# Maker_Display4.net
KiCad netlist of a schematic drawn in EAGLE
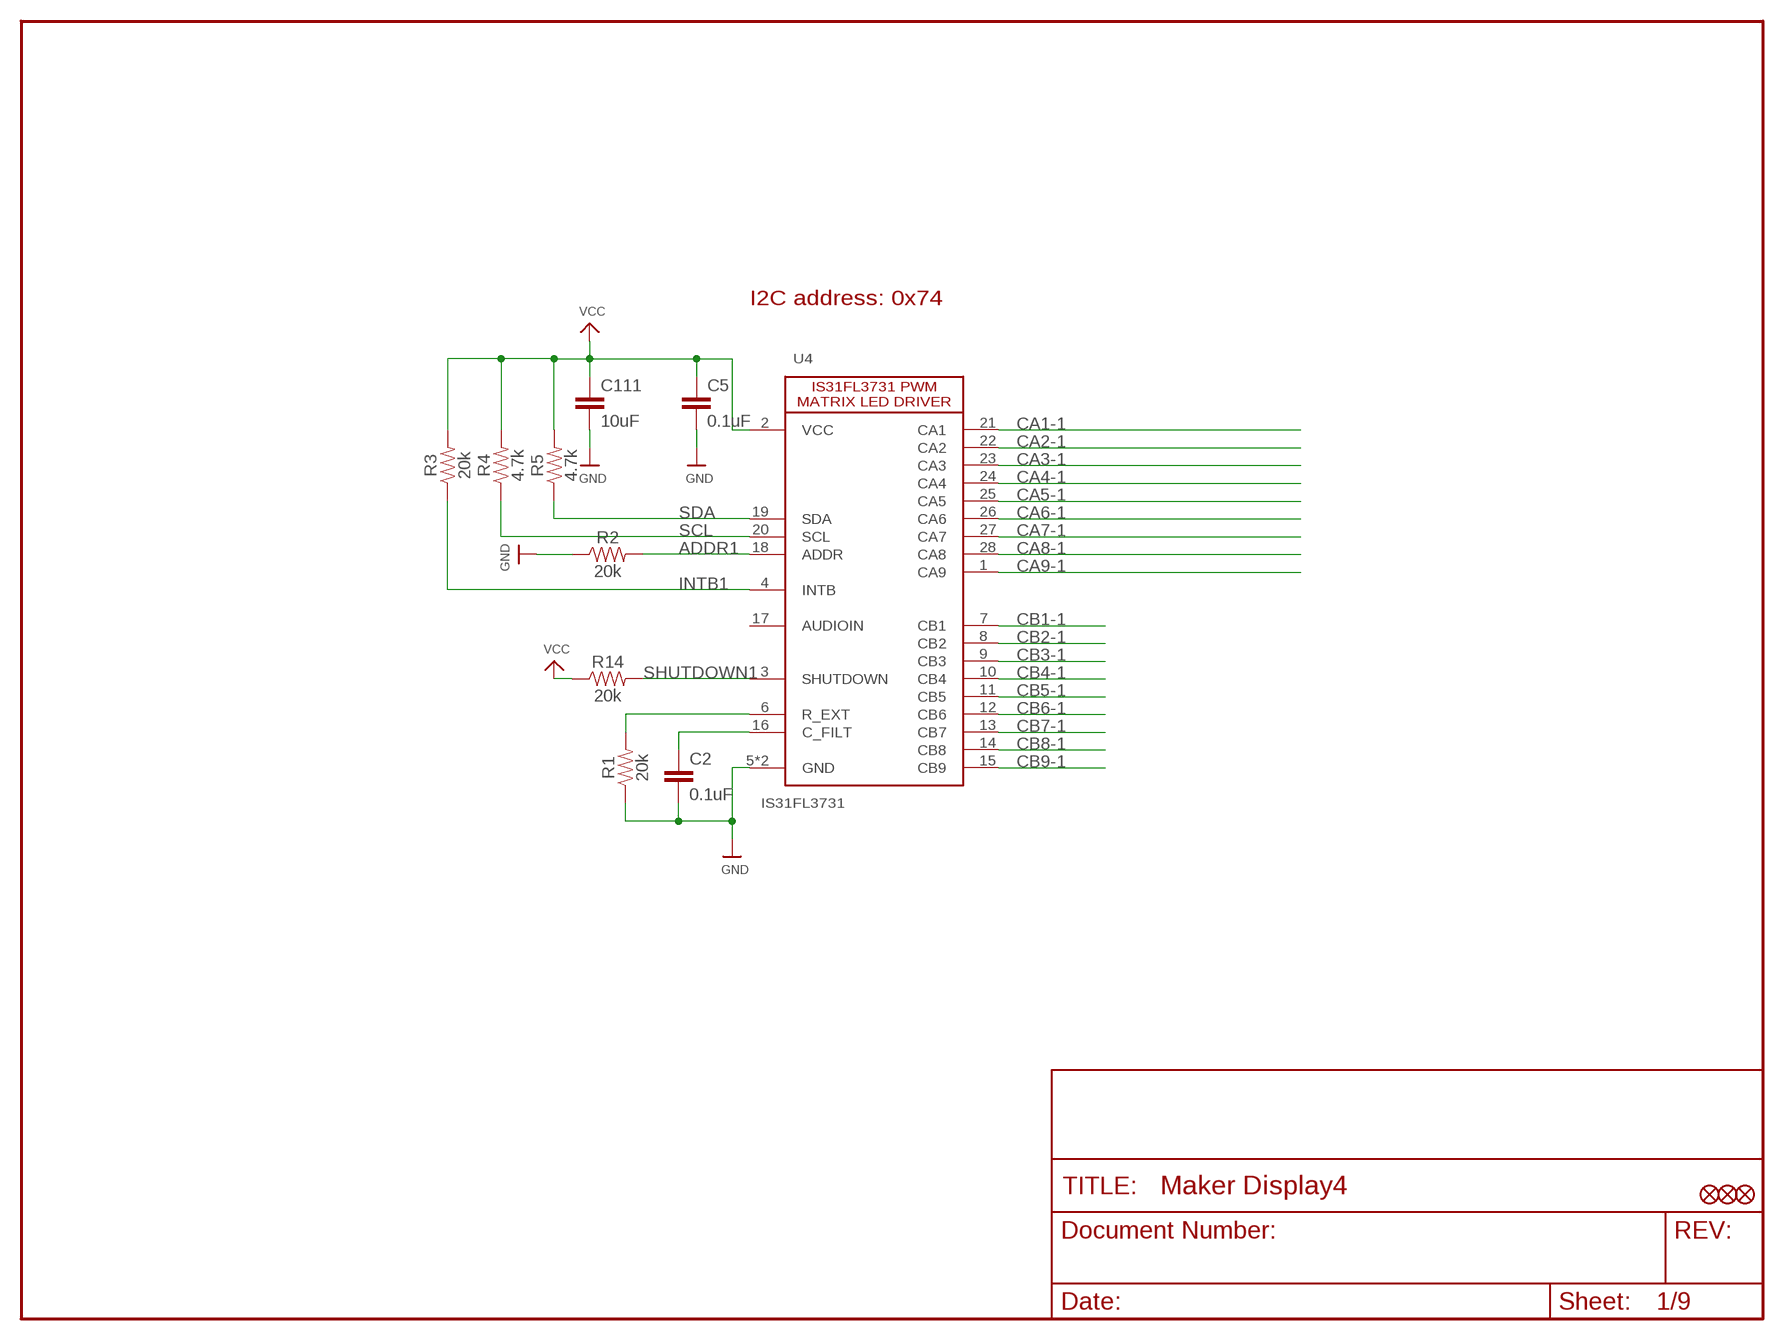
[diagram p0: schematic, sheet 1]
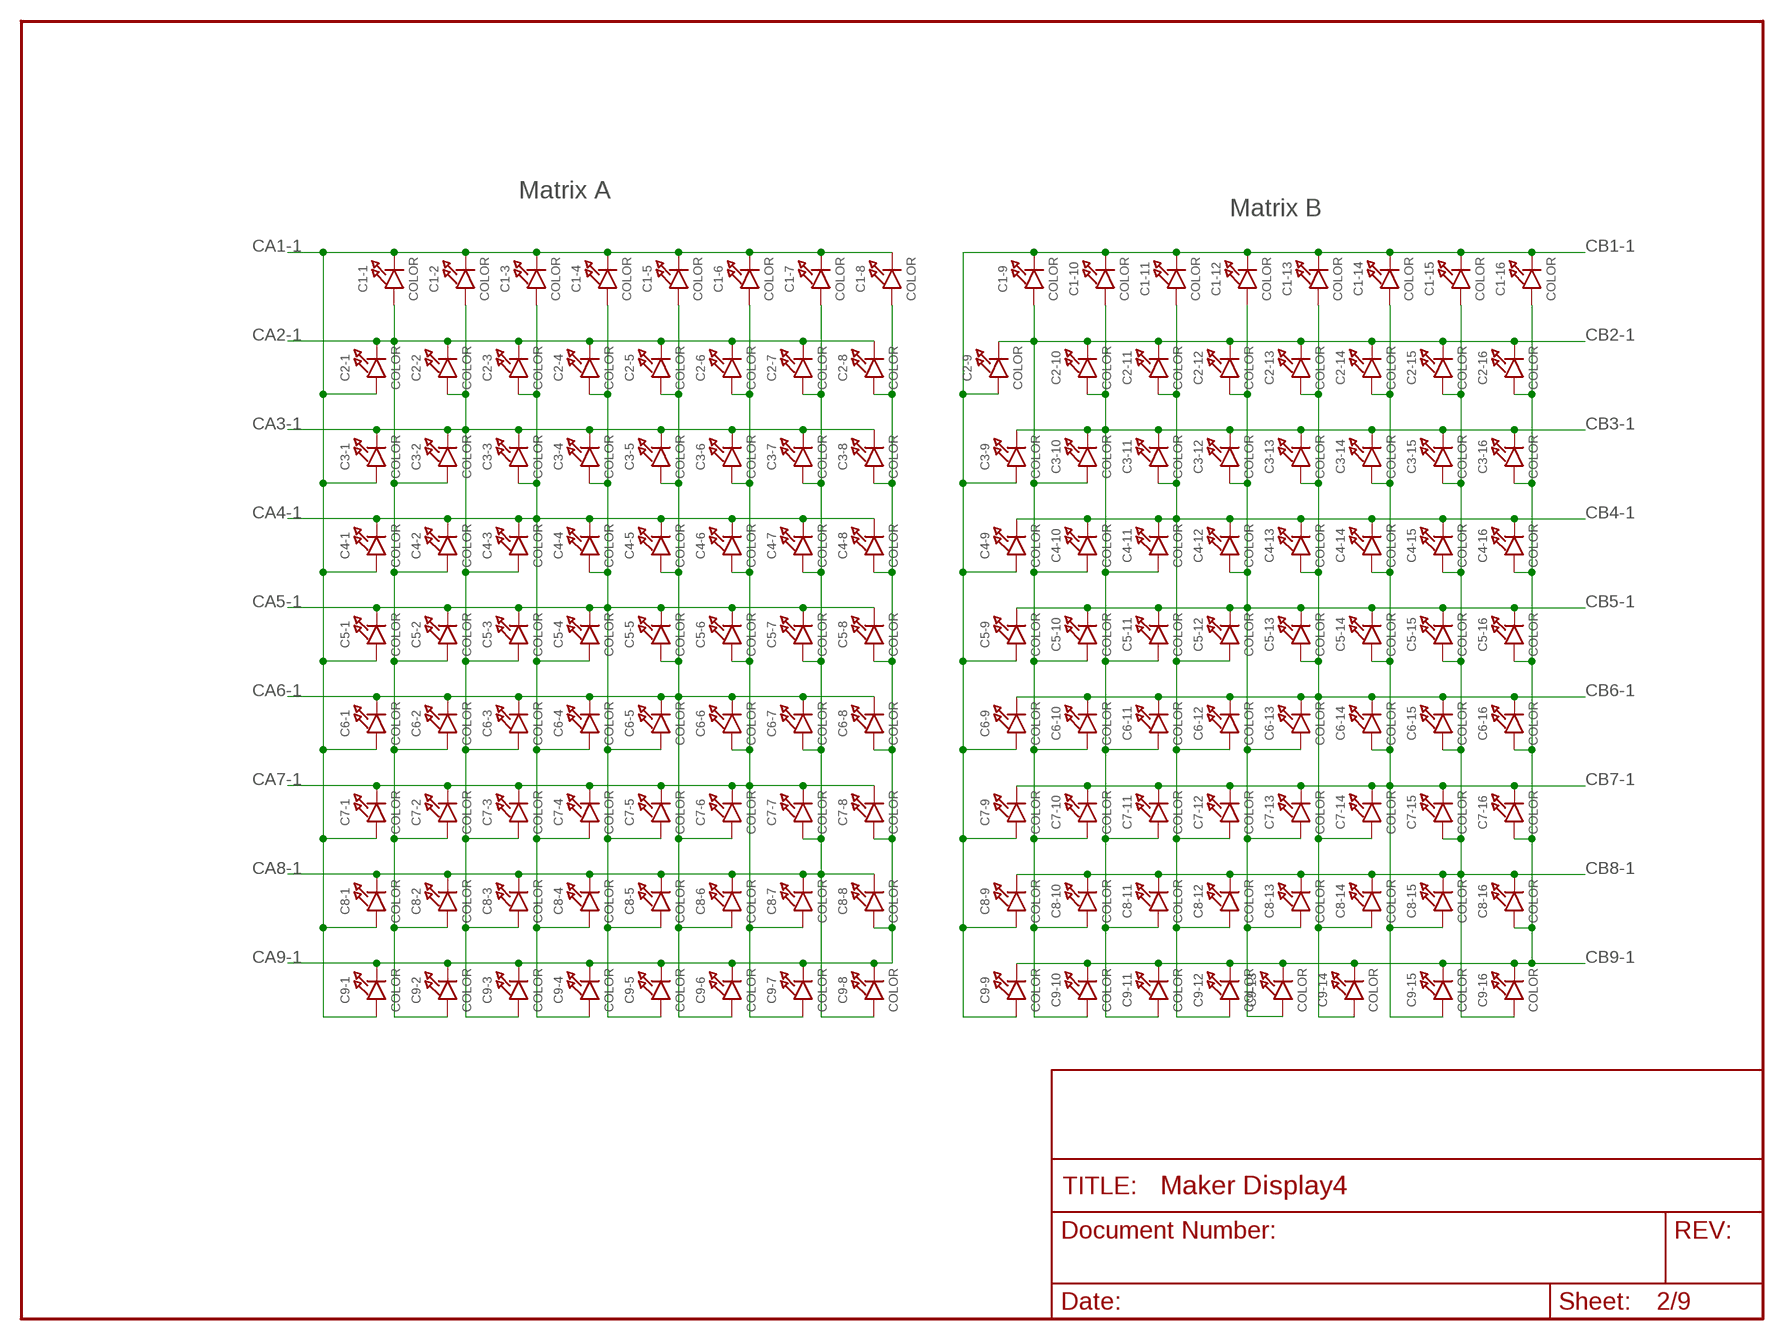
[diagram p1: schematic, sheet 2]
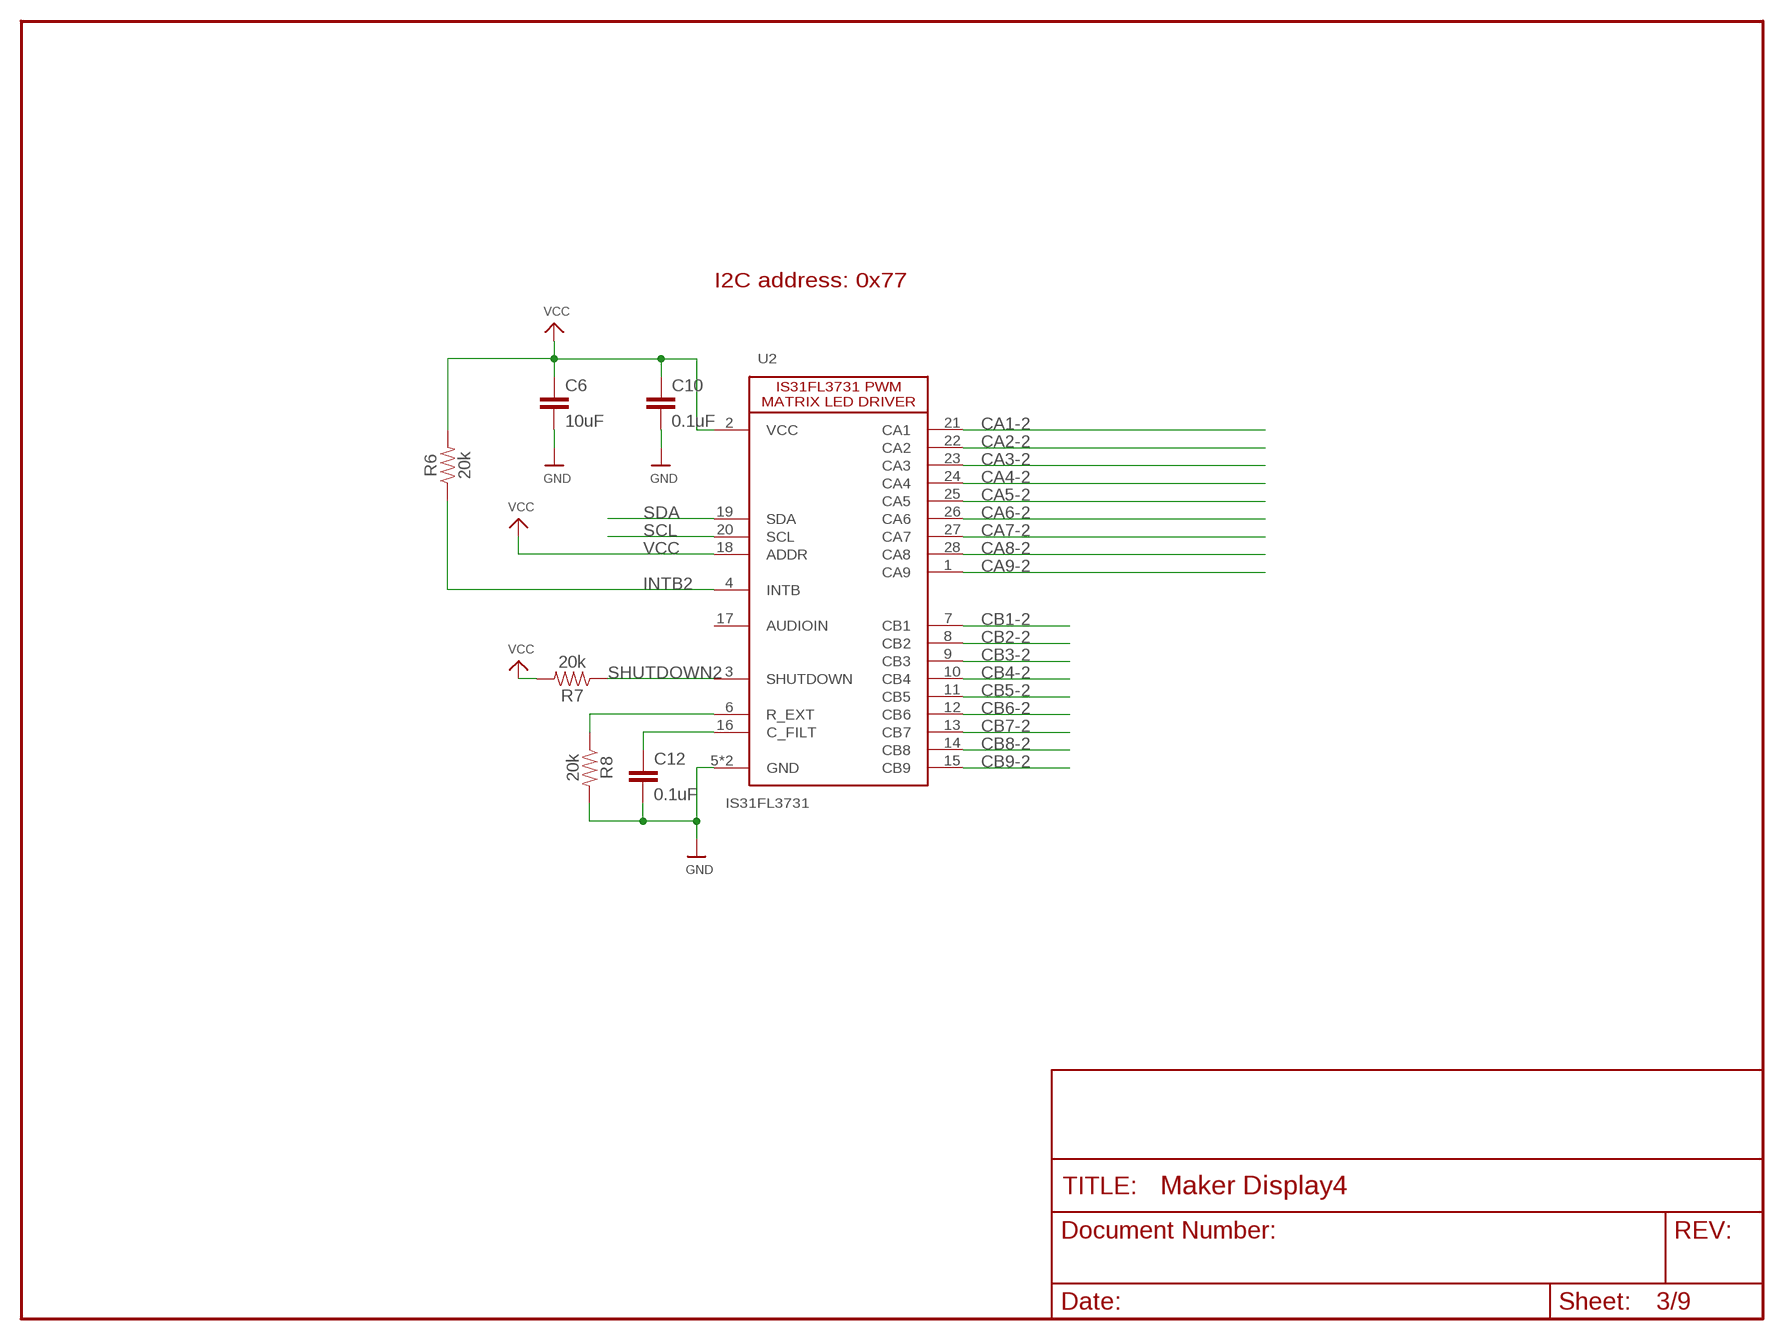
[diagram p2: schematic, sheet 3]
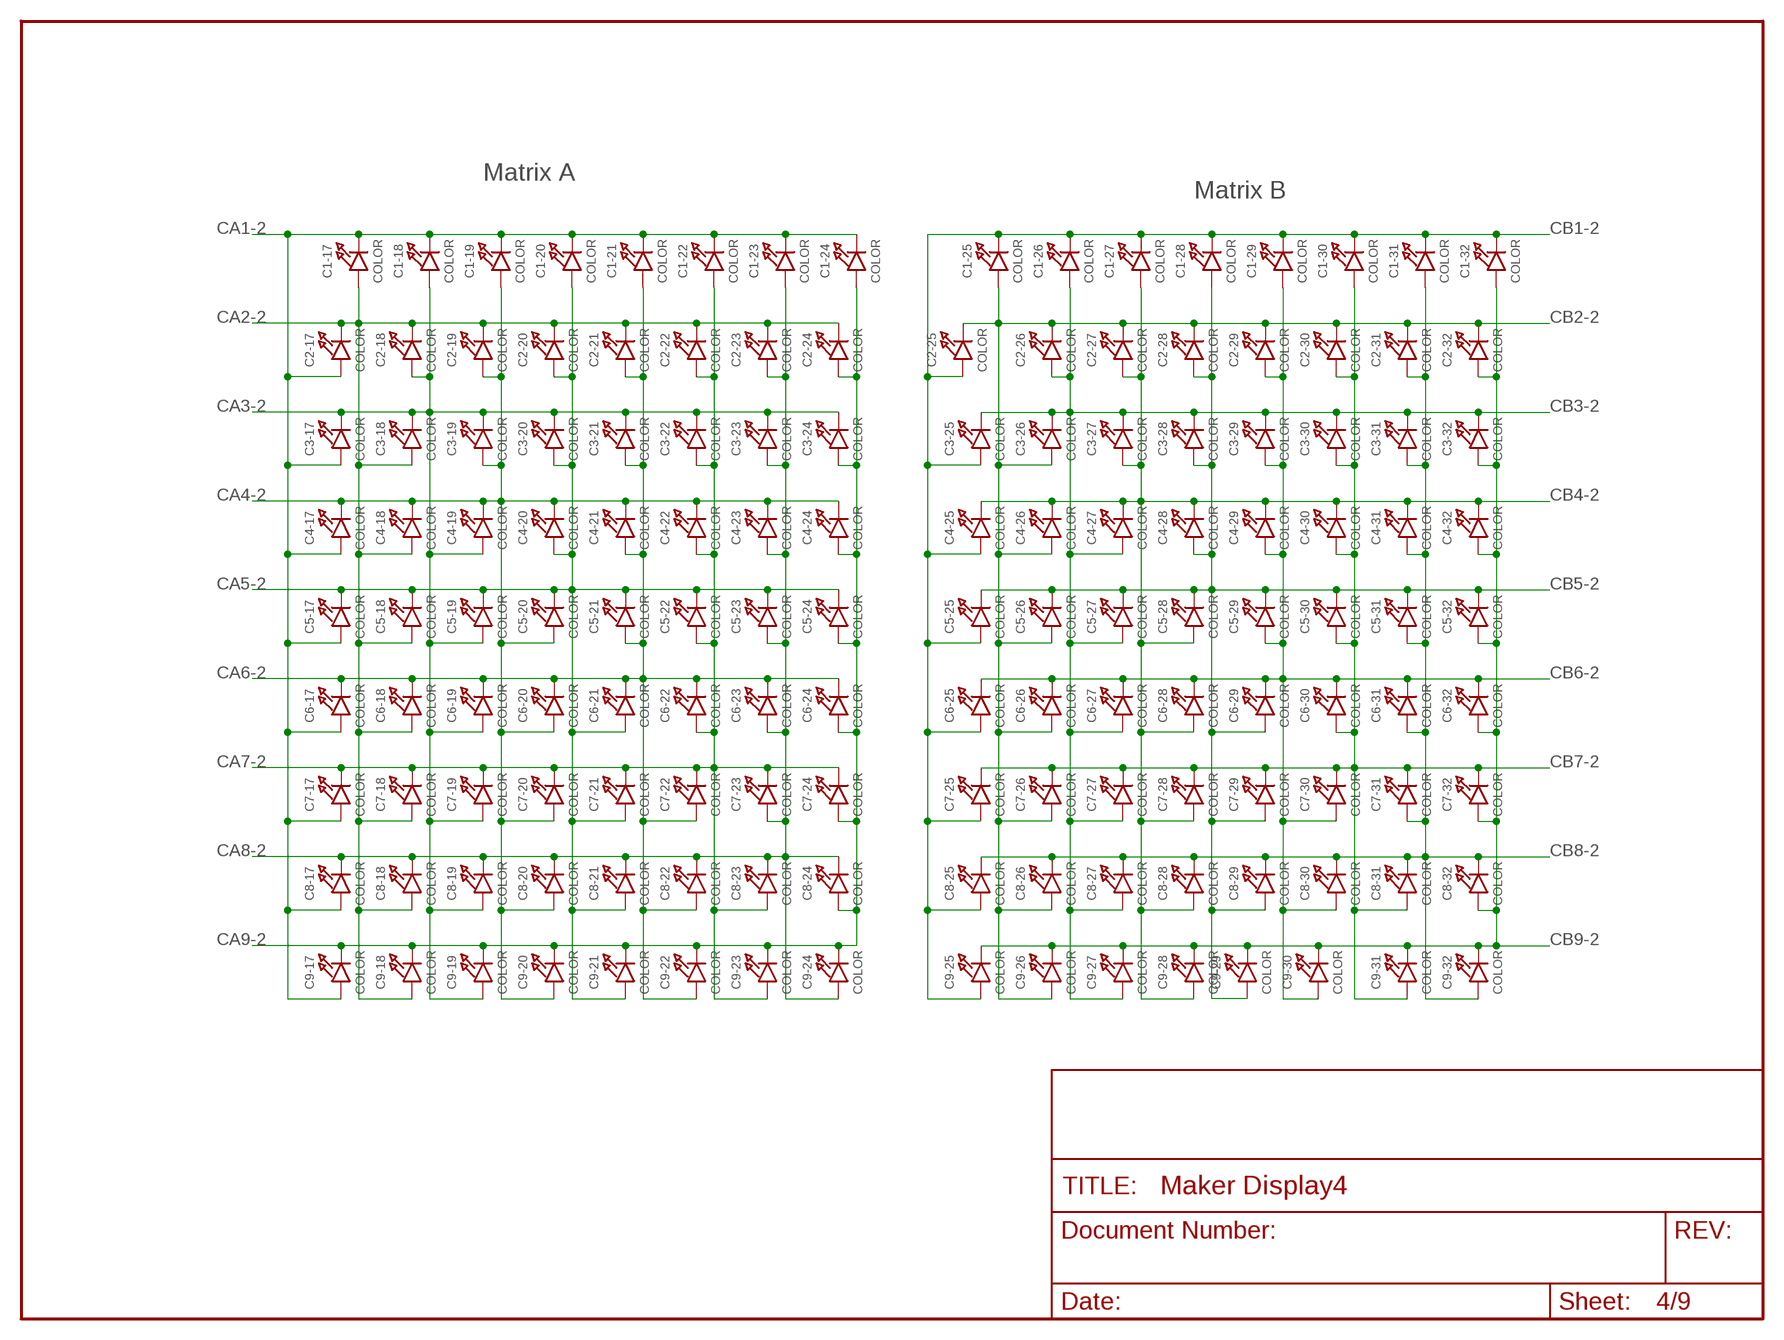
[diagram p3: schematic, sheet 4]
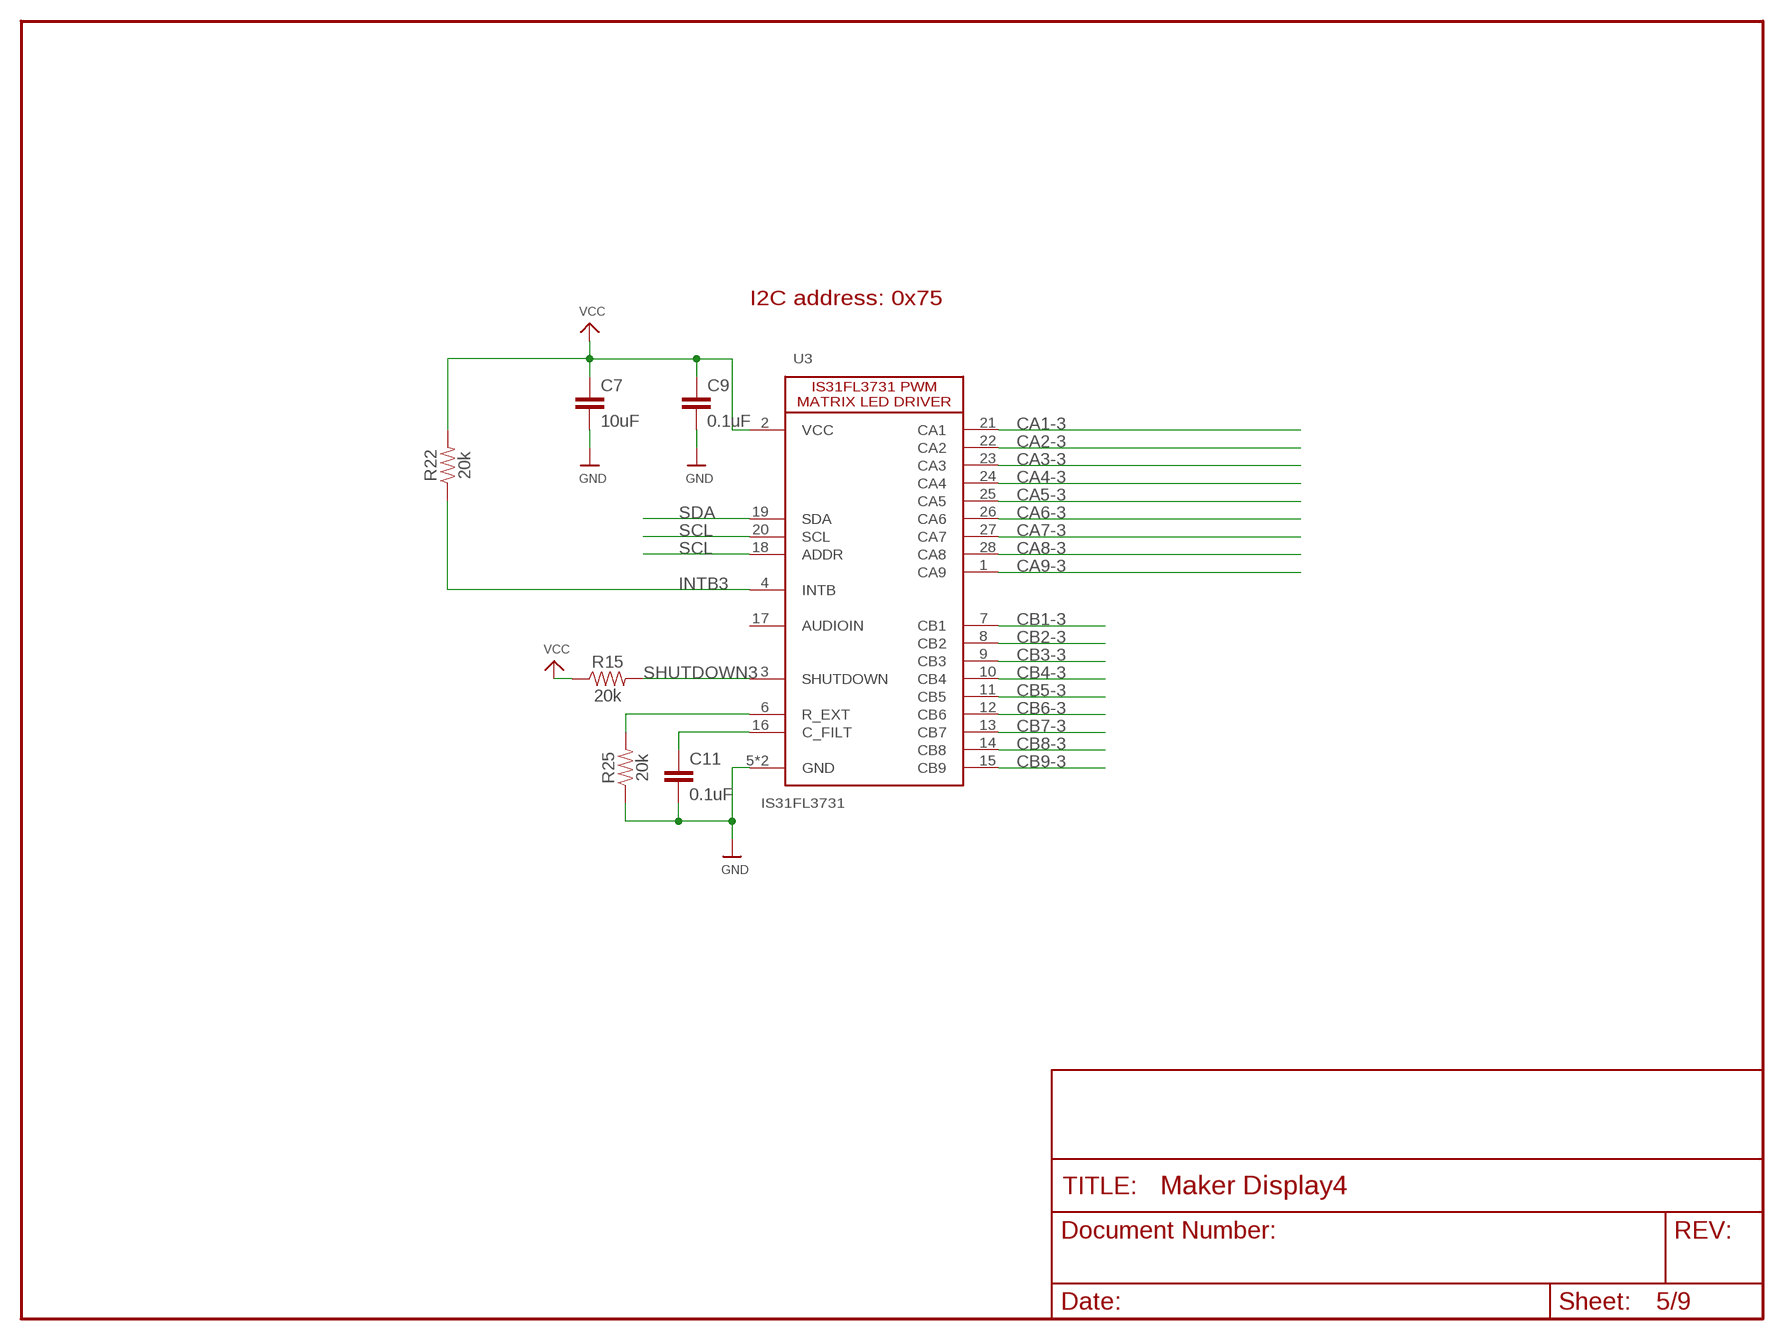
[diagram p4: schematic, sheet 5]
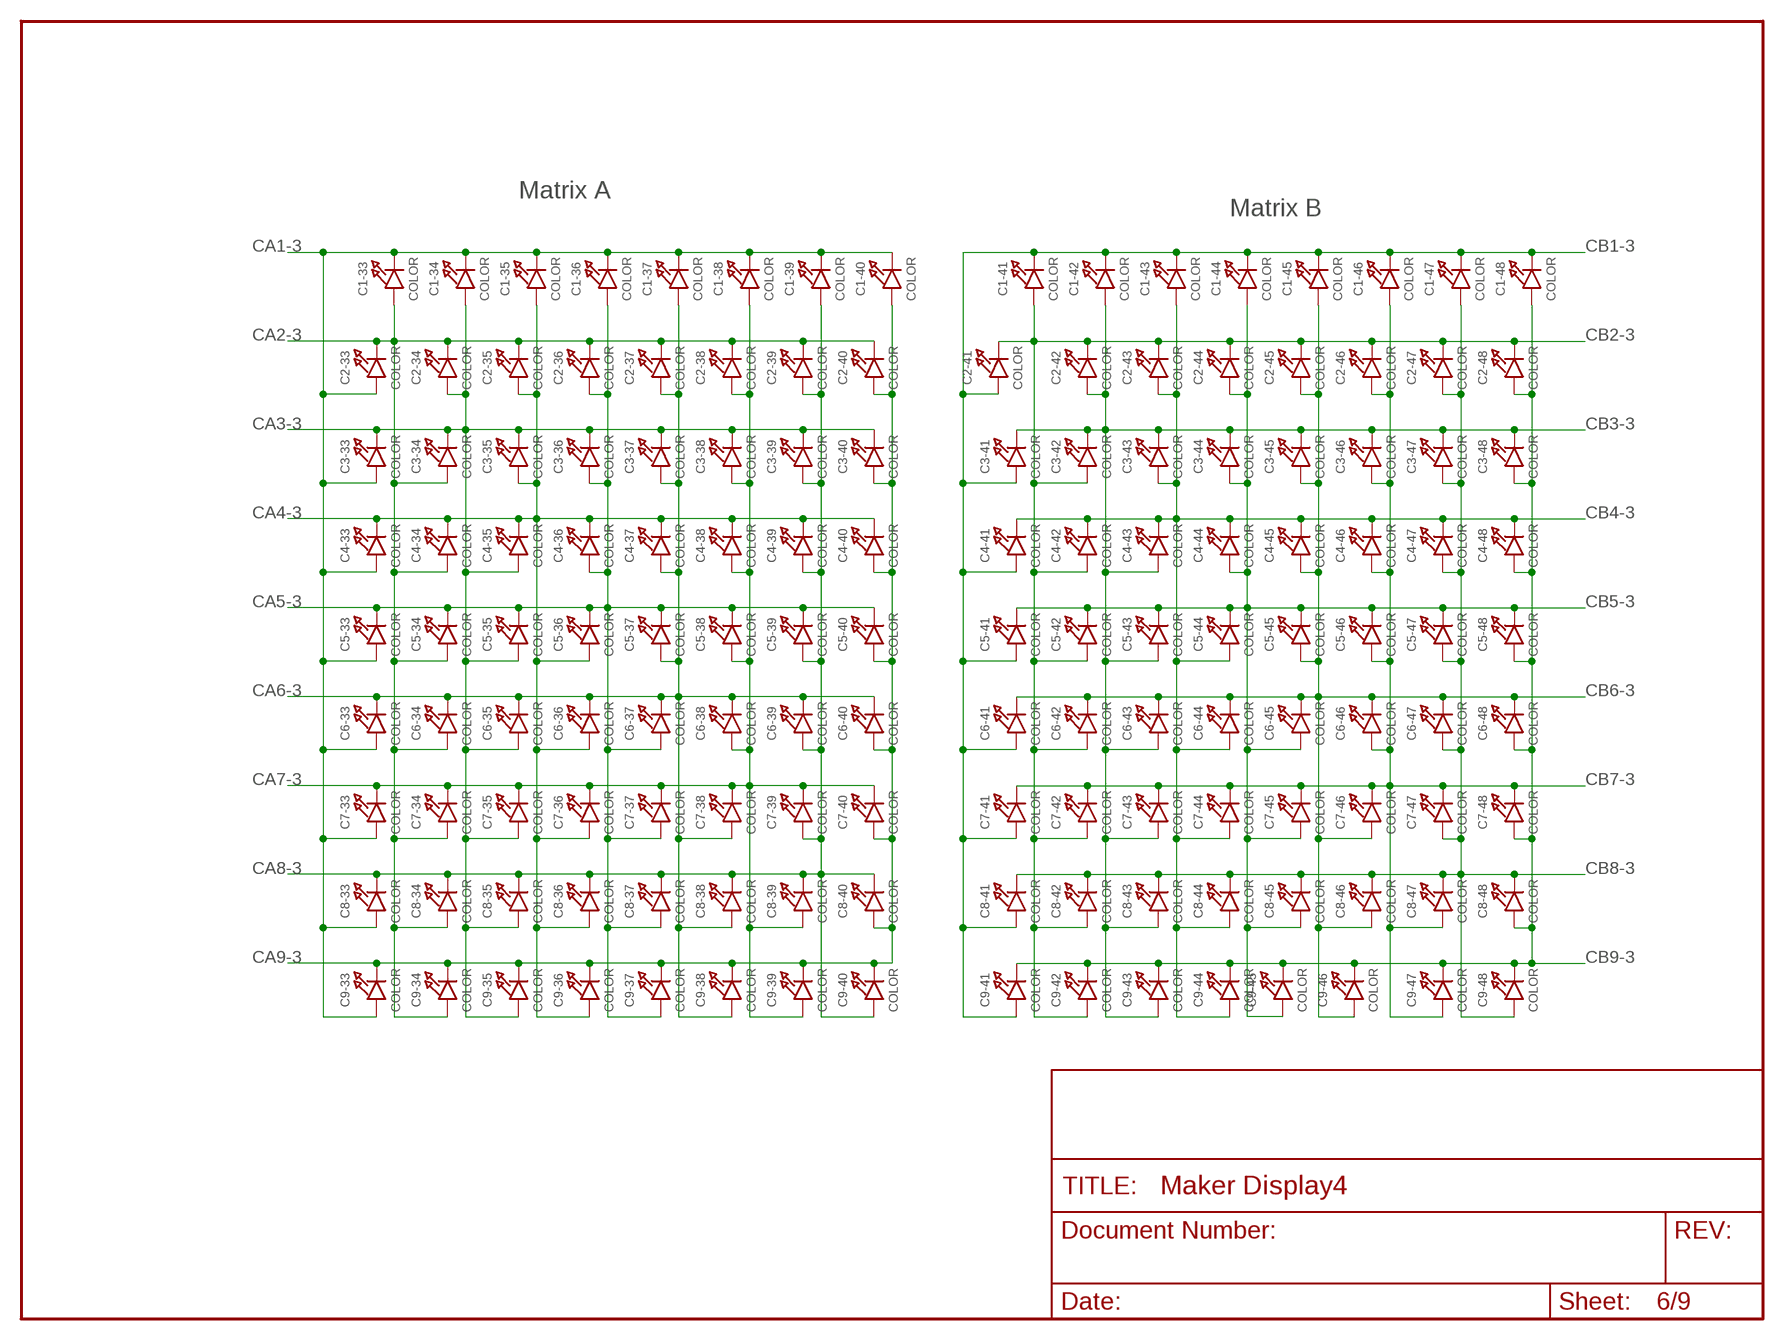
[diagram p5: schematic, sheet 6]
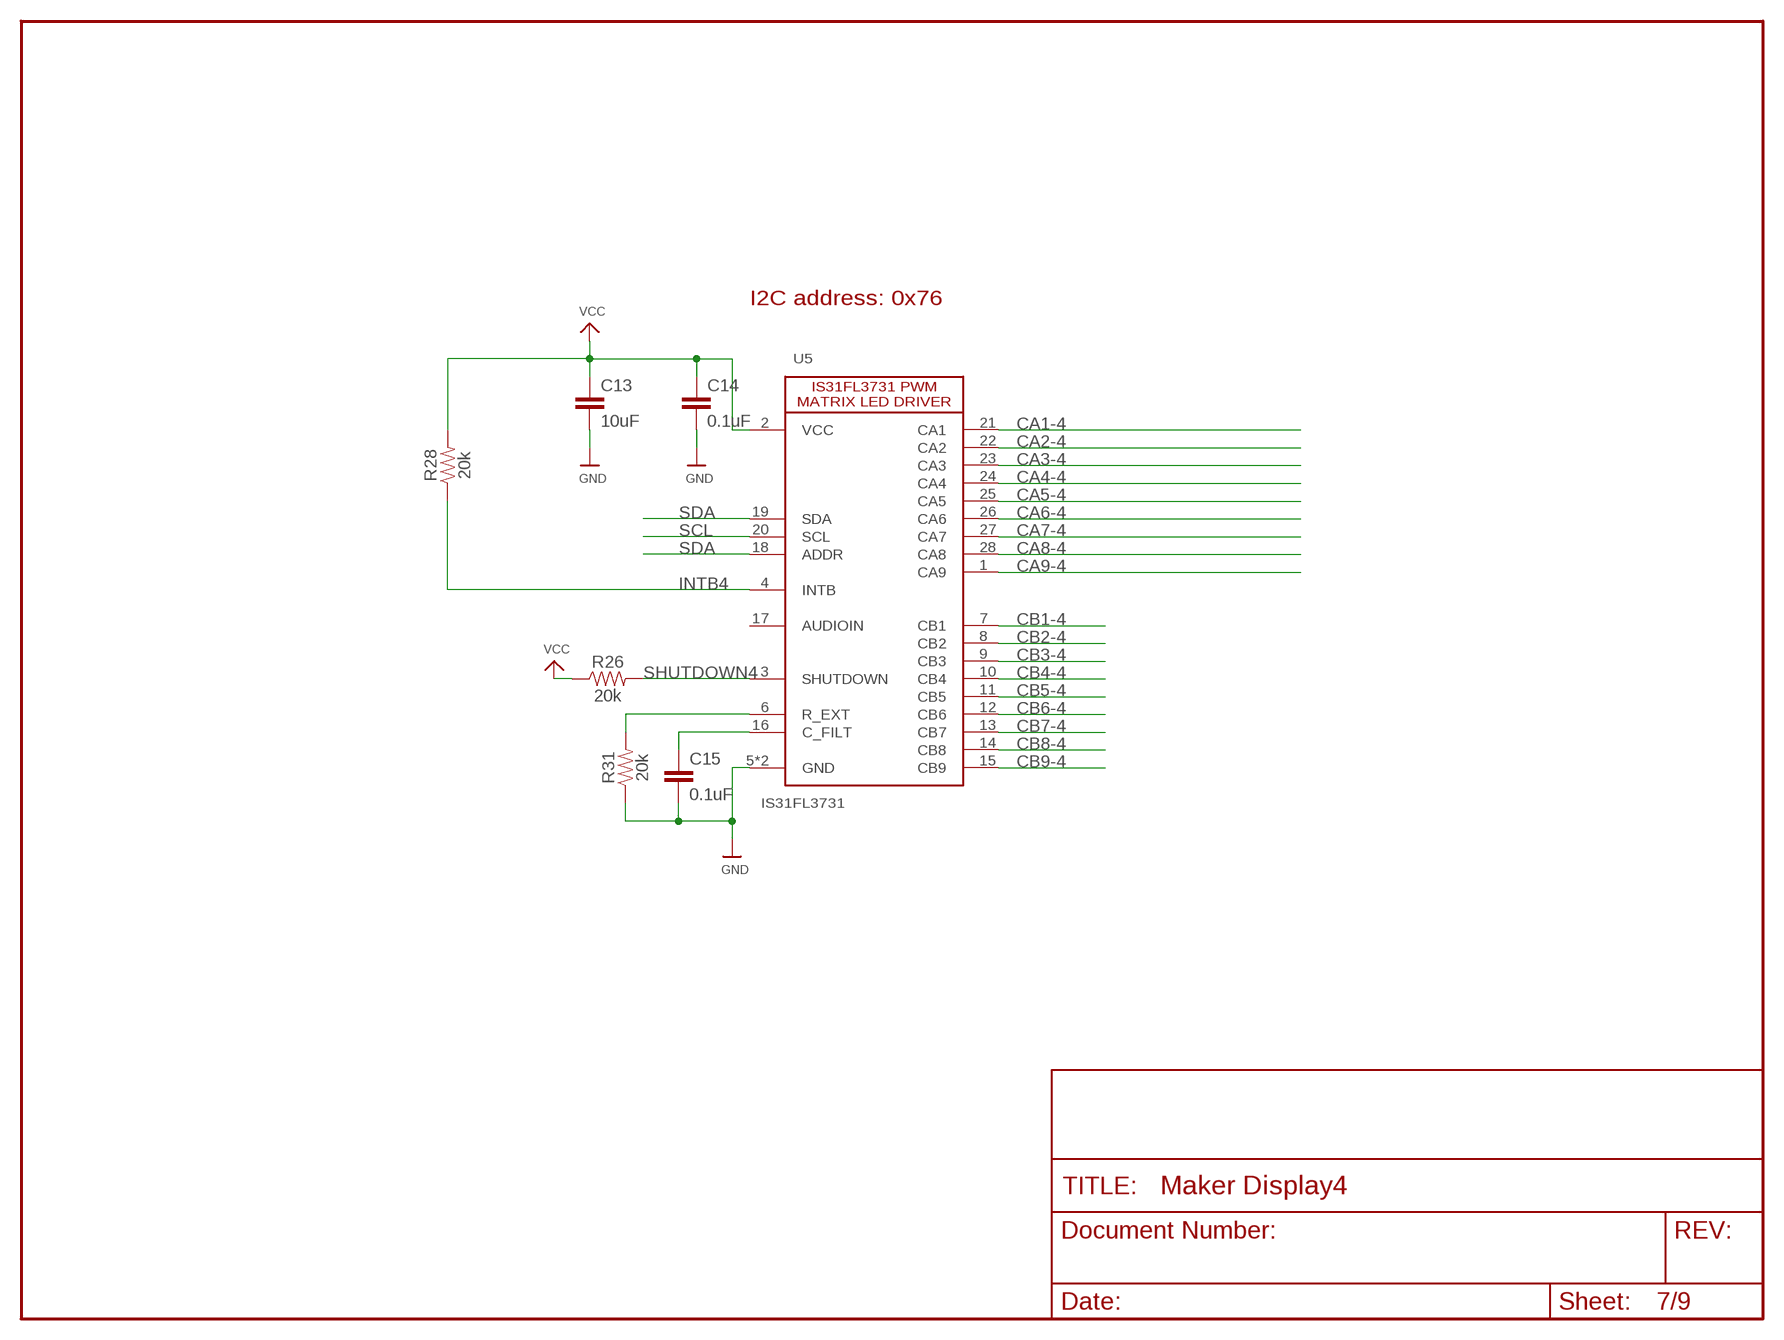
[diagram p6: schematic, sheet 7]
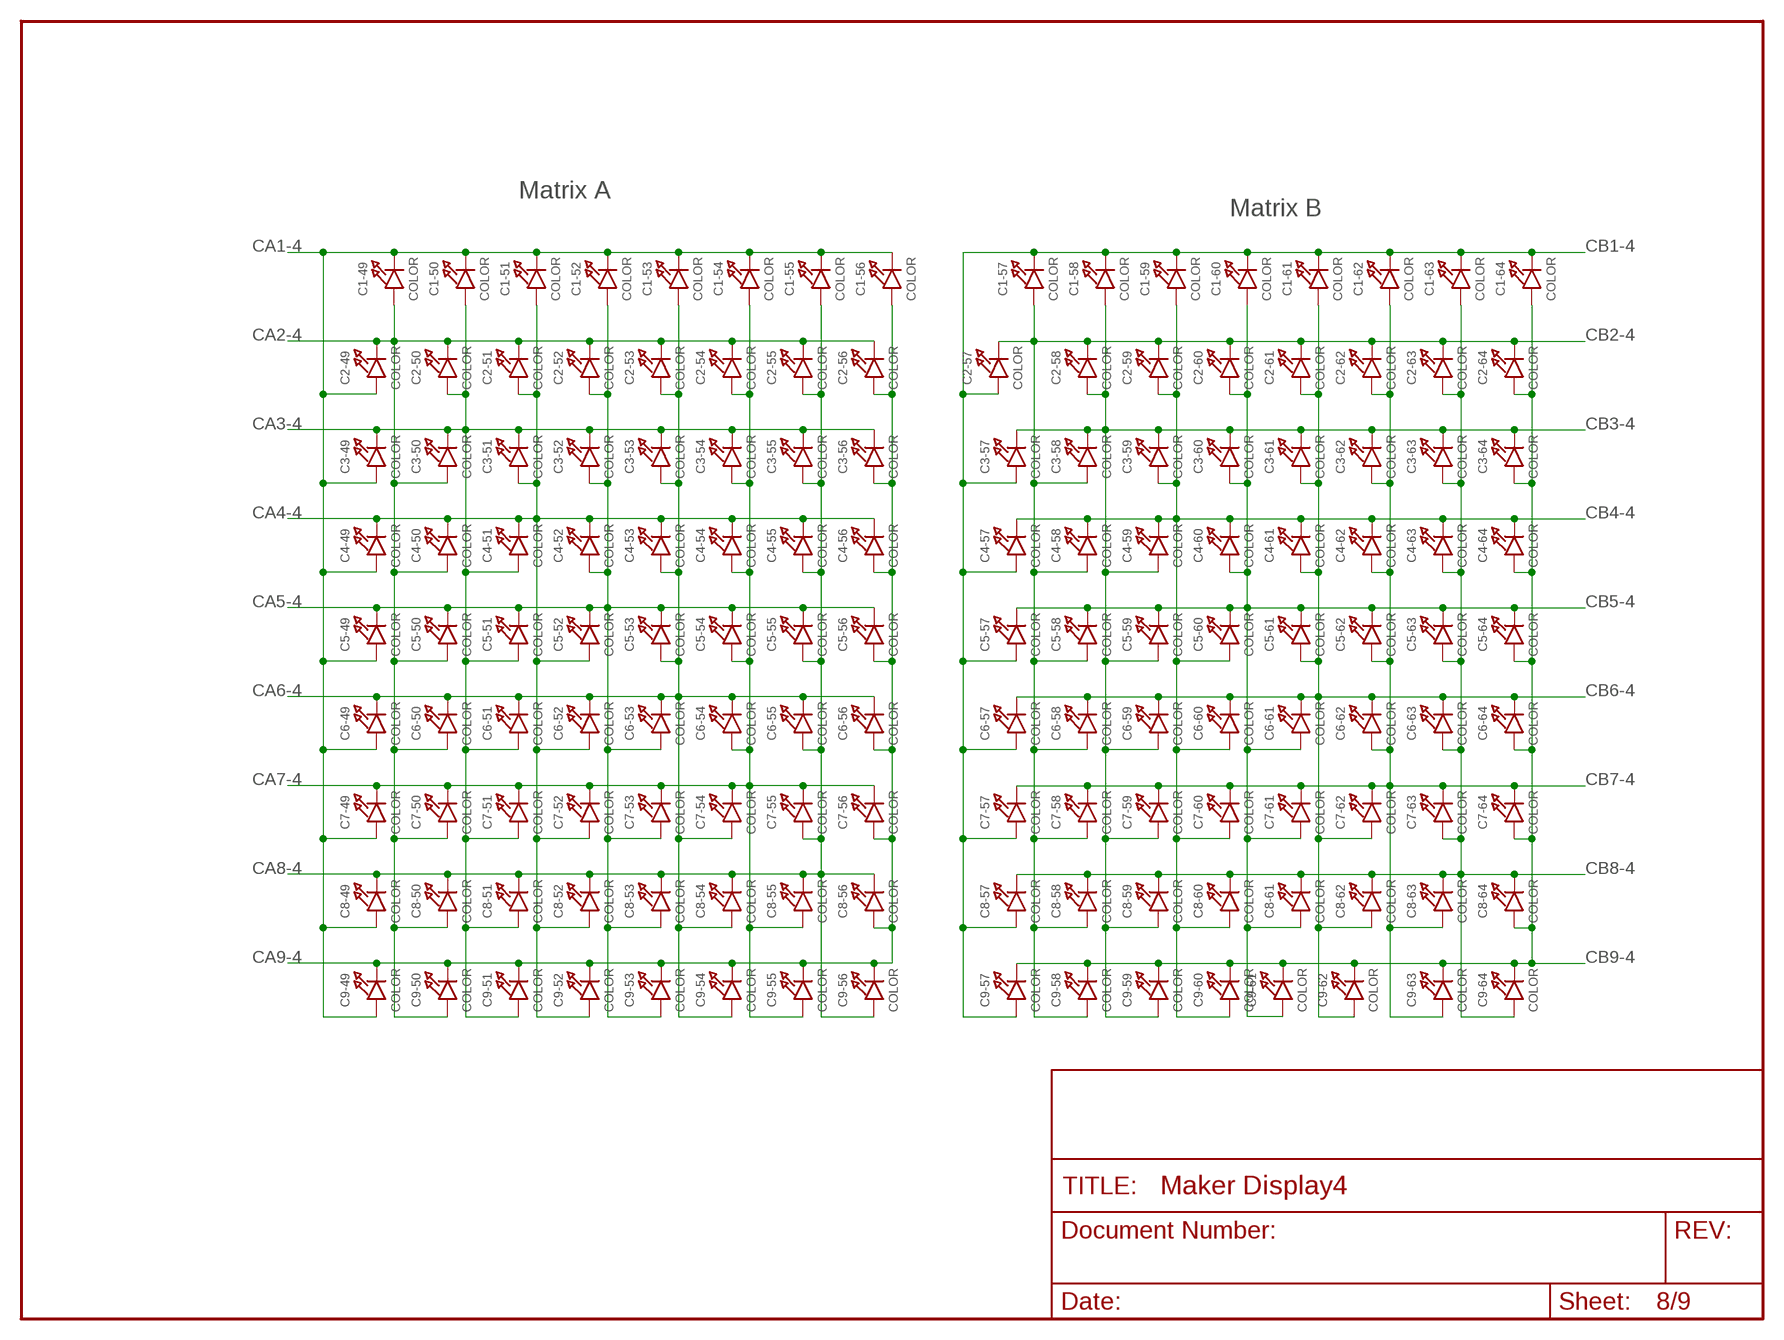
[diagram p7: schematic, sheet 8]
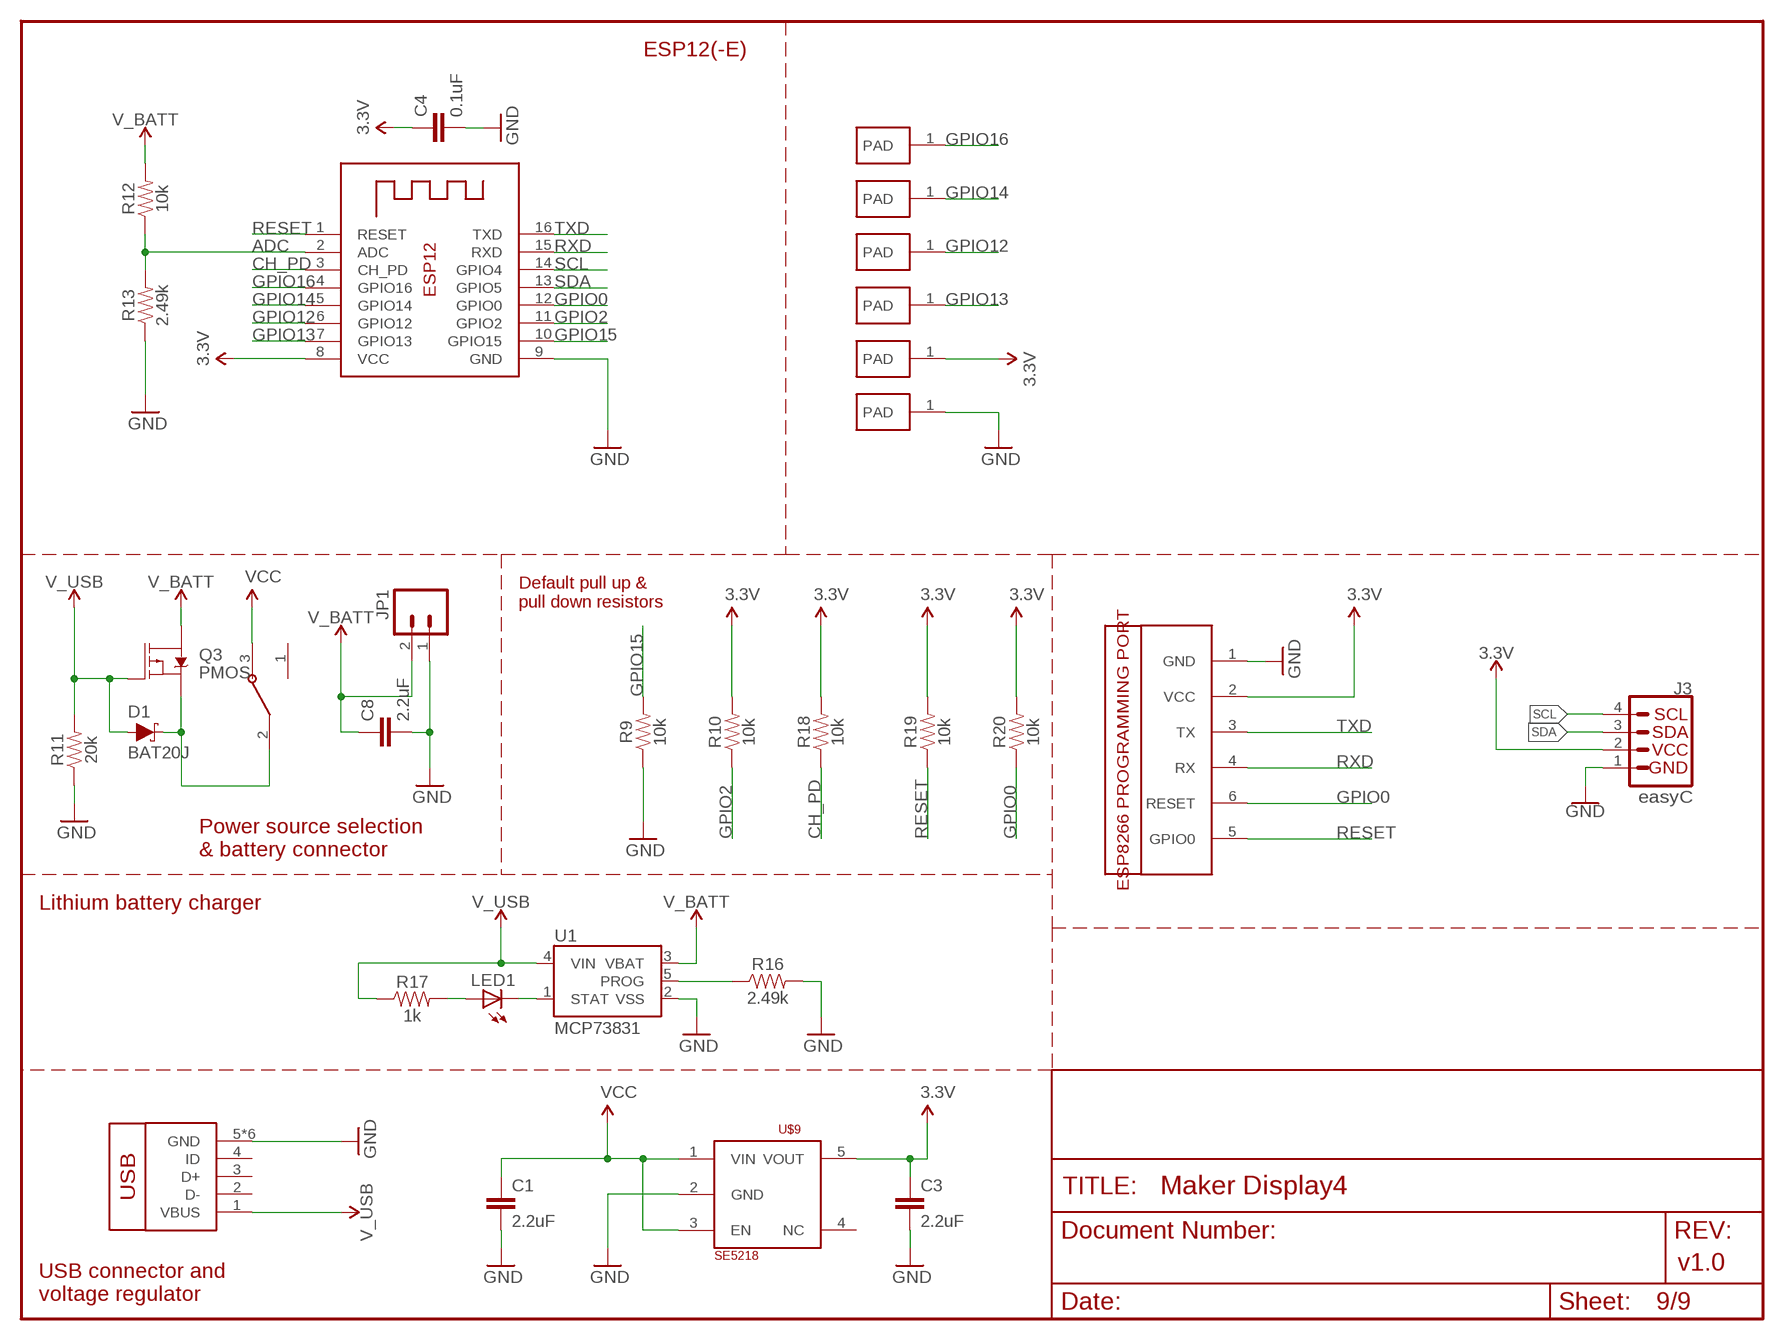
[diagram p8: schematic, sheet 9]

(export (version "E")
  (design (tool "Eeschema 10.0.6"))
  (components
    (comp (ref "C7")
      (value "10uF")
      (footprint "eagle-import:1206")
      (libsource (lib "eagle-import") (part "10UF-1206-6.3V-20%"))
    )
    (comp (ref "C9")
      (value "0.1uF")
      (footprint "eagle-import:0603")
      (libsource (lib "eagle-import") (part "0.1UF-0603-25V-(+80/-20%)"))
    )
    (comp (ref "C11")
      (value "0.1uF")
      (footprint "eagle-import:0603")
      (libsource (lib "eagle-import") (part "0.1UF-0603-25V-(+80/-20%)"))
    )
    (comp (ref "R15")
      (value "20k")
      (footprint "eagle-import:0603")
      (libsource (lib "eagle-import") (part "20KOHM-0603-1/10W-1%"))
    )
    (comp (ref "R22")
      (value "20k")
      (footprint "eagle-import:0603")
      (libsource (lib "eagle-import") (part "20KOHM-0603-1/10W-1%"))
    )
    (comp (ref "R25")
      (value "20k")
      (footprint "eagle-import:0603")
      (libsource (lib "eagle-import") (part "20KOHM-0603-1/10W-1%"))
    )
    (comp (ref "U3")
      (value "IS31FL3731")
      (footprint "eagle-import:QFN28")
      (libsource (lib "eagle-import") (part "IS31FL3731"))
    )
    (comp (ref "C6")
      (value "10uF")
      (footprint "eagle-import:1206")
      (libsource (lib "eagle-import") (part "10UF-1206-6.3V-20%"))
    )
    (comp (ref "C10")
      (value "0.1uF")
      (footprint "eagle-import:0603")
      (libsource (lib "eagle-import") (part "0.1UF-0603-25V-(+80/-20%)"))
    )
    (comp (ref "C12")
      (value "0.1uF")
      (footprint "eagle-import:0603")
      (libsource (lib "eagle-import") (part "0.1UF-0603-25V-(+80/-20%)"))
    )
    (comp (ref "R6")
      (value "20k")
      (footprint "eagle-import:0603")
      (libsource (lib "eagle-import") (part "20KOHM-0603-1/10W-1%"))
    )
    (comp (ref "R7")
      (value "20k")
      (footprint "eagle-import:0603")
      (libsource (lib "eagle-import") (part "20KOHM-0603-1/10W-1%"))
    )
    (comp (ref "R8")
      (value "20k")
      (footprint "eagle-import:0603")
      (libsource (lib "eagle-import") (part "20KOHM-0603-1/10W-1%"))
    )
    (comp (ref "U2")
      (value "IS31FL3731")
      (footprint "eagle-import:QFN28")
      (libsource (lib "eagle-import") (part "IS31FL3731"))
    )
    (comp (ref "C1-33")
      (value "COLOR")
      (footprint "eagle-import:CHIPLED_0603_NOOUTLINE")
      (libsource (lib "eagle-import") (part "LED0603_NOOUTLINE"))
    )
    (comp (ref "C1-34")
      (value "COLOR")
      (footprint "eagle-import:CHIPLED_0603_NOOUTLINE")
      (libsource (lib "eagle-import") (part "LED0603_NOOUTLINE"))
    )
    (comp (ref "C1-35")
      (value "COLOR")
      (footprint "eagle-import:CHIPLED_0603_NOOUTLINE")
      (libsource (lib "eagle-import") (part "LED0603_NOOUTLINE"))
    )
    (comp (ref "C1-36")
      (value "COLOR")
      (footprint "eagle-import:CHIPLED_0603_NOOUTLINE")
      (libsource (lib "eagle-import") (part "LED0603_NOOUTLINE"))
    )
    (comp (ref "C1-37")
      (value "COLOR")
      (footprint "eagle-import:CHIPLED_0603_NOOUTLINE")
      (libsource (lib "eagle-import") (part "LED0603_NOOUTLINE"))
    )
    (comp (ref "C1-38")
      (value "COLOR")
      (footprint "eagle-import:CHIPLED_0603_NOOUTLINE")
      (libsource (lib "eagle-import") (part "LED0603_NOOUTLINE"))
    )
    (comp (ref "C1-39")
      (value "COLOR")
      (footprint "eagle-import:CHIPLED_0603_NOOUTLINE")
      (libsource (lib "eagle-import") (part "LED0603_NOOUTLINE"))
    )
    (comp (ref "C1-40")
      (value "COLOR")
      (footprint "eagle-import:CHIPLED_0603_NOOUTLINE")
      (libsource (lib "eagle-import") (part "LED0603_NOOUTLINE"))
    )
    (comp (ref "C1-41")
      (value "COLOR")
      (footprint "eagle-import:CHIPLED_0603_NOOUTLINE")
      (libsource (lib "eagle-import") (part "LED0603_NOOUTLINE"))
    )
    (comp (ref "C1-42")
      (value "COLOR")
      (footprint "eagle-import:CHIPLED_0603_NOOUTLINE")
      (libsource (lib "eagle-import") (part "LED0603_NOOUTLINE"))
    )
    (comp (ref "C1-43")
      (value "COLOR")
      (footprint "eagle-import:CHIPLED_0603_NOOUTLINE")
      (libsource (lib "eagle-import") (part "LED0603_NOOUTLINE"))
    )
    (comp (ref "C1-44")
      (value "COLOR")
      (footprint "eagle-import:CHIPLED_0603_NOOUTLINE")
      (libsource (lib "eagle-import") (part "LED0603_NOOUTLINE"))
    )
    (comp (ref "C1-45")
      (value "COLOR")
      (footprint "eagle-import:CHIPLED_0603_NOOUTLINE")
      (libsource (lib "eagle-import") (part "LED0603_NOOUTLINE"))
    )
    (comp (ref "C1-46")
      (value "COLOR")
      (footprint "eagle-import:CHIPLED_0603_NOOUTLINE")
      (libsource (lib "eagle-import") (part "LED0603_NOOUTLINE"))
    )
    (comp (ref "C1-47")
      (value "COLOR")
      (footprint "eagle-import:CHIPLED_0603_NOOUTLINE")
      (libsource (lib "eagle-import") (part "LED0603_NOOUTLINE"))
    )
    (comp (ref "C1-48")
      (value "COLOR")
      (footprint "eagle-import:CHIPLED_0603_NOOUTLINE")
      (libsource (lib "eagle-import") (part "LED0603_NOOUTLINE"))
    )
    (comp (ref "C2-33")
      (value "COLOR")
      (footprint "eagle-import:CHIPLED_0603_NOOUTLINE")
      (libsource (lib "eagle-import") (part "LED0603_NOOUTLINE"))
    )
    (comp (ref "C2-34")
      (value "COLOR")
      (footprint "eagle-import:CHIPLED_0603_NOOUTLINE")
      (libsource (lib "eagle-import") (part "LED0603_NOOUTLINE"))
    )
    (comp (ref "C2-35")
      (value "COLOR")
      (footprint "eagle-import:CHIPLED_0603_NOOUTLINE")
      (libsource (lib "eagle-import") (part "LED0603_NOOUTLINE"))
    )
    (comp (ref "C2-36")
      (value "COLOR")
      (footprint "eagle-import:CHIPLED_0603_NOOUTLINE")
      (libsource (lib "eagle-import") (part "LED0603_NOOUTLINE"))
    )
    (comp (ref "C2-37")
      (value "COLOR")
      (footprint "eagle-import:CHIPLED_0603_NOOUTLINE")
      (libsource (lib "eagle-import") (part "LED0603_NOOUTLINE"))
    )
    (comp (ref "C2-38")
      (value "COLOR")
      (footprint "eagle-import:CHIPLED_0603_NOOUTLINE")
      (libsource (lib "eagle-import") (part "LED0603_NOOUTLINE"))
    )
    (comp (ref "C2-39")
      (value "COLOR")
      (footprint "eagle-import:CHIPLED_0603_NOOUTLINE")
      (libsource (lib "eagle-import") (part "LED0603_NOOUTLINE"))
    )
    (comp (ref "C2-40")
      (value "COLOR")
      (footprint "eagle-import:CHIPLED_0603_NOOUTLINE")
      (libsource (lib "eagle-import") (part "LED0603_NOOUTLINE"))
    )
    (comp (ref "C2-41")
      (value "COLOR")
      (footprint "eagle-import:CHIPLED_0603_NOOUTLINE")
      (libsource (lib "eagle-import") (part "LED0603_NOOUTLINE"))
    )
    (comp (ref "C2-42")
      (value "COLOR")
      (footprint "eagle-import:CHIPLED_0603_NOOUTLINE")
      (libsource (lib "eagle-import") (part "LED0603_NOOUTLINE"))
    )
    (comp (ref "C2-43")
      (value "COLOR")
      (footprint "eagle-import:CHIPLED_0603_NOOUTLINE")
      (libsource (lib "eagle-import") (part "LED0603_NOOUTLINE"))
    )
    (comp (ref "C2-44")
      (value "COLOR")
      (footprint "eagle-import:CHIPLED_0603_NOOUTLINE")
      (libsource (lib "eagle-import") (part "LED0603_NOOUTLINE"))
    )
    (comp (ref "C2-45")
      (value "COLOR")
      (footprint "eagle-import:CHIPLED_0603_NOOUTLINE")
      (libsource (lib "eagle-import") (part "LED0603_NOOUTLINE"))
    )
    (comp (ref "C2-46")
      (value "COLOR")
      (footprint "eagle-import:CHIPLED_0603_NOOUTLINE")
      (libsource (lib "eagle-import") (part "LED0603_NOOUTLINE"))
    )
    (comp (ref "C2-47")
      (value "COLOR")
      (footprint "eagle-import:CHIPLED_0603_NOOUTLINE")
      (libsource (lib "eagle-import") (part "LED0603_NOOUTLINE"))
    )
    (comp (ref "C2-48")
      (value "COLOR")
      (footprint "eagle-import:CHIPLED_0603_NOOUTLINE")
      (libsource (lib "eagle-import") (part "LED0603_NOOUTLINE"))
    )
    (comp (ref "C3-33")
      (value "COLOR")
      (footprint "eagle-import:CHIPLED_0603_NOOUTLINE")
      (libsource (lib "eagle-import") (part "LED0603_NOOUTLINE"))
    )
    (comp (ref "C3-34")
      (value "COLOR")
      (footprint "eagle-import:CHIPLED_0603_NOOUTLINE")
      (libsource (lib "eagle-import") (part "LED0603_NOOUTLINE"))
    )
    (comp (ref "C3-35")
      (value "COLOR")
      (footprint "eagle-import:CHIPLED_0603_NOOUTLINE")
      (libsource (lib "eagle-import") (part "LED0603_NOOUTLINE"))
    )
    (comp (ref "C3-36")
      (value "COLOR")
      (footprint "eagle-import:CHIPLED_0603_NOOUTLINE")
      (libsource (lib "eagle-import") (part "LED0603_NOOUTLINE"))
    )
    (comp (ref "C3-37")
      (value "COLOR")
      (footprint "eagle-import:CHIPLED_0603_NOOUTLINE")
      (libsource (lib "eagle-import") (part "LED0603_NOOUTLINE"))
    )
    (comp (ref "C3-38")
      (value "COLOR")
      (footprint "eagle-import:CHIPLED_0603_NOOUTLINE")
      (libsource (lib "eagle-import") (part "LED0603_NOOUTLINE"))
    )
    (comp (ref "C3-39")
      (value "COLOR")
      (footprint "eagle-import:CHIPLED_0603_NOOUTLINE")
      (libsource (lib "eagle-import") (part "LED0603_NOOUTLINE"))
    )
    (comp (ref "C3-40")
      (value "COLOR")
      (footprint "eagle-import:CHIPLED_0603_NOOUTLINE")
      (libsource (lib "eagle-import") (part "LED0603_NOOUTLINE"))
    )
    (comp (ref "C3-41")
      (value "COLOR")
      (footprint "eagle-import:CHIPLED_0603_NOOUTLINE")
      (libsource (lib "eagle-import") (part "LED0603_NOOUTLINE"))
    )
    (comp (ref "C3-42")
      (value "COLOR")
      (footprint "eagle-import:CHIPLED_0603_NOOUTLINE")
      (libsource (lib "eagle-import") (part "LED0603_NOOUTLINE"))
    )
    (comp (ref "C3-43")
      (value "COLOR")
      (footprint "eagle-import:CHIPLED_0603_NOOUTLINE")
      (libsource (lib "eagle-import") (part "LED0603_NOOUTLINE"))
    )
    (comp (ref "C3-44")
      (value "COLOR")
      (footprint "eagle-import:CHIPLED_0603_NOOUTLINE")
      (libsource (lib "eagle-import") (part "LED0603_NOOUTLINE"))
    )
    (comp (ref "C3-45")
      (value "COLOR")
      (footprint "eagle-import:CHIPLED_0603_NOOUTLINE")
      (libsource (lib "eagle-import") (part "LED0603_NOOUTLINE"))
    )
    (comp (ref "C3-46")
      (value "COLOR")
      (footprint "eagle-import:CHIPLED_0603_NOOUTLINE")
      (libsource (lib "eagle-import") (part "LED0603_NOOUTLINE"))
    )
    (comp (ref "C3-47")
      (value "COLOR")
      (footprint "eagle-import:CHIPLED_0603_NOOUTLINE")
      (libsource (lib "eagle-import") (part "LED0603_NOOUTLINE"))
    )
    (comp (ref "C3-48")
      (value "COLOR")
      (footprint "eagle-import:CHIPLED_0603_NOOUTLINE")
      (libsource (lib "eagle-import") (part "LED0603_NOOUTLINE"))
    )
    (comp (ref "C4-33")
      (value "COLOR")
      (footprint "eagle-import:CHIPLED_0603_NOOUTLINE")
      (libsource (lib "eagle-import") (part "LED0603_NOOUTLINE"))
    )
    (comp (ref "C4-34")
      (value "COLOR")
      (footprint "eagle-import:CHIPLED_0603_NOOUTLINE")
      (libsource (lib "eagle-import") (part "LED0603_NOOUTLINE"))
    )
    (comp (ref "C4-35")
      (value "COLOR")
      (footprint "eagle-import:CHIPLED_0603_NOOUTLINE")
      (libsource (lib "eagle-import") (part "LED0603_NOOUTLINE"))
    )
    (comp (ref "C4-36")
      (value "COLOR")
      (footprint "eagle-import:CHIPLED_0603_NOOUTLINE")
      (libsource (lib "eagle-import") (part "LED0603_NOOUTLINE"))
    )
    (comp (ref "C4-37")
      (value "COLOR")
      (footprint "eagle-import:CHIPLED_0603_NOOUTLINE")
      (libsource (lib "eagle-import") (part "LED0603_NOOUTLINE"))
    )
    (comp (ref "C4-38")
      (value "COLOR")
      (footprint "eagle-import:CHIPLED_0603_NOOUTLINE")
      (libsource (lib "eagle-import") (part "LED0603_NOOUTLINE"))
    )
    (comp (ref "C4-39")
      (value "COLOR")
      (footprint "eagle-import:CHIPLED_0603_NOOUTLINE")
      (libsource (lib "eagle-import") (part "LED0603_NOOUTLINE"))
    )
    (comp (ref "C4-40")
      (value "COLOR")
      (footprint "eagle-import:CHIPLED_0603_NOOUTLINE")
      (libsource (lib "eagle-import") (part "LED0603_NOOUTLINE"))
    )
    (comp (ref "C4-41")
      (value "COLOR")
      (footprint "eagle-import:CHIPLED_0603_NOOUTLINE")
      (libsource (lib "eagle-import") (part "LED0603_NOOUTLINE"))
    )
    (comp (ref "C4-42")
      (value "COLOR")
      (footprint "eagle-import:CHIPLED_0603_NOOUTLINE")
      (libsource (lib "eagle-import") (part "LED0603_NOOUTLINE"))
    )
    (comp (ref "C4-43")
      (value "COLOR")
      (footprint "eagle-import:CHIPLED_0603_NOOUTLINE")
      (libsource (lib "eagle-import") (part "LED0603_NOOUTLINE"))
    )
    (comp (ref "C4-44")
      (value "COLOR")
      (footprint "eagle-import:CHIPLED_0603_NOOUTLINE")
      (libsource (lib "eagle-import") (part "LED0603_NOOUTLINE"))
    )
    (comp (ref "C4-45")
      (value "COLOR")
      (footprint "eagle-import:CHIPLED_0603_NOOUTLINE")
      (libsource (lib "eagle-import") (part "LED0603_NOOUTLINE"))
    )
    (comp (ref "C4-46")
      (value "COLOR")
      (footprint "eagle-import:CHIPLED_0603_NOOUTLINE")
      (libsource (lib "eagle-import") (part "LED0603_NOOUTLINE"))
    )
    (comp (ref "C4-47")
      (value "COLOR")
      (footprint "eagle-import:CHIPLED_0603_NOOUTLINE")
      (libsource (lib "eagle-import") (part "LED0603_NOOUTLINE"))
    )
    (comp (ref "C4-48")
      (value "COLOR")
      (footprint "eagle-import:CHIPLED_0603_NOOUTLINE")
      (libsource (lib "eagle-import") (part "LED0603_NOOUTLINE"))
    )
    (comp (ref "C5-33")
      (value "COLOR")
      (footprint "eagle-import:CHIPLED_0603_NOOUTLINE")
      (libsource (lib "eagle-import") (part "LED0603_NOOUTLINE"))
    )
    (comp (ref "C5-34")
      (value "COLOR")
      (footprint "eagle-import:CHIPLED_0603_NOOUTLINE")
      (libsource (lib "eagle-import") (part "LED0603_NOOUTLINE"))
    )
    (comp (ref "C5-35")
      (value "COLOR")
      (footprint "eagle-import:CHIPLED_0603_NOOUTLINE")
      (libsource (lib "eagle-import") (part "LED0603_NOOUTLINE"))
    )
    (comp (ref "C5-36")
      (value "COLOR")
      (footprint "eagle-import:CHIPLED_0603_NOOUTLINE")
      (libsource (lib "eagle-import") (part "LED0603_NOOUTLINE"))
    )
    (comp (ref "C5-37")
      (value "COLOR")
      (footprint "eagle-import:CHIPLED_0603_NOOUTLINE")
      (libsource (lib "eagle-import") (part "LED0603_NOOUTLINE"))
    )
    (comp (ref "C5-38")
      (value "COLOR")
      (footprint "eagle-import:CHIPLED_0603_NOOUTLINE")
      (libsource (lib "eagle-import") (part "LED0603_NOOUTLINE"))
    )
    (comp (ref "C5-39")
      (value "COLOR")
      (footprint "eagle-import:CHIPLED_0603_NOOUTLINE")
      (libsource (lib "eagle-import") (part "LED0603_NOOUTLINE"))
    )
    (comp (ref "C5-40")
      (value "COLOR")
      (footprint "eagle-import:CHIPLED_0603_NOOUTLINE")
      (libsource (lib "eagle-import") (part "LED0603_NOOUTLINE"))
    )
    (comp (ref "C5-41")
      (value "COLOR")
      (footprint "eagle-import:CHIPLED_0603_NOOUTLINE")
      (libsource (lib "eagle-import") (part "LED0603_NOOUTLINE"))
    )
    (comp (ref "C5-42")
      (value "COLOR")
      (footprint "eagle-import:CHIPLED_0603_NOOUTLINE")
      (libsource (lib "eagle-import") (part "LED0603_NOOUTLINE"))
    )
    (comp (ref "C5-43")
      (value "COLOR")
      (footprint "eagle-import:CHIPLED_0603_NOOUTLINE")
      (libsource (lib "eagle-import") (part "LED0603_NOOUTLINE"))
    )
    (comp (ref "C5-44")
      (value "COLOR")
      (footprint "eagle-import:CHIPLED_0603_NOOUTLINE")
      (libsource (lib "eagle-import") (part "LED0603_NOOUTLINE"))
    )
    (comp (ref "C5-45")
      (value "COLOR")
      (footprint "eagle-import:CHIPLED_0603_NOOUTLINE")
      (libsource (lib "eagle-import") (part "LED0603_NOOUTLINE"))
    )
    (comp (ref "C5-46")
      (value "COLOR")
      (footprint "eagle-import:CHIPLED_0603_NOOUTLINE")
      (libsource (lib "eagle-import") (part "LED0603_NOOUTLINE"))
    )
    (comp (ref "C5-47")
      (value "COLOR")
      (footprint "eagle-import:CHIPLED_0603_NOOUTLINE")
      (libsource (lib "eagle-import") (part "LED0603_NOOUTLINE"))
    )
    (comp (ref "C5-48")
      (value "COLOR")
      (footprint "eagle-import:CHIPLED_0603_NOOUTLINE")
      (libsource (lib "eagle-import") (part "LED0603_NOOUTLINE"))
    )
    (comp (ref "C6-33")
      (value "COLOR")
      (footprint "eagle-import:CHIPLED_0603_NOOUTLINE")
      (libsource (lib "eagle-import") (part "LED0603_NOOUTLINE"))
    )
    (comp (ref "C6-34")
      (value "COLOR")
      (footprint "eagle-import:CHIPLED_0603_NOOUTLINE")
      (libsource (lib "eagle-import") (part "LED0603_NOOUTLINE"))
    )
    (comp (ref "C6-35")
      (value "COLOR")
      (footprint "eagle-import:CHIPLED_0603_NOOUTLINE")
      (libsource (lib "eagle-import") (part "LED0603_NOOUTLINE"))
    )
    (comp (ref "C6-36")
      (value "COLOR")
      (footprint "eagle-import:CHIPLED_0603_NOOUTLINE")
      (libsource (lib "eagle-import") (part "LED0603_NOOUTLINE"))
    )
    (comp (ref "C6-37")
      (value "COLOR")
      (footprint "eagle-import:CHIPLED_0603_NOOUTLINE")
      (libsource (lib "eagle-import") (part "LED0603_NOOUTLINE"))
    )
    (comp (ref "C6-38")
      (value "COLOR")
      (footprint "eagle-import:CHIPLED_0603_NOOUTLINE")
      (libsource (lib "eagle-import") (part "LED0603_NOOUTLINE"))
    )
    (comp (ref "C6-39")
      (value "COLOR")
      (footprint "eagle-import:CHIPLED_0603_NOOUTLINE")
      (libsource (lib "eagle-import") (part "LED0603_NOOUTLINE"))
    )
    (comp (ref "C6-40")
      (value "COLOR")
      (footprint "eagle-import:CHIPLED_0603_NOOUTLINE")
      (libsource (lib "eagle-import") (part "LED0603_NOOUTLINE"))
    )
    (comp (ref "C6-41")
      (value "COLOR")
      (footprint "eagle-import:CHIPLED_0603_NOOUTLINE")
      (libsource (lib "eagle-import") (part "LED0603_NOOUTLINE"))
    )
    (comp (ref "C6-42")
      (value "COLOR")
      (footprint "eagle-import:CHIPLED_0603_NOOUTLINE")
      (libsource (lib "eagle-import") (part "LED0603_NOOUTLINE"))
    )
    (comp (ref "C6-43")
      (value "COLOR")
      (footprint "eagle-import:CHIPLED_0603_NOOUTLINE")
      (libsource (lib "eagle-import") (part "LED0603_NOOUTLINE"))
    )
    (comp (ref "C6-44")
      (value "COLOR")
      (footprint "eagle-import:CHIPLED_0603_NOOUTLINE")
      (libsource (lib "eagle-import") (part "LED0603_NOOUTLINE"))
    )
    (comp (ref "C6-45")
      (value "COLOR")
      (footprint "eagle-import:CHIPLED_0603_NOOUTLINE")
      (libsource (lib "eagle-import") (part "LED0603_NOOUTLINE"))
    )
    (comp (ref "C6-46")
      (value "COLOR")
      (footprint "eagle-import:CHIPLED_0603_NOOUTLINE")
      (libsource (lib "eagle-import") (part "LED0603_NOOUTLINE"))
    )
    (comp (ref "C6-47")
      (value "COLOR")
      (footprint "eagle-import:CHIPLED_0603_NOOUTLINE")
      (libsource (lib "eagle-import") (part "LED0603_NOOUTLINE"))
    )
    (comp (ref "C6-48")
      (value "COLOR")
      (footprint "eagle-import:CHIPLED_0603_NOOUTLINE")
      (libsource (lib "eagle-import") (part "LED0603_NOOUTLINE"))
    )
    (comp (ref "C7-33")
      (value "COLOR")
      (footprint "eagle-import:CHIPLED_0603_NOOUTLINE")
      (libsource (lib "eagle-import") (part "LED0603_NOOUTLINE"))
    )
    (comp (ref "C7-34")
      (value "COLOR")
      (footprint "eagle-import:CHIPLED_0603_NOOUTLINE")
      (libsource (lib "eagle-import") (part "LED0603_NOOUTLINE"))
    )
    (comp (ref "C7-35")
      (value "COLOR")
      (footprint "eagle-import:CHIPLED_0603_NOOUTLINE")
      (libsource (lib "eagle-import") (part "LED0603_NOOUTLINE"))
    )
    (comp (ref "C7-36")
      (value "COLOR")
      (footprint "eagle-import:CHIPLED_0603_NOOUTLINE")
      (libsource (lib "eagle-import") (part "LED0603_NOOUTLINE"))
    )
    (comp (ref "C7-37")
      (value "COLOR")
      (footprint "eagle-import:CHIPLED_0603_NOOUTLINE")
      (libsource (lib "eagle-import") (part "LED0603_NOOUTLINE"))
    )
    (comp (ref "C7-38")
      (value "COLOR")
      (footprint "eagle-import:CHIPLED_0603_NOOUTLINE")
      (libsource (lib "eagle-import") (part "LED0603_NOOUTLINE"))
    )
    (comp (ref "C7-39")
      (value "COLOR")
      (footprint "eagle-import:CHIPLED_0603_NOOUTLINE")
      (libsource (lib "eagle-import") (part "LED0603_NOOUTLINE"))
    )
    (comp (ref "C7-40")
      (value "COLOR")
      (footprint "eagle-import:CHIPLED_0603_NOOUTLINE")
      (libsource (lib "eagle-import") (part "LED0603_NOOUTLINE"))
    )
    (comp (ref "C7-41")
      (value "COLOR")
      (footprint "eagle-import:CHIPLED_0603_NOOUTLINE")
      (libsource (lib "eagle-import") (part "LED0603_NOOUTLINE"))
    )
    (comp (ref "C7-42")
      (value "COLOR")
      (footprint "eagle-import:CHIPLED_0603_NOOUTLINE")
      (libsource (lib "eagle-import") (part "LED0603_NOOUTLINE"))
    )
    (comp (ref "C7-43")
      (value "COLOR")
      (footprint "eagle-import:CHIPLED_0603_NOOUTLINE")
      (libsource (lib "eagle-import") (part "LED0603_NOOUTLINE"))
    )
    (comp (ref "C7-44")
      (value "COLOR")
      (footprint "eagle-import:CHIPLED_0603_NOOUTLINE")
      (libsource (lib "eagle-import") (part "LED0603_NOOUTLINE"))
    )
    (comp (ref "C7-45")
      (value "COLOR")
      (footprint "eagle-import:CHIPLED_0603_NOOUTLINE")
      (libsource (lib "eagle-import") (part "LED0603_NOOUTLINE"))
    )
    (comp (ref "C7-46")
      (value "COLOR")
      (footprint "eagle-import:CHIPLED_0603_NOOUTLINE")
      (libsource (lib "eagle-import") (part "LED0603_NOOUTLINE"))
    )
    (comp (ref "C7-47")
      (value "COLOR")
      (footprint "eagle-import:CHIPLED_0603_NOOUTLINE")
      (libsource (lib "eagle-import") (part "LED0603_NOOUTLINE"))
    )
    (comp (ref "C7-48")
      (value "COLOR")
      (footprint "eagle-import:CHIPLED_0603_NOOUTLINE")
      (libsource (lib "eagle-import") (part "LED0603_NOOUTLINE"))
    )
    (comp (ref "C8-33")
      (value "COLOR")
      (footprint "eagle-import:CHIPLED_0603_NOOUTLINE")
      (libsource (lib "eagle-import") (part "LED0603_NOOUTLINE"))
    )
    (comp (ref "C8-34")
      (value "COLOR")
      (footprint "eagle-import:CHIPLED_0603_NOOUTLINE")
      (libsource (lib "eagle-import") (part "LED0603_NOOUTLINE"))
    )
    (comp (ref "C8-35")
      (value "COLOR")
      (footprint "eagle-import:CHIPLED_0603_NOOUTLINE")
      (libsource (lib "eagle-import") (part "LED0603_NOOUTLINE"))
    )
    (comp (ref "C8-36")
      (value "COLOR")
      (footprint "eagle-import:CHIPLED_0603_NOOUTLINE")
      (libsource (lib "eagle-import") (part "LED0603_NOOUTLINE"))
    )
    (comp (ref "C8-37")
      (value "COLOR")
      (footprint "eagle-import:CHIPLED_0603_NOOUTLINE")
      (libsource (lib "eagle-import") (part "LED0603_NOOUTLINE"))
    )
    (comp (ref "C8-38")
      (value "COLOR")
      (footprint "eagle-import:CHIPLED_0603_NOOUTLINE")
      (libsource (lib "eagle-import") (part "LED0603_NOOUTLINE"))
    )
    (comp (ref "C8-39")
      (value "COLOR")
      (footprint "eagle-import:CHIPLED_0603_NOOUTLINE")
      (libsource (lib "eagle-import") (part "LED0603_NOOUTLINE"))
    )
    (comp (ref "C8-40")
      (value "COLOR")
      (footprint "eagle-import:CHIPLED_0603_NOOUTLINE")
      (libsource (lib "eagle-import") (part "LED0603_NOOUTLINE"))
    )
    (comp (ref "C8-41")
      (value "COLOR")
      (footprint "eagle-import:CHIPLED_0603_NOOUTLINE")
      (libsource (lib "eagle-import") (part "LED0603_NOOUTLINE"))
    )
    (comp (ref "C8-42")
      (value "COLOR")
      (footprint "eagle-import:CHIPLED_0603_NOOUTLINE")
      (libsource (lib "eagle-import") (part "LED0603_NOOUTLINE"))
    )
    (comp (ref "C8-43")
      (value "COLOR")
      (footprint "eagle-import:CHIPLED_0603_NOOUTLINE")
      (libsource (lib "eagle-import") (part "LED0603_NOOUTLINE"))
    )
    (comp (ref "C8-44")
      (value "COLOR")
      (footprint "eagle-import:CHIPLED_0603_NOOUTLINE")
      (libsource (lib "eagle-import") (part "LED0603_NOOUTLINE"))
    )
    (comp (ref "C8-45")
      (value "COLOR")
      (footprint "eagle-import:CHIPLED_0603_NOOUTLINE")
      (libsource (lib "eagle-import") (part "LED0603_NOOUTLINE"))
    )
    (comp (ref "C8-46")
      (value "COLOR")
      (footprint "eagle-import:CHIPLED_0603_NOOUTLINE")
      (libsource (lib "eagle-import") (part "LED0603_NOOUTLINE"))
    )
    (comp (ref "C8-47")
      (value "COLOR")
      (footprint "eagle-import:CHIPLED_0603_NOOUTLINE")
      (libsource (lib "eagle-import") (part "LED0603_NOOUTLINE"))
    )
    (comp (ref "C8-48")
      (value "COLOR")
      (footprint "eagle-import:CHIPLED_0603_NOOUTLINE")
      (libsource (lib "eagle-import") (part "LED0603_NOOUTLINE"))
    )
    (comp (ref "C9-33")
      (value "COLOR")
      (footprint "eagle-import:CHIPLED_0603_NOOUTLINE")
      (libsource (lib "eagle-import") (part "LED0603_NOOUTLINE"))
    )
    (comp (ref "C9-34")
      (value "COLOR")
      (footprint "eagle-import:CHIPLED_0603_NOOUTLINE")
      (libsource (lib "eagle-import") (part "LED0603_NOOUTLINE"))
    )
    (comp (ref "C9-35")
      (value "COLOR")
      (footprint "eagle-import:CHIPLED_0603_NOOUTLINE")
      (libsource (lib "eagle-import") (part "LED0603_NOOUTLINE"))
    )
    (comp (ref "C9-36")
      (value "COLOR")
      (footprint "eagle-import:CHIPLED_0603_NOOUTLINE")
      (libsource (lib "eagle-import") (part "LED0603_NOOUTLINE"))
    )
    (comp (ref "C9-37")
      (value "COLOR")
      (footprint "eagle-import:CHIPLED_0603_NOOUTLINE")
      (libsource (lib "eagle-import") (part "LED0603_NOOUTLINE"))
    )
    (comp (ref "C9-38")
      (value "COLOR")
      (footprint "eagle-import:CHIPLED_0603_NOOUTLINE")
      (libsource (lib "eagle-import") (part "LED0603_NOOUTLINE"))
    )
    (comp (ref "C9-39")
      (value "COLOR")
      (footprint "eagle-import:CHIPLED_0603_NOOUTLINE")
      (libsource (lib "eagle-import") (part "LED0603_NOOUTLINE"))
    )
    (comp (ref "C9-40")
      (value "COLOR")
      (footprint "eagle-import:CHIPLED_0603_NOOUTLINE")
      (libsource (lib "eagle-import") (part "LED0603_NOOUTLINE"))
    )
    (comp (ref "C9-41")
      (value "COLOR")
      (footprint "eagle-import:CHIPLED_0603_NOOUTLINE")
      (libsource (lib "eagle-import") (part "LED0603_NOOUTLINE"))
    )
    (comp (ref "C9-42")
      (value "COLOR")
      (footprint "eagle-import:CHIPLED_0603_NOOUTLINE")
      (libsource (lib "eagle-import") (part "LED0603_NOOUTLINE"))
    )
    (comp (ref "C9-43")
      (value "COLOR")
      (footprint "eagle-import:CHIPLED_0603_NOOUTLINE")
      (libsource (lib "eagle-import") (part "LED0603_NOOUTLINE"))
    )
    (comp (ref "C9-44")
      (value "COLOR")
      (footprint "eagle-import:CHIPLED_0603_NOOUTLINE")
      (libsource (lib "eagle-import") (part "LED0603_NOOUTLINE"))
    )
    (comp (ref "C9-45")
      (value "COLOR")
      (footprint "eagle-import:CHIPLED_0603_NOOUTLINE")
      (libsource (lib "eagle-import") (part "LED0603_NOOUTLINE"))
    )
    (comp (ref "C9-46")
      (value "COLOR")
      (footprint "eagle-import:CHIPLED_0603_NOOUTLINE")
      (libsource (lib "eagle-import") (part "LED0603_NOOUTLINE"))
    )
    (comp (ref "C9-47")
      (value "COLOR")
      (footprint "eagle-import:CHIPLED_0603_NOOUTLINE")
      (libsource (lib "eagle-import") (part "LED0603_NOOUTLINE"))
    )
    (comp (ref "C9-48")
      (value "COLOR")
      (footprint "eagle-import:CHIPLED_0603_NOOUTLINE")
      (libsource (lib "eagle-import") (part "LED0603_NOOUTLINE"))
    )
    (comp (ref "C2")
      (value "0.1uF")
      (footprint "eagle-import:0603")
      (libsource (lib "eagle-import") (part "0.1UF-0603-25V-(+80/-20%)"))
    )
    (comp (ref "C5")
      (value "0.1uF")
      (footprint "eagle-import:0603")
      (libsource (lib "eagle-import") (part "0.1UF-0603-25V-(+80/-20%)"))
    )
    (comp (ref "C111")
      (value "10uF")
      (footprint "eagle-import:1206")
      (libsource (lib "eagle-import") (part "10UF-1206-6.3V-20%"))
    )
    (comp (ref "JP2")
      (value "FIDUCIAL1X2")
      (footprint "eagle-import:FIDUCIAL-1X2")
      (libsource (lib "eagle-import") (part "FIDUCIAL1X2"))
    )
    (comp (ref "JP3")
      (value "FIDUCIAL1X2")
      (footprint "eagle-import:FIDUCIAL-1X2")
      (libsource (lib "eagle-import") (part "FIDUCIAL1X2"))
    )
    (comp (ref "JP4")
      (value "FIDUCIAL1X2")
      (footprint "eagle-import:FIDUCIAL-1X2")
      (libsource (lib "eagle-import") (part "FIDUCIAL1X2"))
    )
    (comp (ref "R1")
      (value "20k")
      (footprint "eagle-import:0603")
      (libsource (lib "eagle-import") (part "20KOHM-0603-1/10W-1%"))
    )
    (comp (ref "R2")
      (value "20k")
      (footprint "eagle-import:0603")
      (libsource (lib "eagle-import") (part "20KOHM-0603-1/10W-1%"))
    )
    (comp (ref "R3")
      (value "20k")
      (footprint "eagle-import:0603")
      (libsource (lib "eagle-import") (part "20KOHM-0603-1/10W-1%"))
    )
    (comp (ref "R4")
      (value "4.7k")
      (footprint "eagle-import:0603")
      (libsource (lib "eagle-import") (part "4.7KOHM-0603-1/10W-1%"))
    )
    (comp (ref "R5")
      (value "4.7k")
      (footprint "eagle-import:0603")
      (libsource (lib "eagle-import") (part "4.7KOHM-0603-1/10W-1%"))
    )
    (comp (ref "R14")
      (value "20k")
      (footprint "eagle-import:0603")
      (libsource (lib "eagle-import") (part "20KOHM-0603-1/10W-1%"))
    )
    (comp (ref "U4")
      (value "IS31FL3731")
      (footprint "eagle-import:QFN28")
      (libsource (lib "eagle-import") (part "IS31FL3731"))
    )
    (comp (ref "C13")
      (value "10uF")
      (footprint "eagle-import:1206")
      (libsource (lib "eagle-import") (part "10UF-1206-6.3V-20%"))
    )
    (comp (ref "C14")
      (value "0.1uF")
      (footprint "eagle-import:0603")
      (libsource (lib "eagle-import") (part "0.1UF-0603-25V-(+80/-20%)"))
    )
    (comp (ref "C15")
      (value "0.1uF")
      (footprint "eagle-import:0603")
      (libsource (lib "eagle-import") (part "0.1UF-0603-25V-(+80/-20%)"))
    )
    (comp (ref "R26")
      (value "20k")
      (footprint "eagle-import:0603")
      (libsource (lib "eagle-import") (part "20KOHM-0603-1/10W-1%"))
    )
    (comp (ref "R28")
      (value "20k")
      (footprint "eagle-import:0603")
      (libsource (lib "eagle-import") (part "20KOHM-0603-1/10W-1%"))
    )
    (comp (ref "R31")
      (value "20k")
      (footprint "eagle-import:0603")
      (libsource (lib "eagle-import") (part "20KOHM-0603-1/10W-1%"))
    )
    (comp (ref "U5")
      (value "IS31FL3731")
      (footprint "eagle-import:QFN28")
      (libsource (lib "eagle-import") (part "IS31FL3731"))
    )
    (comp (ref "C1-49")
      (value "COLOR")
      (footprint "eagle-import:CHIPLED_0603_NOOUTLINE")
      (libsource (lib "eagle-import") (part "LED0603_NOOUTLINE"))
    )
    (comp (ref "C1-50")
      (value "COLOR")
      (footprint "eagle-import:CHIPLED_0603_NOOUTLINE")
      (libsource (lib "eagle-import") (part "LED0603_NOOUTLINE"))
    )
    (comp (ref "C1-51")
      (value "COLOR")
      (footprint "eagle-import:CHIPLED_0603_NOOUTLINE")
      (libsource (lib "eagle-import") (part "LED0603_NOOUTLINE"))
    )
    (comp (ref "C1-52")
      (value "COLOR")
      (footprint "eagle-import:CHIPLED_0603_NOOUTLINE")
      (libsource (lib "eagle-import") (part "LED0603_NOOUTLINE"))
    )
    (comp (ref "C1-53")
      (value "COLOR")
      (footprint "eagle-import:CHIPLED_0603_NOOUTLINE")
      (libsource (lib "eagle-import") (part "LED0603_NOOUTLINE"))
    )
    (comp (ref "C1-54")
      (value "COLOR")
      (footprint "eagle-import:CHIPLED_0603_NOOUTLINE")
      (libsource (lib "eagle-import") (part "LED0603_NOOUTLINE"))
    )
    (comp (ref "C1-55")
      (value "COLOR")
      (footprint "eagle-import:CHIPLED_0603_NOOUTLINE")
      (libsource (lib "eagle-import") (part "LED0603_NOOUTLINE"))
    )
    (comp (ref "C1-56")
      (value "COLOR")
      (footprint "eagle-import:CHIPLED_0603_NOOUTLINE")
      (libsource (lib "eagle-import") (part "LED0603_NOOUTLINE"))
    )
    (comp (ref "C1-57")
      (value "COLOR")
      (footprint "eagle-import:CHIPLED_0603_NOOUTLINE")
      (libsource (lib "eagle-import") (part "LED0603_NOOUTLINE"))
    )
    (comp (ref "C1-58")
      (value "COLOR")
      (footprint "eagle-import:CHIPLED_0603_NOOUTLINE")
      (libsource (lib "eagle-import") (part "LED0603_NOOUTLINE"))
    )
    (comp (ref "C1-59")
      (value "COLOR")
      (footprint "eagle-import:CHIPLED_0603_NOOUTLINE")
      (libsource (lib "eagle-import") (part "LED0603_NOOUTLINE"))
    )
    (comp (ref "C1-60")
      (value "COLOR")
      (footprint "eagle-import:CHIPLED_0603_NOOUTLINE")
      (libsource (lib "eagle-import") (part "LED0603_NOOUTLINE"))
    )
    (comp (ref "C1-61")
      (value "COLOR")
      (footprint "eagle-import:CHIPLED_0603_NOOUTLINE")
      (libsource (lib "eagle-import") (part "LED0603_NOOUTLINE"))
    )
    (comp (ref "C1-62")
      (value "COLOR")
      (footprint "eagle-import:CHIPLED_0603_NOOUTLINE")
      (libsource (lib "eagle-import") (part "LED0603_NOOUTLINE"))
    )
    (comp (ref "C1-63")
      (value "COLOR")
      (footprint "eagle-import:CHIPLED_0603_NOOUTLINE")
      (libsource (lib "eagle-import") (part "LED0603_NOOUTLINE"))
    )
    (comp (ref "C1-64")
      (value "COLOR")
      (footprint "eagle-import:CHIPLED_0603_NOOUTLINE")
      (libsource (lib "eagle-import") (part "LED0603_NOOUTLINE"))
    )
    (comp (ref "C2-49")
      (value "COLOR")
      (footprint "eagle-import:CHIPLED_0603_NOOUTLINE")
      (libsource (lib "eagle-import") (part "LED0603_NOOUTLINE"))
    )
    (comp (ref "C2-50")
      (value "COLOR")
      (footprint "eagle-import:CHIPLED_0603_NOOUTLINE")
      (libsource (lib "eagle-import") (part "LED0603_NOOUTLINE"))
    )
    (comp (ref "C2-51")
      (value "COLOR")
      (footprint "eagle-import:CHIPLED_0603_NOOUTLINE")
      (libsource (lib "eagle-import") (part "LED0603_NOOUTLINE"))
    )
    (comp (ref "C2-52")
      (value "COLOR")
      (footprint "eagle-import:CHIPLED_0603_NOOUTLINE")
      (libsource (lib "eagle-import") (part "LED0603_NOOUTLINE"))
    )
    (comp (ref "C2-53")
      (value "COLOR")
      (footprint "eagle-import:CHIPLED_0603_NOOUTLINE")
      (libsource (lib "eagle-import") (part "LED0603_NOOUTLINE"))
    )
    (comp (ref "C2-54")
      (value "COLOR")
      (footprint "eagle-import:CHIPLED_0603_NOOUTLINE")
      (libsource (lib "eagle-import") (part "LED0603_NOOUTLINE"))
    )
    (comp (ref "C2-55")
      (value "COLOR")
      (footprint "eagle-import:CHIPLED_0603_NOOUTLINE")
      (libsource (lib "eagle-import") (part "LED0603_NOOUTLINE"))
    )
    (comp (ref "C2-56")
      (value "COLOR")
      (footprint "eagle-import:CHIPLED_0603_NOOUTLINE")
      (libsource (lib "eagle-import") (part "LED0603_NOOUTLINE"))
    )
    (comp (ref "C2-57")
      (value "COLOR")
      (footprint "eagle-import:CHIPLED_0603_NOOUTLINE")
      (libsource (lib "eagle-import") (part "LED0603_NOOUTLINE"))
    )
    (comp (ref "C2-58")
      (value "COLOR")
      (footprint "eagle-import:CHIPLED_0603_NOOUTLINE")
      (libsource (lib "eagle-import") (part "LED0603_NOOUTLINE"))
    )
    (comp (ref "C2-59")
      (value "COLOR")
      (footprint "eagle-import:CHIPLED_0603_NOOUTLINE")
      (libsource (lib "eagle-import") (part "LED0603_NOOUTLINE"))
    )
    (comp (ref "C2-60")
      (value "COLOR")
      (footprint "eagle-import:CHIPLED_0603_NOOUTLINE")
      (libsource (lib "eagle-import") (part "LED0603_NOOUTLINE"))
    )
    (comp (ref "C2-61")
      (value "COLOR")
      (footprint "eagle-import:CHIPLED_0603_NOOUTLINE")
      (libsource (lib "eagle-import") (part "LED0603_NOOUTLINE"))
    )
    (comp (ref "C2-62")
      (value "COLOR")
      (footprint "eagle-import:CHIPLED_0603_NOOUTLINE")
      (libsource (lib "eagle-import") (part "LED0603_NOOUTLINE"))
    )
    (comp (ref "C2-63")
      (value "COLOR")
      (footprint "eagle-import:CHIPLED_0603_NOOUTLINE")
      (libsource (lib "eagle-import") (part "LED0603_NOOUTLINE"))
    )
    (comp (ref "C2-64")
      (value "COLOR")
      (footprint "eagle-import:CHIPLED_0603_NOOUTLINE")
      (libsource (lib "eagle-import") (part "LED0603_NOOUTLINE"))
    )
    (comp (ref "C3-49")
      (value "COLOR")
      (footprint "eagle-import:CHIPLED_0603_NOOUTLINE")
      (libsource (lib "eagle-import") (part "LED0603_NOOUTLINE"))
    )
    (comp (ref "C3-50")
      (value "COLOR")
      (footprint "eagle-import:CHIPLED_0603_NOOUTLINE")
      (libsource (lib "eagle-import") (part "LED0603_NOOUTLINE"))
    )
    (comp (ref "C3-51")
      (value "COLOR")
      (footprint "eagle-import:CHIPLED_0603_NOOUTLINE")
      (libsource (lib "eagle-import") (part "LED0603_NOOUTLINE"))
    )
    (comp (ref "C3-52")
      (value "COLOR")
      (footprint "eagle-import:CHIPLED_0603_NOOUTLINE")
      (libsource (lib "eagle-import") (part "LED0603_NOOUTLINE"))
    )
    (comp (ref "C3-53")
      (value "COLOR")
      (footprint "eagle-import:CHIPLED_0603_NOOUTLINE")
      (libsource (lib "eagle-import") (part "LED0603_NOOUTLINE"))
    )
    (comp (ref "C3-54")
      (value "COLOR")
      (footprint "eagle-import:CHIPLED_0603_NOOUTLINE")
      (libsource (lib "eagle-import") (part "LED0603_NOOUTLINE"))
    )
    (comp (ref "C3-55")
      (value "COLOR")
      (footprint "eagle-import:CHIPLED_0603_NOOUTLINE")
      (libsource (lib "eagle-import") (part "LED0603_NOOUTLINE"))
    )
    (comp (ref "C3-56")
      (value "COLOR")
      (footprint "eagle-import:CHIPLED_0603_NOOUTLINE")
      (libsource (lib "eagle-import") (part "LED0603_NOOUTLINE"))
    )
    (comp (ref "C3-57")
      (value "COLOR")
      (footprint "eagle-import:CHIPLED_0603_NOOUTLINE")
      (libsource (lib "eagle-import") (part "LED0603_NOOUTLINE"))
    )
    (comp (ref "C3-58")
      (value "COLOR")
      (footprint "eagle-import:CHIPLED_0603_NOOUTLINE")
      (libsource (lib "eagle-import") (part "LED0603_NOOUTLINE"))
    )
    (comp (ref "C3-59")
      (value "COLOR")
      (footprint "eagle-import:CHIPLED_0603_NOOUTLINE")
      (libsource (lib "eagle-import") (part "LED0603_NOOUTLINE"))
    )
    (comp (ref "C3-60")
      (value "COLOR")
      (footprint "eagle-import:CHIPLED_0603_NOOUTLINE")
      (libsource (lib "eagle-import") (part "LED0603_NOOUTLINE"))
    )
    (comp (ref "C3-61")
      (value "COLOR")
      (footprint "eagle-import:CHIPLED_0603_NOOUTLINE")
      (libsource (lib "eagle-import") (part "LED0603_NOOUTLINE"))
    )
    (comp (ref "C3-62")
      (value "COLOR")
      (footprint "eagle-import:CHIPLED_0603_NOOUTLINE")
      (libsource (lib "eagle-import") (part "LED0603_NOOUTLINE"))
    )
    (comp (ref "C3-63")
      (value "COLOR")
      (footprint "eagle-import:CHIPLED_0603_NOOUTLINE")
      (libsource (lib "eagle-import") (part "LED0603_NOOUTLINE"))
    )
    (comp (ref "C3-64")
      (value "COLOR")
      (footprint "eagle-import:CHIPLED_0603_NOOUTLINE")
      (libsource (lib "eagle-import") (part "LED0603_NOOUTLINE"))
    )
    (comp (ref "C4-49")
      (value "COLOR")
      (footprint "eagle-import:CHIPLED_0603_NOOUTLINE")
      (libsource (lib "eagle-import") (part "LED0603_NOOUTLINE"))
    )
    (comp (ref "C4-50")
      (value "COLOR")
      (footprint "eagle-import:CHIPLED_0603_NOOUTLINE")
      (libsource (lib "eagle-import") (part "LED0603_NOOUTLINE"))
    )
    (comp (ref "C4-51")
      (value "COLOR")
      (footprint "eagle-import:CHIPLED_0603_NOOUTLINE")
      (libsource (lib "eagle-import") (part "LED0603_NOOUTLINE"))
    )
    (comp (ref "C4-52")
      (value "COLOR")
      (footprint "eagle-import:CHIPLED_0603_NOOUTLINE")
      (libsource (lib "eagle-import") (part "LED0603_NOOUTLINE"))
    )
    (comp (ref "C4-53")
      (value "COLOR")
      (footprint "eagle-import:CHIPLED_0603_NOOUTLINE")
      (libsource (lib "eagle-import") (part "LED0603_NOOUTLINE"))
    )
    (comp (ref "C4-54")
      (value "COLOR")
      (footprint "eagle-import:CHIPLED_0603_NOOUTLINE")
      (libsource (lib "eagle-import") (part "LED0603_NOOUTLINE"))
    )
    (comp (ref "C4-55")
      (value "COLOR")
      (footprint "eagle-import:CHIPLED_0603_NOOUTLINE")
      (libsource (lib "eagle-import") (part "LED0603_NOOUTLINE"))
    )
    (comp (ref "C4-56")
      (value "COLOR")
      (footprint "eagle-import:CHIPLED_0603_NOOUTLINE")
      (libsource (lib "eagle-import") (part "LED0603_NOOUTLINE"))
    )
    (comp (ref "C4-57")
      (value "COLOR")
      (footprint "eagle-import:CHIPLED_0603_NOOUTLINE")
      (libsource (lib "eagle-import") (part "LED0603_NOOUTLINE"))
    )
    (comp (ref "C4-58")
      (value "COLOR")
      (footprint "eagle-import:CHIPLED_0603_NOOUTLINE")
      (libsource (lib "eagle-import") (part "LED0603_NOOUTLINE"))
    )
    (comp (ref "C4-59")
      (value "COLOR")
      (footprint "eagle-import:CHIPLED_0603_NOOUTLINE")
      (libsource (lib "eagle-import") (part "LED0603_NOOUTLINE"))
    )
    (comp (ref "C4-60")
      (value "COLOR")
      (footprint "eagle-import:CHIPLED_0603_NOOUTLINE")
      (libsource (lib "eagle-import") (part "LED0603_NOOUTLINE"))
    )
    (comp (ref "C4-61")
      (value "COLOR")
      (footprint "eagle-import:CHIPLED_0603_NOOUTLINE")
      (libsource (lib "eagle-import") (part "LED0603_NOOUTLINE"))
    )
    (comp (ref "C4-62")
      (value "COLOR")
      (footprint "eagle-import:CHIPLED_0603_NOOUTLINE")
      (libsource (lib "eagle-import") (part "LED0603_NOOUTLINE"))
    )
    (comp (ref "C4-63")
      (value "COLOR")
      (footprint "eagle-import:CHIPLED_0603_NOOUTLINE")
      (libsource (lib "eagle-import") (part "LED0603_NOOUTLINE"))
    )
    (comp (ref "C4-64")
      (value "COLOR")
      (footprint "eagle-import:CHIPLED_0603_NOOUTLINE")
      (libsource (lib "eagle-import") (part "LED0603_NOOUTLINE"))
    )
    (comp (ref "C5-49")
      (value "COLOR")
      (footprint "eagle-import:CHIPLED_0603_NOOUTLINE")
      (libsource (lib "eagle-import") (part "LED0603_NOOUTLINE"))
    )
    (comp (ref "C5-50")
      (value "COLOR")
      (footprint "eagle-import:CHIPLED_0603_NOOUTLINE")
      (libsource (lib "eagle-import") (part "LED0603_NOOUTLINE"))
    )
    (comp (ref "C5-51")
      (value "COLOR")
      (footprint "eagle-import:CHIPLED_0603_NOOUTLINE")
      (libsource (lib "eagle-import") (part "LED0603_NOOUTLINE"))
    )
    (comp (ref "C5-52")
      (value "COLOR")
      (footprint "eagle-import:CHIPLED_0603_NOOUTLINE")
      (libsource (lib "eagle-import") (part "LED0603_NOOUTLINE"))
    )
    (comp (ref "C5-53")
      (value "COLOR")
      (footprint "eagle-import:CHIPLED_0603_NOOUTLINE")
      (libsource (lib "eagle-import") (part "LED0603_NOOUTLINE"))
    )
    (comp (ref "C5-54")
      (value "COLOR")
      (footprint "eagle-import:CHIPLED_0603_NOOUTLINE")
      (libsource (lib "eagle-import") (part "LED0603_NOOUTLINE"))
    )
    (comp (ref "C5-55")
      (value "COLOR")
      (footprint "eagle-import:CHIPLED_0603_NOOUTLINE")
      (libsource (lib "eagle-import") (part "LED0603_NOOUTLINE"))
    )
    (comp (ref "C5-56")
      (value "COLOR")
      (footprint "eagle-import:CHIPLED_0603_NOOUTLINE")
      (libsource (lib "eagle-import") (part "LED0603_NOOUTLINE"))
    )
    (comp (ref "C5-57")
      (value "COLOR")
      (footprint "eagle-import:CHIPLED_0603_NOOUTLINE")
      (libsource (lib "eagle-import") (part "LED0603_NOOUTLINE"))
    )
    (comp (ref "C5-58")
      (value "COLOR")
      (footprint "eagle-import:CHIPLED_0603_NOOUTLINE")
      (libsource (lib "eagle-import") (part "LED0603_NOOUTLINE"))
    )
    (comp (ref "C5-59")
      (value "COLOR")
      (footprint "eagle-import:CHIPLED_0603_NOOUTLINE")
      (libsource (lib "eagle-import") (part "LED0603_NOOUTLINE"))
    )
    (comp (ref "C5-60")
      (value "COLOR")
      (footprint "eagle-import:CHIPLED_0603_NOOUTLINE")
      (libsource (lib "eagle-import") (part "LED0603_NOOUTLINE"))
    )
    (comp (ref "C5-61")
      (value "COLOR")
      (footprint "eagle-import:CHIPLED_0603_NOOUTLINE")
      (libsource (lib "eagle-import") (part "LED0603_NOOUTLINE"))
    )
    (comp (ref "C5-62")
      (value "COLOR")
      (footprint "eagle-import:CHIPLED_0603_NOOUTLINE")
      (libsource (lib "eagle-import") (part "LED0603_NOOUTLINE"))
    )
    (comp (ref "C5-63")
      (value "COLOR")
      (footprint "eagle-import:CHIPLED_0603_NOOUTLINE")
      (libsource (lib "eagle-import") (part "LED0603_NOOUTLINE"))
    )
    (comp (ref "C5-64")
      (value "COLOR")
      (footprint "eagle-import:CHIPLED_0603_NOOUTLINE")
      (libsource (lib "eagle-import") (part "LED0603_NOOUTLINE"))
    )
    (comp (ref "C6-49")
      (value "COLOR")
      (footprint "eagle-import:CHIPLED_0603_NOOUTLINE")
      (libsource (lib "eagle-import") (part "LED0603_NOOUTLINE"))
    )
    (comp (ref "C6-50")
      (value "COLOR")
      (footprint "eagle-import:CHIPLED_0603_NOOUTLINE")
      (libsource (lib "eagle-import") (part "LED0603_NOOUTLINE"))
    )
    (comp (ref "C6-51")
      (value "COLOR")
      (footprint "eagle-import:CHIPLED_0603_NOOUTLINE")
      (libsource (lib "eagle-import") (part "LED0603_NOOUTLINE"))
    )
    (comp (ref "C6-52")
      (value "COLOR")
      (footprint "eagle-import:CHIPLED_0603_NOOUTLINE")
      (libsource (lib "eagle-import") (part "LED0603_NOOUTLINE"))
    )
    (comp (ref "C6-53")
      (value "COLOR")
      (footprint "eagle-import:CHIPLED_0603_NOOUTLINE")
      (libsource (lib "eagle-import") (part "LED0603_NOOUTLINE"))
    )
    (comp (ref "C6-54")
      (value "COLOR")
      (footprint "eagle-import:CHIPLED_0603_NOOUTLINE")
      (libsource (lib "eagle-import") (part "LED0603_NOOUTLINE"))
    )
    (comp (ref "C6-55")
      (value "COLOR")
      (footprint "eagle-import:CHIPLED_0603_NOOUTLINE")
      (libsource (lib "eagle-import") (part "LED0603_NOOUTLINE"))
    )
    (comp (ref "C6-56")
      (value "COLOR")
      (footprint "eagle-import:CHIPLED_0603_NOOUTLINE")
      (libsource (lib "eagle-import") (part "LED0603_NOOUTLINE"))
    )
    (comp (ref "C6-57")
      (value "COLOR")
      (footprint "eagle-import:CHIPLED_0603_NOOUTLINE")
      (libsource (lib "eagle-import") (part "LED0603_NOOUTLINE"))
    )
    (comp (ref "C6-58")
      (value "COLOR")
      (footprint "eagle-import:CHIPLED_0603_NOOUTLINE")
      (libsource (lib "eagle-import") (part "LED0603_NOOUTLINE"))
    )
    (comp (ref "C6-59")
      (value "COLOR")
      (footprint "eagle-import:CHIPLED_0603_NOOUTLINE")
      (libsource (lib "eagle-import") (part "LED0603_NOOUTLINE"))
    )
    (comp (ref "C6-60")
      (value "COLOR")
      (footprint "eagle-import:CHIPLED_0603_NOOUTLINE")
      (libsource (lib "eagle-import") (part "LED0603_NOOUTLINE"))
    )
    (comp (ref "C6-61")
      (value "COLOR")
      (footprint "eagle-import:CHIPLED_0603_NOOUTLINE")
      (libsource (lib "eagle-import") (part "LED0603_NOOUTLINE"))
    )
    (comp (ref "C6-62")
      (value "COLOR")
      (footprint "eagle-import:CHIPLED_0603_NOOUTLINE")
      (libsource (lib "eagle-import") (part "LED0603_NOOUTLINE"))
    )
    (comp (ref "C6-63")
      (value "COLOR")
      (footprint "eagle-import:CHIPLED_0603_NOOUTLINE")
      (libsource (lib "eagle-import") (part "LED0603_NOOUTLINE"))
    )
    (comp (ref "C6-64")
      (value "COLOR")
      (footprint "eagle-import:CHIPLED_0603_NOOUTLINE")
      (libsource (lib "eagle-import") (part "LED0603_NOOUTLINE"))
    )
    (comp (ref "C7-49")
      (value "COLOR")
      (footprint "eagle-import:CHIPLED_0603_NOOUTLINE")
      (libsource (lib "eagle-import") (part "LED0603_NOOUTLINE"))
    )
    (comp (ref "C7-50")
      (value "COLOR")
      (footprint "eagle-import:CHIPLED_0603_NOOUTLINE")
      (libsource (lib "eagle-import") (part "LED0603_NOOUTLINE"))
    )
    (comp (ref "C7-51")
      (value "COLOR")
      (footprint "eagle-import:CHIPLED_0603_NOOUTLINE")
      (libsource (lib "eagle-import") (part "LED0603_NOOUTLINE"))
    )
    (comp (ref "C7-52")
      (value "COLOR")
      (footprint "eagle-import:CHIPLED_0603_NOOUTLINE")
      (libsource (lib "eagle-import") (part "LED0603_NOOUTLINE"))
    )
    (comp (ref "C7-53")
      (value "COLOR")
      (footprint "eagle-import:CHIPLED_0603_NOOUTLINE")
      (libsource (lib "eagle-import") (part "LED0603_NOOUTLINE"))
    )
    (comp (ref "C7-54")
      (value "COLOR")
      (footprint "eagle-import:CHIPLED_0603_NOOUTLINE")
      (libsource (lib "eagle-import") (part "LED0603_NOOUTLINE"))
    )
    (comp (ref "C7-55")
      (value "COLOR")
      (footprint "eagle-import:CHIPLED_0603_NOOUTLINE")
      (libsource (lib "eagle-import") (part "LED0603_NOOUTLINE"))
    )
    (comp (ref "C7-56")
      (value "COLOR")
      (footprint "eagle-import:CHIPLED_0603_NOOUTLINE")
      (libsource (lib "eagle-import") (part "LED0603_NOOUTLINE"))
    )
    (comp (ref "C7-57")
      (value "COLOR")
      (footprint "eagle-import:CHIPLED_0603_NOOUTLINE")
      (libsource (lib "eagle-import") (part "LED0603_NOOUTLINE"))
    )
    (comp (ref "C7-58")
      (value "COLOR")
      (footprint "eagle-import:CHIPLED_0603_NOOUTLINE")
      (libsource (lib "eagle-import") (part "LED0603_NOOUTLINE"))
    )
    (comp (ref "C7-59")
      (value "COLOR")
      (footprint "eagle-import:CHIPLED_0603_NOOUTLINE")
      (libsource (lib "eagle-import") (part "LED0603_NOOUTLINE"))
    )
    (comp (ref "C7-60")
      (value "COLOR")
      (footprint "eagle-import:CHIPLED_0603_NOOUTLINE")
      (libsource (lib "eagle-import") (part "LED0603_NOOUTLINE"))
    )
    (comp (ref "C7-61")
      (value "COLOR")
      (footprint "eagle-import:CHIPLED_0603_NOOUTLINE")
      (libsource (lib "eagle-import") (part "LED0603_NOOUTLINE"))
    )
    (comp (ref "C7-62")
      (value "COLOR")
      (footprint "eagle-import:CHIPLED_0603_NOOUTLINE")
      (libsource (lib "eagle-import") (part "LED0603_NOOUTLINE"))
    )
    (comp (ref "C7-63")
      (value "COLOR")
      (footprint "eagle-import:CHIPLED_0603_NOOUTLINE")
      (libsource (lib "eagle-import") (part "LED0603_NOOUTLINE"))
    )
    (comp (ref "C7-64")
      (value "COLOR")
      (footprint "eagle-import:CHIPLED_0603_NOOUTLINE")
      (libsource (lib "eagle-import") (part "LED0603_NOOUTLINE"))
    )
    (comp (ref "C8-49")
      (value "COLOR")
      (footprint "eagle-import:CHIPLED_0603_NOOUTLINE")
      (libsource (lib "eagle-import") (part "LED0603_NOOUTLINE"))
    )
    (comp (ref "C8-50")
      (value "COLOR")
      (footprint "eagle-import:CHIPLED_0603_NOOUTLINE")
      (libsource (lib "eagle-import") (part "LED0603_NOOUTLINE"))
    )
    (comp (ref "C8-51")
      (value "COLOR")
      (footprint "eagle-import:CHIPLED_0603_NOOUTLINE")
      (libsource (lib "eagle-import") (part "LED0603_NOOUTLINE"))
    )
    (comp (ref "C8-52")
      (value "COLOR")
      (footprint "eagle-import:CHIPLED_0603_NOOUTLINE")
      (libsource (lib "eagle-import") (part "LED0603_NOOUTLINE"))
    )
    (comp (ref "C8-53")
      (value "COLOR")
      (footprint "eagle-import:CHIPLED_0603_NOOUTLINE")
      (libsource (lib "eagle-import") (part "LED0603_NOOUTLINE"))
    )
    (comp (ref "C8-54")
      (value "COLOR")
      (footprint "eagle-import:CHIPLED_0603_NOOUTLINE")
      (libsource (lib "eagle-import") (part "LED0603_NOOUTLINE"))
    )
    (comp (ref "C8-55")
      (value "COLOR")
      (footprint "eagle-import:CHIPLED_0603_NOOUTLINE")
      (libsource (lib "eagle-import") (part "LED0603_NOOUTLINE"))
    )
    (comp (ref "C8-56")
      (value "COLOR")
      (footprint "eagle-import:CHIPLED_0603_NOOUTLINE")
      (libsource (lib "eagle-import") (part "LED0603_NOOUTLINE"))
    )
    (comp (ref "C8-57")
      (value "COLOR")
      (footprint "eagle-import:CHIPLED_0603_NOOUTLINE")
      (libsource (lib "eagle-import") (part "LED0603_NOOUTLINE"))
    )
    (comp (ref "C8-58")
      (value "COLOR")
      (footprint "eagle-import:CHIPLED_0603_NOOUTLINE")
      (libsource (lib "eagle-import") (part "LED0603_NOOUTLINE"))
    )
    (comp (ref "C8-59")
      (value "COLOR")
      (footprint "eagle-import:CHIPLED_0603_NOOUTLINE")
      (libsource (lib "eagle-import") (part "LED0603_NOOUTLINE"))
    )
    (comp (ref "C8-60")
      (value "COLOR")
      (footprint "eagle-import:CHIPLED_0603_NOOUTLINE")
      (libsource (lib "eagle-import") (part "LED0603_NOOUTLINE"))
    )
    (comp (ref "C8-61")
      (value "COLOR")
      (footprint "eagle-import:CHIPLED_0603_NOOUTLINE")
      (libsource (lib "eagle-import") (part "LED0603_NOOUTLINE"))
    )
    (comp (ref "C8-62")
      (value "COLOR")
      (footprint "eagle-import:CHIPLED_0603_NOOUTLINE")
      (libsource (lib "eagle-import") (part "LED0603_NOOUTLINE"))
    )
    (comp (ref "C8-63")
      (value "COLOR")
      (footprint "eagle-import:CHIPLED_0603_NOOUTLINE")
      (libsource (lib "eagle-import") (part "LED0603_NOOUTLINE"))
    )
    (comp (ref "C8-64")
      (value "COLOR")
      (footprint "eagle-import:CHIPLED_0603_NOOUTLINE")
      (libsource (lib "eagle-import") (part "LED0603_NOOUTLINE"))
    )
    (comp (ref "C9-49")
      (value "COLOR")
      (footprint "eagle-import:CHIPLED_0603_NOOUTLINE")
      (libsource (lib "eagle-import") (part "LED0603_NOOUTLINE"))
    )
    (comp (ref "C9-50")
      (value "COLOR")
      (footprint "eagle-import:CHIPLED_0603_NOOUTLINE")
      (libsource (lib "eagle-import") (part "LED0603_NOOUTLINE"))
    )
    (comp (ref "C9-51")
      (value "COLOR")
      (footprint "eagle-import:CHIPLED_0603_NOOUTLINE")
      (libsource (lib "eagle-import") (part "LED0603_NOOUTLINE"))
    )
    (comp (ref "C9-52")
      (value "COLOR")
      (footprint "eagle-import:CHIPLED_0603_NOOUTLINE")
      (libsource (lib "eagle-import") (part "LED0603_NOOUTLINE"))
    )
    (comp (ref "C9-53")
      (value "COLOR")
      (footprint "eagle-import:CHIPLED_0603_NOOUTLINE")
      (libsource (lib "eagle-import") (part "LED0603_NOOUTLINE"))
    )
    (comp (ref "C9-54")
      (value "COLOR")
      (footprint "eagle-import:CHIPLED_0603_NOOUTLINE")
      (libsource (lib "eagle-import") (part "LED0603_NOOUTLINE"))
    )
    (comp (ref "C9-55")
      (value "COLOR")
      (footprint "eagle-import:CHIPLED_0603_NOOUTLINE")
      (libsource (lib "eagle-import") (part "LED0603_NOOUTLINE"))
    )
    (comp (ref "C9-56")
      (value "COLOR")
      (footprint "eagle-import:CHIPLED_0603_NOOUTLINE")
      (libsource (lib "eagle-import") (part "LED0603_NOOUTLINE"))
    )
    (comp (ref "C9-57")
      (value "COLOR")
      (footprint "eagle-import:CHIPLED_0603_NOOUTLINE")
      (libsource (lib "eagle-import") (part "LED0603_NOOUTLINE"))
    )
    (comp (ref "C9-58")
      (value "COLOR")
      (footprint "eagle-import:CHIPLED_0603_NOOUTLINE")
      (libsource (lib "eagle-import") (part "LED0603_NOOUTLINE"))
    )
    (comp (ref "C9-59")
      (value "COLOR")
      (footprint "eagle-import:CHIPLED_0603_NOOUTLINE")
      (libsource (lib "eagle-import") (part "LED0603_NOOUTLINE"))
    )
    (comp (ref "C9-60")
      (value "COLOR")
      (footprint "eagle-import:CHIPLED_0603_NOOUTLINE")
      (libsource (lib "eagle-import") (part "LED0603_NOOUTLINE"))
    )
    (comp (ref "C9-61")
      (value "COLOR")
      (footprint "eagle-import:CHIPLED_0603_NOOUTLINE")
      (libsource (lib "eagle-import") (part "LED0603_NOOUTLINE"))
    )
    (comp (ref "C9-62")
      (value "COLOR")
      (footprint "eagle-import:CHIPLED_0603_NOOUTLINE")
      (libsource (lib "eagle-import") (part "LED0603_NOOUTLINE"))
    )
    (comp (ref "C9-63")
      (value "COLOR")
      (footprint "eagle-import:CHIPLED_0603_NOOUTLINE")
      (libsource (lib "eagle-import") (part "LED0603_NOOUTLINE"))
    )
    (comp (ref "C9-64")
      (value "COLOR")
      (footprint "eagle-import:CHIPLED_0603_NOOUTLINE")
      (libsource (lib "eagle-import") (part "LED0603_NOOUTLINE"))
    )
    (comp (ref "C1-1")
      (value "COLOR")
      (footprint "eagle-import:CHIPLED_0603_NOOUTLINE")
      (libsource (lib "eagle-import") (part "LED0603_NOOUTLINE"))
    )
    (comp (ref "C1-2")
      (value "COLOR")
      (footprint "eagle-import:CHIPLED_0603_NOOUTLINE")
      (libsource (lib "eagle-import") (part "LED0603_NOOUTLINE"))
    )
    (comp (ref "C1-3")
      (value "COLOR")
      (footprint "eagle-import:CHIPLED_0603_NOOUTLINE")
      (libsource (lib "eagle-import") (part "LED0603_NOOUTLINE"))
    )
    (comp (ref "C1-4")
      (value "COLOR")
      (footprint "eagle-import:CHIPLED_0603_NOOUTLINE")
      (libsource (lib "eagle-import") (part "LED0603_NOOUTLINE"))
    )
    (comp (ref "C1-5")
      (value "COLOR")
      (footprint "eagle-import:CHIPLED_0603_NOOUTLINE")
      (libsource (lib "eagle-import") (part "LED0603_NOOUTLINE"))
    )
    (comp (ref "C1-6")
      (value "COLOR")
      (footprint "eagle-import:CHIPLED_0603_NOOUTLINE")
      (libsource (lib "eagle-import") (part "LED0603_NOOUTLINE"))
    )
    (comp (ref "C1-7")
      (value "COLOR")
      (footprint "eagle-import:CHIPLED_0603_NOOUTLINE")
      (libsource (lib "eagle-import") (part "LED0603_NOOUTLINE"))
    )
    (comp (ref "C1-8")
      (value "COLOR")
      (footprint "eagle-import:CHIPLED_0603_NOOUTLINE")
      (libsource (lib "eagle-import") (part "LED0603_NOOUTLINE"))
    )
    (comp (ref "C1-9")
      (value "COLOR")
      (footprint "eagle-import:CHIPLED_0603_NOOUTLINE")
      (libsource (lib "eagle-import") (part "LED0603_NOOUTLINE"))
    )
    (comp (ref "C1-10")
      (value "COLOR")
      (footprint "eagle-import:CHIPLED_0603_NOOUTLINE")
      (libsource (lib "eagle-import") (part "LED0603_NOOUTLINE"))
    )
    (comp (ref "C1-11")
      (value "COLOR")
      (footprint "eagle-import:CHIPLED_0603_NOOUTLINE")
      (libsource (lib "eagle-import") (part "LED0603_NOOUTLINE"))
    )
    (comp (ref "C1-12")
      (value "COLOR")
      (footprint "eagle-import:CHIPLED_0603_NOOUTLINE")
      (libsource (lib "eagle-import") (part "LED0603_NOOUTLINE"))
    )
    (comp (ref "C1-13")
      (value "COLOR")
      (footprint "eagle-import:CHIPLED_0603_NOOUTLINE")
      (libsource (lib "eagle-import") (part "LED0603_NOOUTLINE"))
    )
    (comp (ref "C1-14")
      (value "COLOR")
      (footprint "eagle-import:CHIPLED_0603_NOOUTLINE")
      (libsource (lib "eagle-import") (part "LED0603_NOOUTLINE"))
    )
    (comp (ref "C1-15")
      (value "COLOR")
      (footprint "eagle-import:CHIPLED_0603_NOOUTLINE")
      (libsource (lib "eagle-import") (part "LED0603_NOOUTLINE"))
    )
    (comp (ref "C1-16")
      (value "COLOR")
      (footprint "eagle-import:CHIPLED_0603_NOOUTLINE")
      (libsource (lib "eagle-import") (part "LED0603_NOOUTLINE"))
    )
    (comp (ref "C2-1")
      (value "COLOR")
      (footprint "eagle-import:CHIPLED_0603_NOOUTLINE")
      (libsource (lib "eagle-import") (part "LED0603_NOOUTLINE"))
    )
    (comp (ref "C2-2")
      (value "COLOR")
      (footprint "eagle-import:CHIPLED_0603_NOOUTLINE")
      (libsource (lib "eagle-import") (part "LED0603_NOOUTLINE"))
    )
    (comp (ref "C2-3")
      (value "COLOR")
      (footprint "eagle-import:CHIPLED_0603_NOOUTLINE")
      (libsource (lib "eagle-import") (part "LED0603_NOOUTLINE"))
    )
    (comp (ref "C2-4")
      (value "COLOR")
      (footprint "eagle-import:CHIPLED_0603_NOOUTLINE")
      (libsource (lib "eagle-import") (part "LED0603_NOOUTLINE"))
    )
    (comp (ref "C2-5")
      (value "COLOR")
      (footprint "eagle-import:CHIPLED_0603_NOOUTLINE")
      (libsource (lib "eagle-import") (part "LED0603_NOOUTLINE"))
    )
    (comp (ref "C2-6")
      (value "COLOR")
      (footprint "eagle-import:CHIPLED_0603_NOOUTLINE")
      (libsource (lib "eagle-import") (part "LED0603_NOOUTLINE"))
    )
    (comp (ref "C2-7")
      (value "COLOR")
      (footprint "eagle-import:CHIPLED_0603_NOOUTLINE")
      (libsource (lib "eagle-import") (part "LED0603_NOOUTLINE"))
    )
    (comp (ref "C2-8")
      (value "COLOR")
      (footprint "eagle-import:CHIPLED_0603_NOOUTLINE")
      (libsource (lib "eagle-import") (part "LED0603_NOOUTLINE"))
    )
    (comp (ref "C2-9")
      (value "COLOR")
      (footprint "eagle-import:CHIPLED_0603_NOOUTLINE")
      (libsource (lib "eagle-import") (part "LED0603_NOOUTLINE"))
    )
    (comp (ref "C2-10")
      (value "COLOR")
      (footprint "eagle-import:CHIPLED_0603_NOOUTLINE")
      (libsource (lib "eagle-import") (part "LED0603_NOOUTLINE"))
    )
    (comp (ref "C2-11")
      (value "COLOR")
      (footprint "eagle-import:CHIPLED_0603_NOOUTLINE")
      (libsource (lib "eagle-import") (part "LED0603_NOOUTLINE"))
    )
    (comp (ref "C2-12")
      (value "COLOR")
      (footprint "eagle-import:CHIPLED_0603_NOOUTLINE")
      (libsource (lib "eagle-import") (part "LED0603_NOOUTLINE"))
    )
    (comp (ref "C2-13")
      (value "COLOR")
      (footprint "eagle-import:CHIPLED_0603_NOOUTLINE")
      (libsource (lib "eagle-import") (part "LED0603_NOOUTLINE"))
    )
    (comp (ref "C2-14")
      (value "COLOR")
      (footprint "eagle-import:CHIPLED_0603_NOOUTLINE")
      (libsource (lib "eagle-import") (part "LED0603_NOOUTLINE"))
    )
    (comp (ref "C2-15")
      (value "COLOR")
      (footprint "eagle-import:CHIPLED_0603_NOOUTLINE")
      (libsource (lib "eagle-import") (part "LED0603_NOOUTLINE"))
    )
    (comp (ref "C2-16")
      (value "COLOR")
      (footprint "eagle-import:CHIPLED_0603_NOOUTLINE")
      (libsource (lib "eagle-import") (part "LED0603_NOOUTLINE"))
    )
    (comp (ref "C3-1")
      (value "COLOR")
      (footprint "eagle-import:CHIPLED_0603_NOOUTLINE")
      (libsource (lib "eagle-import") (part "LED0603_NOOUTLINE"))
    )
    (comp (ref "C3-2")
      (value "COLOR")
      (footprint "eagle-import:CHIPLED_0603_NOOUTLINE")
      (libsource (lib "eagle-import") (part "LED0603_NOOUTLINE"))
    )
    (comp (ref "C3-3")
      (value "COLOR")
      (footprint "eagle-import:CHIPLED_0603_NOOUTLINE")
      (libsource (lib "eagle-import") (part "LED0603_NOOUTLINE"))
    )
    (comp (ref "C3-4")
      (value "COLOR")
      (footprint "eagle-import:CHIPLED_0603_NOOUTLINE")
      (libsource (lib "eagle-import") (part "LED0603_NOOUTLINE"))
    )
    (comp (ref "C3-5")
      (value "COLOR")
      (footprint "eagle-import:CHIPLED_0603_NOOUTLINE")
      (libsource (lib "eagle-import") (part "LED0603_NOOUTLINE"))
    )
    (comp (ref "C3-6")
      (value "COLOR")
      (footprint "eagle-import:CHIPLED_0603_NOOUTLINE")
      (libsource (lib "eagle-import") (part "LED0603_NOOUTLINE"))
    )
    (comp (ref "C3-7")
      (value "COLOR")
      (footprint "eagle-import:CHIPLED_0603_NOOUTLINE")
      (libsource (lib "eagle-import") (part "LED0603_NOOUTLINE"))
    )
    (comp (ref "C3-8")
      (value "COLOR")
      (footprint "eagle-import:CHIPLED_0603_NOOUTLINE")
      (libsource (lib "eagle-import") (part "LED0603_NOOUTLINE"))
    )
    (comp (ref "C3-9")
      (value "COLOR")
      (footprint "eagle-import:CHIPLED_0603_NOOUTLINE")
      (libsource (lib "eagle-import") (part "LED0603_NOOUTLINE"))
    )
    (comp (ref "C3-10")
      (value "COLOR")
      (footprint "eagle-import:CHIPLED_0603_NOOUTLINE")
      (libsource (lib "eagle-import") (part "LED0603_NOOUTLINE"))
    )
    (comp (ref "C3-11")
      (value "COLOR")
      (footprint "eagle-import:CHIPLED_0603_NOOUTLINE")
      (libsource (lib "eagle-import") (part "LED0603_NOOUTLINE"))
    )
    (comp (ref "C3-12")
      (value "COLOR")
      (footprint "eagle-import:CHIPLED_0603_NOOUTLINE")
      (libsource (lib "eagle-import") (part "LED0603_NOOUTLINE"))
    )
    (comp (ref "C3-13")
      (value "COLOR")
      (footprint "eagle-import:CHIPLED_0603_NOOUTLINE")
      (libsource (lib "eagle-import") (part "LED0603_NOOUTLINE"))
    )
    (comp (ref "C3-14")
      (value "COLOR")
      (footprint "eagle-import:CHIPLED_0603_NOOUTLINE")
      (libsource (lib "eagle-import") (part "LED0603_NOOUTLINE"))
    )
    (comp (ref "C3-15")
      (value "COLOR")
      (footprint "eagle-import:CHIPLED_0603_NOOUTLINE")
      (libsource (lib "eagle-import") (part "LED0603_NOOUTLINE"))
    )
    (comp (ref "C3-16")
      (value "COLOR")
      (footprint "eagle-import:CHIPLED_0603_NOOUTLINE")
      (libsource (lib "eagle-import") (part "LED0603_NOOUTLINE"))
    )
    (comp (ref "C4-1")
      (value "COLOR")
      (footprint "eagle-import:CHIPLED_0603_NOOUTLINE")
      (libsource (lib "eagle-import") (part "LED0603_NOOUTLINE"))
    )
    (comp (ref "C4-2")
      (value "COLOR")
      (footprint "eagle-import:CHIPLED_0603_NOOUTLINE")
      (libsource (lib "eagle-import") (part "LED0603_NOOUTLINE"))
    )
    (comp (ref "C4-3")
      (value "COLOR")
      (footprint "eagle-import:CHIPLED_0603_NOOUTLINE")
      (libsource (lib "eagle-import") (part "LED0603_NOOUTLINE"))
    )
    (comp (ref "C4-4")
      (value "COLOR")
      (footprint "eagle-import:CHIPLED_0603_NOOUTLINE")
      (libsource (lib "eagle-import") (part "LED0603_NOOUTLINE"))
    )
    (comp (ref "C4-5")
      (value "COLOR")
      (footprint "eagle-import:CHIPLED_0603_NOOUTLINE")
      (libsource (lib "eagle-import") (part "LED0603_NOOUTLINE"))
    )
    (comp (ref "C4-6")
      (value "COLOR")
      (footprint "eagle-import:CHIPLED_0603_NOOUTLINE")
      (libsource (lib "eagle-import") (part "LED0603_NOOUTLINE"))
    )
    (comp (ref "C4-7")
      (value "COLOR")
      (footprint "eagle-import:CHIPLED_0603_NOOUTLINE")
      (libsource (lib "eagle-import") (part "LED0603_NOOUTLINE"))
    )
    (comp (ref "C4-8")
      (value "COLOR")
      (footprint "eagle-import:CHIPLED_0603_NOOUTLINE")
      (libsource (lib "eagle-import") (part "LED0603_NOOUTLINE"))
    )
    (comp (ref "C4-9")
      (value "COLOR")
      (footprint "eagle-import:CHIPLED_0603_NOOUTLINE")
      (libsource (lib "eagle-import") (part "LED0603_NOOUTLINE"))
    )
    (comp (ref "C4-10")
      (value "COLOR")
      (footprint "eagle-import:CHIPLED_0603_NOOUTLINE")
      (libsource (lib "eagle-import") (part "LED0603_NOOUTLINE"))
    )
    (comp (ref "C4-11")
      (value "COLOR")
      (footprint "eagle-import:CHIPLED_0603_NOOUTLINE")
      (libsource (lib "eagle-import") (part "LED0603_NOOUTLINE"))
    )
    (comp (ref "C4-12")
      (value "COLOR")
      (footprint "eagle-import:CHIPLED_0603_NOOUTLINE")
      (libsource (lib "eagle-import") (part "LED0603_NOOUTLINE"))
    )
    (comp (ref "C4-13")
      (value "COLOR")
      (footprint "eagle-import:CHIPLED_0603_NOOUTLINE")
      (libsource (lib "eagle-import") (part "LED0603_NOOUTLINE"))
    )
    (comp (ref "C4-14")
      (value "COLOR")
      (footprint "eagle-import:CHIPLED_0603_NOOUTLINE")
      (libsource (lib "eagle-import") (part "LED0603_NOOUTLINE"))
    )
    (comp (ref "C4-15")
      (value "COLOR")
      (footprint "eagle-import:CHIPLED_0603_NOOUTLINE")
      (libsource (lib "eagle-import") (part "LED0603_NOOUTLINE"))
    )
    (comp (ref "C4-16")
      (value "COLOR")
      (footprint "eagle-import:CHIPLED_0603_NOOUTLINE")
      (libsource (lib "eagle-import") (part "LED0603_NOOUTLINE"))
    )
    (comp (ref "C5-1")
      (value "COLOR")
      (footprint "eagle-import:CHIPLED_0603_NOOUTLINE")
      (libsource (lib "eagle-import") (part "LED0603_NOOUTLINE"))
    )
    (comp (ref "C5-2")
      (value "COLOR")
      (footprint "eagle-import:CHIPLED_0603_NOOUTLINE")
      (libsource (lib "eagle-import") (part "LED0603_NOOUTLINE"))
    )
    (comp (ref "C5-3")
      (value "COLOR")
      (footprint "eagle-import:CHIPLED_0603_NOOUTLINE")
      (libsource (lib "eagle-import") (part "LED0603_NOOUTLINE"))
    )
    (comp (ref "C5-4")
      (value "COLOR")
      (footprint "eagle-import:CHIPLED_0603_NOOUTLINE")
      (libsource (lib "eagle-import") (part "LED0603_NOOUTLINE"))
    )
    (comp (ref "C5-5")
      (value "COLOR")
      (footprint "eagle-import:CHIPLED_0603_NOOUTLINE")
      (libsource (lib "eagle-import") (part "LED0603_NOOUTLINE"))
    )
    (comp (ref "C5-6")
      (value "COLOR")
      (footprint "eagle-import:CHIPLED_0603_NOOUTLINE")
      (libsource (lib "eagle-import") (part "LED0603_NOOUTLINE"))
    )
    (comp (ref "C5-7")
      (value "COLOR")
      (footprint "eagle-import:CHIPLED_0603_NOOUTLINE")
      (libsource (lib "eagle-import") (part "LED0603_NOOUTLINE"))
    )
    (comp (ref "C5-8")
      (value "COLOR")
      (footprint "eagle-import:CHIPLED_0603_NOOUTLINE")
      (libsource (lib "eagle-import") (part "LED0603_NOOUTLINE"))
    )
    (comp (ref "C5-9")
      (value "COLOR")
      (footprint "eagle-import:CHIPLED_0603_NOOUTLINE")
      (libsource (lib "eagle-import") (part "LED0603_NOOUTLINE"))
    )
    (comp (ref "C5-10")
      (value "COLOR")
      (footprint "eagle-import:CHIPLED_0603_NOOUTLINE")
      (libsource (lib "eagle-import") (part "LED0603_NOOUTLINE"))
    )
    (comp (ref "C5-11")
      (value "COLOR")
      (footprint "eagle-import:CHIPLED_0603_NOOUTLINE")
      (libsource (lib "eagle-import") (part "LED0603_NOOUTLINE"))
    )
    (comp (ref "C5-12")
      (value "COLOR")
      (footprint "eagle-import:CHIPLED_0603_NOOUTLINE")
      (libsource (lib "eagle-import") (part "LED0603_NOOUTLINE"))
    )
    (comp (ref "C5-13")
      (value "COLOR")
      (footprint "eagle-import:CHIPLED_0603_NOOUTLINE")
      (libsource (lib "eagle-import") (part "LED0603_NOOUTLINE"))
    )
    (comp (ref "C5-14")
      (value "COLOR")
      (footprint "eagle-import:CHIPLED_0603_NOOUTLINE")
      (libsource (lib "eagle-import") (part "LED0603_NOOUTLINE"))
    )
    (comp (ref "C5-15")
      (value "COLOR")
      (footprint "eagle-import:CHIPLED_0603_NOOUTLINE")
      (libsource (lib "eagle-import") (part "LED0603_NOOUTLINE"))
    )
    (comp (ref "C5-16")
      (value "COLOR")
      (footprint "eagle-import:CHIPLED_0603_NOOUTLINE")
      (libsource (lib "eagle-import") (part "LED0603_NOOUTLINE"))
    )
    (comp (ref "C6-1")
      (value "COLOR")
      (footprint "eagle-import:CHIPLED_0603_NOOUTLINE")
      (libsource (lib "eagle-import") (part "LED0603_NOOUTLINE"))
    )
    (comp (ref "C6-2")
      (value "COLOR")
      (footprint "eagle-import:CHIPLED_0603_NOOUTLINE")
      (libsource (lib "eagle-import") (part "LED0603_NOOUTLINE"))
    )
    (comp (ref "C6-3")
      (value "COLOR")
      (footprint "eagle-import:CHIPLED_0603_NOOUTLINE")
      (libsource (lib "eagle-import") (part "LED0603_NOOUTLINE"))
    )
    (comp (ref "C6-4")
      (value "COLOR")
      (footprint "eagle-import:CHIPLED_0603_NOOUTLINE")
      (libsource (lib "eagle-import") (part "LED0603_NOOUTLINE"))
    )
    (comp (ref "C6-5")
      (value "COLOR")
      (footprint "eagle-import:CHIPLED_0603_NOOUTLINE")
      (libsource (lib "eagle-import") (part "LED0603_NOOUTLINE"))
    )
    (comp (ref "C6-6")
      (value "COLOR")
      (footprint "eagle-import:CHIPLED_0603_NOOUTLINE")
      (libsource (lib "eagle-import") (part "LED0603_NOOUTLINE"))
    )
    (comp (ref "C6-7")
      (value "COLOR")
      (footprint "eagle-import:CHIPLED_0603_NOOUTLINE")
      (libsource (lib "eagle-import") (part "LED0603_NOOUTLINE"))
    )
    (comp (ref "C6-8")
      (value "COLOR")
      (footprint "eagle-import:CHIPLED_0603_NOOUTLINE")
      (libsource (lib "eagle-import") (part "LED0603_NOOUTLINE"))
    )
    (comp (ref "C6-9")
      (value "COLOR")
      (footprint "eagle-import:CHIPLED_0603_NOOUTLINE")
      (libsource (lib "eagle-import") (part "LED0603_NOOUTLINE"))
    )
    (comp (ref "C6-10")
      (value "COLOR")
      (footprint "eagle-import:CHIPLED_0603_NOOUTLINE")
      (libsource (lib "eagle-import") (part "LED0603_NOOUTLINE"))
    )
    (comp (ref "C6-11")
      (value "COLOR")
      (footprint "eagle-import:CHIPLED_0603_NOOUTLINE")
      (libsource (lib "eagle-import") (part "LED0603_NOOUTLINE"))
    )
    (comp (ref "C6-12")
      (value "COLOR")
      (footprint "eagle-import:CHIPLED_0603_NOOUTLINE")
      (libsource (lib "eagle-import") (part "LED0603_NOOUTLINE"))
    )
    (comp (ref "C6-13")
      (value "COLOR")
      (footprint "eagle-import:CHIPLED_0603_NOOUTLINE")
      (libsource (lib "eagle-import") (part "LED0603_NOOUTLINE"))
    )
    (comp (ref "C6-14")
      (value "COLOR")
      (footprint "eagle-import:CHIPLED_0603_NOOUTLINE")
      (libsource (lib "eagle-import") (part "LED0603_NOOUTLINE"))
    )
    (comp (ref "C6-15")
      (value "COLOR")
      (footprint "eagle-import:CHIPLED_0603_NOOUTLINE")
      (libsource (lib "eagle-import") (part "LED0603_NOOUTLINE"))
    )
    (comp (ref "C6-16")
      (value "COLOR")
      (footprint "eagle-import:CHIPLED_0603_NOOUTLINE")
      (libsource (lib "eagle-import") (part "LED0603_NOOUTLINE"))
    )
    (comp (ref "C7-1")
      (value "COLOR")
      (footprint "eagle-import:CHIPLED_0603_NOOUTLINE")
      (libsource (lib "eagle-import") (part "LED0603_NOOUTLINE"))
    )
    (comp (ref "C7-2")
      (value "COLOR")
      (footprint "eagle-import:CHIPLED_0603_NOOUTLINE")
      (libsource (lib "eagle-import") (part "LED0603_NOOUTLINE"))
    )
    (comp (ref "C7-3")
      (value "COLOR")
      (footprint "eagle-import:CHIPLED_0603_NOOUTLINE")
      (libsource (lib "eagle-import") (part "LED0603_NOOUTLINE"))
    )
    (comp (ref "C7-4")
      (value "COLOR")
      (footprint "eagle-import:CHIPLED_0603_NOOUTLINE")
      (libsource (lib "eagle-import") (part "LED0603_NOOUTLINE"))
    )
    (comp (ref "C7-5")
      (value "COLOR")
      (footprint "eagle-import:CHIPLED_0603_NOOUTLINE")
      (libsource (lib "eagle-import") (part "LED0603_NOOUTLINE"))
    )
    (comp (ref "C7-6")
      (value "COLOR")
      (footprint "eagle-import:CHIPLED_0603_NOOUTLINE")
      (libsource (lib "eagle-import") (part "LED0603_NOOUTLINE"))
    )
    (comp (ref "C7-7")
      (value "COLOR")
      (footprint "eagle-import:CHIPLED_0603_NOOUTLINE")
      (libsource (lib "eagle-import") (part "LED0603_NOOUTLINE"))
    )
    (comp (ref "C7-8")
      (value "COLOR")
      (footprint "eagle-import:CHIPLED_0603_NOOUTLINE")
      (libsource (lib "eagle-import") (part "LED0603_NOOUTLINE"))
    )
    (comp (ref "C7-9")
      (value "COLOR")
      (footprint "eagle-import:CHIPLED_0603_NOOUTLINE")
      (libsource (lib "eagle-import") (part "LED0603_NOOUTLINE"))
    )
    (comp (ref "C7-10")
      (value "COLOR")
      (footprint "eagle-import:CHIPLED_0603_NOOUTLINE")
      (libsource (lib "eagle-import") (part "LED0603_NOOUTLINE"))
    )
    (comp (ref "C7-11")
      (value "COLOR")
      (footprint "eagle-import:CHIPLED_0603_NOOUTLINE")
      (libsource (lib "eagle-import") (part "LED0603_NOOUTLINE"))
    )
    (comp (ref "C7-12")
      (value "COLOR")
      (footprint "eagle-import:CHIPLED_0603_NOOUTLINE")
      (libsource (lib "eagle-import") (part "LED0603_NOOUTLINE"))
    )
    (comp (ref "C7-13")
      (value "COLOR")
      (footprint "eagle-import:CHIPLED_0603_NOOUTLINE")
      (libsource (lib "eagle-import") (part "LED0603_NOOUTLINE"))
    )
    (comp (ref "C7-14")
      (value "COLOR")
      (footprint "eagle-import:CHIPLED_0603_NOOUTLINE")
      (libsource (lib "eagle-import") (part "LED0603_NOOUTLINE"))
    )
    (comp (ref "C7-15")
      (value "COLOR")
      (footprint "eagle-import:CHIPLED_0603_NOOUTLINE")
      (libsource (lib "eagle-import") (part "LED0603_NOOUTLINE"))
    )
    (comp (ref "C7-16")
      (value "COLOR")
      (footprint "eagle-import:CHIPLED_0603_NOOUTLINE")
      (libsource (lib "eagle-import") (part "LED0603_NOOUTLINE"))
    )
    (comp (ref "C8-1")
      (value "COLOR")
      (footprint "eagle-import:CHIPLED_0603_NOOUTLINE")
      (libsource (lib "eagle-import") (part "LED0603_NOOUTLINE"))
    )
    (comp (ref "C8-2")
      (value "COLOR")
      (footprint "eagle-import:CHIPLED_0603_NOOUTLINE")
      (libsource (lib "eagle-import") (part "LED0603_NOOUTLINE"))
    )
    (comp (ref "C8-3")
      (value "COLOR")
      (footprint "eagle-import:CHIPLED_0603_NOOUTLINE")
      (libsource (lib "eagle-import") (part "LED0603_NOOUTLINE"))
    )
    (comp (ref "C8-4")
      (value "COLOR")
      (footprint "eagle-import:CHIPLED_0603_NOOUTLINE")
      (libsource (lib "eagle-import") (part "LED0603_NOOUTLINE"))
    )
    (comp (ref "C8-5")
      (value "COLOR")
      (footprint "eagle-import:CHIPLED_0603_NOOUTLINE")
      (libsource (lib "eagle-import") (part "LED0603_NOOUTLINE"))
    )
    (comp (ref "C8-6")
      (value "COLOR")
      (footprint "eagle-import:CHIPLED_0603_NOOUTLINE")
      (libsource (lib "eagle-import") (part "LED0603_NOOUTLINE"))
    )
    (comp (ref "C8-7")
      (value "COLOR")
      (footprint "eagle-import:CHIPLED_0603_NOOUTLINE")
      (libsource (lib "eagle-import") (part "LED0603_NOOUTLINE"))
    )
    (comp (ref "C8-8")
      (value "COLOR")
      (footprint "eagle-import:CHIPLED_0603_NOOUTLINE")
      (libsource (lib "eagle-import") (part "LED0603_NOOUTLINE"))
    )
    (comp (ref "C8-9")
      (value "COLOR")
      (footprint "eagle-import:CHIPLED_0603_NOOUTLINE")
      (libsource (lib "eagle-import") (part "LED0603_NOOUTLINE"))
    )
    (comp (ref "C8-10")
      (value "COLOR")
      (footprint "eagle-import:CHIPLED_0603_NOOUTLINE")
      (libsource (lib "eagle-import") (part "LED0603_NOOUTLINE"))
    )
    (comp (ref "C8-11")
      (value "COLOR")
      (footprint "eagle-import:CHIPLED_0603_NOOUTLINE")
      (libsource (lib "eagle-import") (part "LED0603_NOOUTLINE"))
    )
    (comp (ref "C8-12")
      (value "COLOR")
      (footprint "eagle-import:CHIPLED_0603_NOOUTLINE")
      (libsource (lib "eagle-import") (part "LED0603_NOOUTLINE"))
    )
    (comp (ref "C8-13")
      (value "COLOR")
      (footprint "eagle-import:CHIPLED_0603_NOOUTLINE")
      (libsource (lib "eagle-import") (part "LED0603_NOOUTLINE"))
    )
    (comp (ref "C8-14")
      (value "COLOR")
      (footprint "eagle-import:CHIPLED_0603_NOOUTLINE")
      (libsource (lib "eagle-import") (part "LED0603_NOOUTLINE"))
    )
    (comp (ref "C8-15")
      (value "COLOR")
      (footprint "eagle-import:CHIPLED_0603_NOOUTLINE")
      (libsource (lib "eagle-import") (part "LED0603_NOOUTLINE"))
    )
    (comp (ref "C8-16")
      (value "COLOR")
      (footprint "eagle-import:CHIPLED_0603_NOOUTLINE")
      (libsource (lib "eagle-import") (part "LED0603_NOOUTLINE"))
    )
    (comp (ref "C9-1")
      (value "COLOR")
      (footprint "eagle-import:CHIPLED_0603_NOOUTLINE")
      (libsource (lib "eagle-import") (part "LED0603_NOOUTLINE"))
    )
    (comp (ref "C9-2")
      (value "COLOR")
      (footprint "eagle-import:CHIPLED_0603_NOOUTLINE")
      (libsource (lib "eagle-import") (part "LED0603_NOOUTLINE"))
    )
    (comp (ref "C9-3")
      (value "COLOR")
      (footprint "eagle-import:CHIPLED_0603_NOOUTLINE")
      (libsource (lib "eagle-import") (part "LED0603_NOOUTLINE"))
    )
    (comp (ref "C9-4")
      (value "COLOR")
      (footprint "eagle-import:CHIPLED_0603_NOOUTLINE")
      (libsource (lib "eagle-import") (part "LED0603_NOOUTLINE"))
    )
    (comp (ref "C9-5")
      (value "COLOR")
      (footprint "eagle-import:CHIPLED_0603_NOOUTLINE")
      (libsource (lib "eagle-import") (part "LED0603_NOOUTLINE"))
    )
    (comp (ref "C9-6")
      (value "COLOR")
      (footprint "eagle-import:CHIPLED_0603_NOOUTLINE")
      (libsource (lib "eagle-import") (part "LED0603_NOOUTLINE"))
    )
    (comp (ref "C9-7")
      (value "COLOR")
      (footprint "eagle-import:CHIPLED_0603_NOOUTLINE")
      (libsource (lib "eagle-import") (part "LED0603_NOOUTLINE"))
    )
    (comp (ref "C9-8")
      (value "COLOR")
      (footprint "eagle-import:CHIPLED_0603_NOOUTLINE")
      (libsource (lib "eagle-import") (part "LED0603_NOOUTLINE"))
    )
    (comp (ref "C9-9")
      (value "COLOR")
      (footprint "eagle-import:CHIPLED_0603_NOOUTLINE")
      (libsource (lib "eagle-import") (part "LED0603_NOOUTLINE"))
    )
    (comp (ref "C9-10")
      (value "COLOR")
      (footprint "eagle-import:CHIPLED_0603_NOOUTLINE")
      (libsource (lib "eagle-import") (part "LED0603_NOOUTLINE"))
    )
    (comp (ref "C9-11")
      (value "COLOR")
      (footprint "eagle-import:CHIPLED_0603_NOOUTLINE")
      (libsource (lib "eagle-import") (part "LED0603_NOOUTLINE"))
    )
    (comp (ref "C9-12")
      (value "COLOR")
      (footprint "eagle-import:CHIPLED_0603_NOOUTLINE")
      (libsource (lib "eagle-import") (part "LED0603_NOOUTLINE"))
    )
    (comp (ref "C9-13")
      (value "COLOR")
      (footprint "eagle-import:CHIPLED_0603_NOOUTLINE")
      (libsource (lib "eagle-import") (part "LED0603_NOOUTLINE"))
    )
    (comp (ref "C9-14")
      (value "COLOR")
      (footprint "eagle-import:CHIPLED_0603_NOOUTLINE")
      (libsource (lib "eagle-import") (part "LED0603_NOOUTLINE"))
    )
    (comp (ref "C9-15")
      (value "COLOR")
      (footprint "eagle-import:CHIPLED_0603_NOOUTLINE")
      (libsource (lib "eagle-import") (part "LED0603_NOOUTLINE"))
    )
    (comp (ref "C9-16")
      (value "COLOR")
      (footprint "eagle-import:CHIPLED_0603_NOOUTLINE")
      (libsource (lib "eagle-import") (part "LED0603_NOOUTLINE"))
    )
    (comp (ref "C1")
      (value "2.2uF")
      (footprint "eagle-import:0603")
      (libsource (lib "eagle-import") (part "2.2UF-0603-10V-20%"))
    )
    (comp (ref "C3")
      (value "2.2uF")
      (footprint "eagle-import:0603")
      (libsource (lib "eagle-import") (part "2.2UF-0603-10V-20%"))
    )
    (comp (ref "C4")
      (value "0.1uF")
      (footprint "eagle-import:0603")
      (libsource (lib "eagle-import") (part "0.1UF-0603-25V-(+80/-20%)"))
    )
    (comp (ref "C8")
      (value "2.2uF")
      (footprint "eagle-import:0603")
      (libsource (lib "eagle-import") (part "2.2UF-0603-10V-20%"))
    )
    (comp (ref "D1")
      (value "BAT20J")
      (footprint "eagle-import:SOD-323")
      (libsource (lib "eagle-import") (part "DIODE-SCHOTTKY-BAT20J"))
    )
    (comp (ref "J3")
      (value "QWIIC_CONNECTORJS-1MM")
      (footprint "eagle-import:1X04_1MM_RA")
      (libsource (lib "eagle-import") (part "QWIIC_CONNECTORJS-1MM"))
    )
    (comp (ref "JP1")
      (value "M02-JST-2MM-SMT")
      (footprint "eagle-import:JST-2-SMD")
      (libsource (lib "eagle-import") (part "M02-JST-2MM-SMT"))
    )
    (comp (ref "LED1")
      (value "LEDCHIPLED_0805")
      (footprint "eagle-import:CHIPLED_0805")
      (libsource (lib "eagle-import") (part "LEDCHIPLED_0805"))
    )
    (comp (ref "Q3")
      (value "PMOS")
      (footprint "eagle-import:SOT23-3")
      (libsource (lib "eagle-import") (part "MOSFET_PCH-DMG2307L"))
    )
    (comp (ref "R9")
      (value "10k")
      (footprint "eagle-import:0603")
      (libsource (lib "eagle-import") (part "10KOHM-0603-1/10W-1%"))
    )
    (comp (ref "R10")
      (value "10k")
      (footprint "eagle-import:0603")
      (libsource (lib "eagle-import") (part "10KOHM-0603-1/10W-1%"))
    )
    (comp (ref "R11")
      (value "20k")
      (footprint "eagle-import:0603")
      (libsource (lib "eagle-import") (part "20KOHM-0603-1/10W-1%"))
    )
    (comp (ref "R12")
      (value "10k")
      (footprint "eagle-import:0603")
      (libsource (lib "eagle-import") (part "10KOHM-0603-1/10W-1%"))
    )
    (comp (ref "R13")
      (value "2.49k")
      (footprint "eagle-import:0603")
      (libsource (lib "eagle-import") (part "2.49KOHM-0603-1/10W-1%"))
    )
    (comp (ref "R16")
      (value "2.49k")
      (footprint "eagle-import:0603")
      (libsource (lib "eagle-import") (part "2.49KOHM-0603-1/10W-1%"))
    )
    (comp (ref "R17")
      (value "1k")
      (footprint "eagle-import:0603")
      (libsource (lib "eagle-import") (part "1KOHM-0603-1/10W-1%"))
    )
    (comp (ref "R18")
      (value "10k")
      (footprint "eagle-import:0603")
      (libsource (lib "eagle-import") (part "10KOHM-0603-1/10W-1%"))
    )
    (comp (ref "R19")
      (value "10k")
      (footprint "eagle-import:0603")
      (libsource (lib "eagle-import") (part "10KOHM-0603-1/10W-1%"))
    )
    (comp (ref "R20")
      (value "10k")
      (footprint "eagle-import:0603")
      (libsource (lib "eagle-import") (part "10KOHM-0603-1/10W-1%"))
    )
    (comp (ref "S1")
      (value "SWITCH_SK-12D02-VG5")
      (footprint "eagle-import:SK-12D02-VG5")
      (libsource (lib "eagle-import") (part "SWITCH_SK-12D02-VG5"))
    )
    (comp (ref "U$3")
      (value "ESP-PROGRAMMINGPORT")
      (footprint "eagle-import:ESP-PROGRAMMING-PORT")
      (libsource (lib "eagle-import") (part "ESP-PROGRAMMINGPORT"))
    )
    (comp (ref "U$6")
      (value "PAD-1")
      (footprint "eagle-import:PAD-1")
      (libsource (lib "eagle-import") (part "PAD-1"))
    )
    (comp (ref "U$9")
      (value "SE5218")
      (footprint "eagle-import:SOT23-5")
      (libsource (lib "eagle-import") (part "SE5218"))
    )
    (comp (ref "U$15")
      (value "USB-MICRO")
      (footprint "eagle-import:U-F-M5DD-Y-L")
      (libsource (lib "eagle-import") (part "USB-MICRO"))
    )
    (comp (ref "U$16")
      (value "PAD-1")
      (footprint "eagle-import:PAD-1")
      (libsource (lib "eagle-import") (part "PAD-1"))
    )
    (comp (ref "U$18")
      (value "PAD-1")
      (footprint "eagle-import:PAD-1")
      (libsource (lib "eagle-import") (part "PAD-1"))
    )
    (comp (ref "U$19")
      (value "PAD-1")
      (footprint "eagle-import:PAD-1")
      (libsource (lib "eagle-import") (part "PAD-1"))
    )
    (comp (ref "U$20")
      (value "PAD-1")
      (footprint "eagle-import:PAD-1")
      (libsource (lib "eagle-import") (part "PAD-1"))
    )
    (comp (ref "U$21")
      (value "PAD-1")
      (footprint "eagle-import:PAD-1")
      (libsource (lib "eagle-import") (part "PAD-1"))
    )
    (comp (ref "U1")
      (value "MCP73831")
      (footprint "eagle-import:SOT23-5")
      (libsource (lib "eagle-import") (part "MCP73831"))
    )
    (comp (ref "X1")
      (value "ESP8266-12")
      (footprint "eagle-import:ESP-12")
      (libsource (lib "eagle-import") (part "ESP-12"))
    )
    (comp (ref "C1-17")
      (value "COLOR")
      (footprint "eagle-import:CHIPLED_0603_NOOUTLINE")
      (libsource (lib "eagle-import") (part "LED0603_NOOUTLINE"))
    )
    (comp (ref "C1-18")
      (value "COLOR")
      (footprint "eagle-import:CHIPLED_0603_NOOUTLINE")
      (libsource (lib "eagle-import") (part "LED0603_NOOUTLINE"))
    )
    (comp (ref "C1-19")
      (value "COLOR")
      (footprint "eagle-import:CHIPLED_0603_NOOUTLINE")
      (libsource (lib "eagle-import") (part "LED0603_NOOUTLINE"))
    )
    (comp (ref "C1-20")
      (value "COLOR")
      (footprint "eagle-import:CHIPLED_0603_NOOUTLINE")
      (libsource (lib "eagle-import") (part "LED0603_NOOUTLINE"))
    )
    (comp (ref "C1-21")
      (value "COLOR")
      (footprint "eagle-import:CHIPLED_0603_NOOUTLINE")
      (libsource (lib "eagle-import") (part "LED0603_NOOUTLINE"))
    )
    (comp (ref "C1-22")
      (value "COLOR")
      (footprint "eagle-import:CHIPLED_0603_NOOUTLINE")
      (libsource (lib "eagle-import") (part "LED0603_NOOUTLINE"))
    )
    (comp (ref "C1-23")
      (value "COLOR")
      (footprint "eagle-import:CHIPLED_0603_NOOUTLINE")
      (libsource (lib "eagle-import") (part "LED0603_NOOUTLINE"))
    )
    (comp (ref "C1-24")
      (value "COLOR")
      (footprint "eagle-import:CHIPLED_0603_NOOUTLINE")
      (libsource (lib "eagle-import") (part "LED0603_NOOUTLINE"))
    )
    (comp (ref "C1-25")
      (value "COLOR")
      (footprint "eagle-import:CHIPLED_0603_NOOUTLINE")
      (libsource (lib "eagle-import") (part "LED0603_NOOUTLINE"))
    )
    (comp (ref "C1-26")
      (value "COLOR")
      (footprint "eagle-import:CHIPLED_0603_NOOUTLINE")
      (libsource (lib "eagle-import") (part "LED0603_NOOUTLINE"))
    )
    (comp (ref "C1-27")
      (value "COLOR")
      (footprint "eagle-import:CHIPLED_0603_NOOUTLINE")
      (libsource (lib "eagle-import") (part "LED0603_NOOUTLINE"))
    )
    (comp (ref "C1-28")
      (value "COLOR")
      (footprint "eagle-import:CHIPLED_0603_NOOUTLINE")
      (libsource (lib "eagle-import") (part "LED0603_NOOUTLINE"))
    )
    (comp (ref "C1-29")
      (value "COLOR")
      (footprint "eagle-import:CHIPLED_0603_NOOUTLINE")
      (libsource (lib "eagle-import") (part "LED0603_NOOUTLINE"))
    )
    (comp (ref "C1-30")
      (value "COLOR")
      (footprint "eagle-import:CHIPLED_0603_NOOUTLINE")
      (libsource (lib "eagle-import") (part "LED0603_NOOUTLINE"))
    )
    (comp (ref "C1-31")
      (value "COLOR")
      (footprint "eagle-import:CHIPLED_0603_NOOUTLINE")
      (libsource (lib "eagle-import") (part "LED0603_NOOUTLINE"))
    )
    (comp (ref "C1-32")
      (value "COLOR")
      (footprint "eagle-import:CHIPLED_0603_NOOUTLINE")
      (libsource (lib "eagle-import") (part "LED0603_NOOUTLINE"))
    )
    (comp (ref "C2-17")
      (value "COLOR")
      (footprint "eagle-import:CHIPLED_0603_NOOUTLINE")
      (libsource (lib "eagle-import") (part "LED0603_NOOUTLINE"))
    )
    (comp (ref "C2-18")
      (value "COLOR")
      (footprint "eagle-import:CHIPLED_0603_NOOUTLINE")
      (libsource (lib "eagle-import") (part "LED0603_NOOUTLINE"))
    )
    (comp (ref "C2-19")
      (value "COLOR")
      (footprint "eagle-import:CHIPLED_0603_NOOUTLINE")
      (libsource (lib "eagle-import") (part "LED0603_NOOUTLINE"))
    )
    (comp (ref "C2-20")
      (value "COLOR")
      (footprint "eagle-import:CHIPLED_0603_NOOUTLINE")
      (libsource (lib "eagle-import") (part "LED0603_NOOUTLINE"))
    )
    (comp (ref "C2-21")
      (value "COLOR")
      (footprint "eagle-import:CHIPLED_0603_NOOUTLINE")
      (libsource (lib "eagle-import") (part "LED0603_NOOUTLINE"))
    )
    (comp (ref "C2-22")
      (value "COLOR")
      (footprint "eagle-import:CHIPLED_0603_NOOUTLINE")
      (libsource (lib "eagle-import") (part "LED0603_NOOUTLINE"))
    )
    (comp (ref "C2-23")
      (value "COLOR")
      (footprint "eagle-import:CHIPLED_0603_NOOUTLINE")
      (libsource (lib "eagle-import") (part "LED0603_NOOUTLINE"))
    )
    (comp (ref "C2-24")
      (value "COLOR")
      (footprint "eagle-import:CHIPLED_0603_NOOUTLINE")
      (libsource (lib "eagle-import") (part "LED0603_NOOUTLINE"))
    )
    (comp (ref "C2-25")
      (value "COLOR")
      (footprint "eagle-import:CHIPLED_0603_NOOUTLINE")
      (libsource (lib "eagle-import") (part "LED0603_NOOUTLINE"))
    )
    (comp (ref "C2-26")
      (value "COLOR")
      (footprint "eagle-import:CHIPLED_0603_NOOUTLINE")
      (libsource (lib "eagle-import") (part "LED0603_NOOUTLINE"))
    )
    (comp (ref "C2-27")
      (value "COLOR")
      (footprint "eagle-import:CHIPLED_0603_NOOUTLINE")
      (libsource (lib "eagle-import") (part "LED0603_NOOUTLINE"))
    )
    (comp (ref "C2-28")
      (value "COLOR")
      (footprint "eagle-import:CHIPLED_0603_NOOUTLINE")
      (libsource (lib "eagle-import") (part "LED0603_NOOUTLINE"))
    )
    (comp (ref "C2-29")
      (value "COLOR")
      (footprint "eagle-import:CHIPLED_0603_NOOUTLINE")
      (libsource (lib "eagle-import") (part "LED0603_NOOUTLINE"))
    )
    (comp (ref "C2-30")
      (value "COLOR")
      (footprint "eagle-import:CHIPLED_0603_NOOUTLINE")
      (libsource (lib "eagle-import") (part "LED0603_NOOUTLINE"))
    )
    (comp (ref "C2-31")
      (value "COLOR")
      (footprint "eagle-import:CHIPLED_0603_NOOUTLINE")
      (libsource (lib "eagle-import") (part "LED0603_NOOUTLINE"))
    )
    (comp (ref "C2-32")
      (value "COLOR")
      (footprint "eagle-import:CHIPLED_0603_NOOUTLINE")
      (libsource (lib "eagle-import") (part "LED0603_NOOUTLINE"))
    )
    (comp (ref "C3-17")
      (value "COLOR")
      (footprint "eagle-import:CHIPLED_0603_NOOUTLINE")
      (libsource (lib "eagle-import") (part "LED0603_NOOUTLINE"))
    )
    (comp (ref "C3-18")
      (value "COLOR")
      (footprint "eagle-import:CHIPLED_0603_NOOUTLINE")
      (libsource (lib "eagle-import") (part "LED0603_NOOUTLINE"))
    )
    (comp (ref "C3-19")
      (value "COLOR")
      (footprint "eagle-import:CHIPLED_0603_NOOUTLINE")
      (libsource (lib "eagle-import") (part "LED0603_NOOUTLINE"))
    )
    (comp (ref "C3-20")
      (value "COLOR")
      (footprint "eagle-import:CHIPLED_0603_NOOUTLINE")
      (libsource (lib "eagle-import") (part "LED0603_NOOUTLINE"))
    )
    (comp (ref "C3-21")
      (value "COLOR")
      (footprint "eagle-import:CHIPLED_0603_NOOUTLINE")
      (libsource (lib "eagle-import") (part "LED0603_NOOUTLINE"))
    )
    (comp (ref "C3-22")
      (value "COLOR")
      (footprint "eagle-import:CHIPLED_0603_NOOUTLINE")
      (libsource (lib "eagle-import") (part "LED0603_NOOUTLINE"))
    )
    (comp (ref "C3-23")
      (value "COLOR")
      (footprint "eagle-import:CHIPLED_0603_NOOUTLINE")
      (libsource (lib "eagle-import") (part "LED0603_NOOUTLINE"))
    )
    (comp (ref "C3-24")
      (value "COLOR")
      (footprint "eagle-import:CHIPLED_0603_NOOUTLINE")
      (libsource (lib "eagle-import") (part "LED0603_NOOUTLINE"))
    )
    (comp (ref "C3-25")
      (value "COLOR")
      (footprint "eagle-import:CHIPLED_0603_NOOUTLINE")
      (libsource (lib "eagle-import") (part "LED0603_NOOUTLINE"))
    )
    (comp (ref "C3-26")
      (value "COLOR")
      (footprint "eagle-import:CHIPLED_0603_NOOUTLINE")
      (libsource (lib "eagle-import") (part "LED0603_NOOUTLINE"))
    )
    (comp (ref "C3-27")
      (value "COLOR")
      (footprint "eagle-import:CHIPLED_0603_NOOUTLINE")
      (libsource (lib "eagle-import") (part "LED0603_NOOUTLINE"))
    )
    (comp (ref "C3-28")
      (value "COLOR")
      (footprint "eagle-import:CHIPLED_0603_NOOUTLINE")
      (libsource (lib "eagle-import") (part "LED0603_NOOUTLINE"))
    )
    (comp (ref "C3-29")
      (value "COLOR")
      (footprint "eagle-import:CHIPLED_0603_NOOUTLINE")
      (libsource (lib "eagle-import") (part "LED0603_NOOUTLINE"))
    )
    (comp (ref "C3-30")
      (value "COLOR")
      (footprint "eagle-import:CHIPLED_0603_NOOUTLINE")
      (libsource (lib "eagle-import") (part "LED0603_NOOUTLINE"))
    )
    (comp (ref "C3-31")
      (value "COLOR")
      (footprint "eagle-import:CHIPLED_0603_NOOUTLINE")
      (libsource (lib "eagle-import") (part "LED0603_NOOUTLINE"))
    )
    (comp (ref "C3-32")
      (value "COLOR")
      (footprint "eagle-import:CHIPLED_0603_NOOUTLINE")
      (libsource (lib "eagle-import") (part "LED0603_NOOUTLINE"))
    )
    (comp (ref "C4-17")
      (value "COLOR")
      (footprint "eagle-import:CHIPLED_0603_NOOUTLINE")
      (libsource (lib "eagle-import") (part "LED0603_NOOUTLINE"))
    )
    (comp (ref "C4-18")
      (value "COLOR")
      (footprint "eagle-import:CHIPLED_0603_NOOUTLINE")
      (libsource (lib "eagle-import") (part "LED0603_NOOUTLINE"))
    )
    (comp (ref "C4-19")
      (value "COLOR")
      (footprint "eagle-import:CHIPLED_0603_NOOUTLINE")
      (libsource (lib "eagle-import") (part "LED0603_NOOUTLINE"))
    )
    (comp (ref "C4-20")
      (value "COLOR")
      (footprint "eagle-import:CHIPLED_0603_NOOUTLINE")
      (libsource (lib "eagle-import") (part "LED0603_NOOUTLINE"))
    )
    (comp (ref "C4-21")
      (value "COLOR")
      (footprint "eagle-import:CHIPLED_0603_NOOUTLINE")
      (libsource (lib "eagle-import") (part "LED0603_NOOUTLINE"))
    )
    (comp (ref "C4-22")
      (value "COLOR")
      (footprint "eagle-import:CHIPLED_0603_NOOUTLINE")
      (libsource (lib "eagle-import") (part "LED0603_NOOUTLINE"))
    )
    (comp (ref "C4-23")
      (value "COLOR")
      (footprint "eagle-import:CHIPLED_0603_NOOUTLINE")
      (libsource (lib "eagle-import") (part "LED0603_NOOUTLINE"))
    )
    (comp (ref "C4-24")
      (value "COLOR")
      (footprint "eagle-import:CHIPLED_0603_NOOUTLINE")
      (libsource (lib "eagle-import") (part "LED0603_NOOUTLINE"))
    )
    (comp (ref "C4-25")
      (value "COLOR")
      (footprint "eagle-import:CHIPLED_0603_NOOUTLINE")
      (libsource (lib "eagle-import") (part "LED0603_NOOUTLINE"))
    )
    (comp (ref "C4-26")
      (value "COLOR")
      (footprint "eagle-import:CHIPLED_0603_NOOUTLINE")
      (libsource (lib "eagle-import") (part "LED0603_NOOUTLINE"))
    )
    (comp (ref "C4-27")
      (value "COLOR")
      (footprint "eagle-import:CHIPLED_0603_NOOUTLINE")
      (libsource (lib "eagle-import") (part "LED0603_NOOUTLINE"))
    )
    (comp (ref "C4-28")
      (value "COLOR")
      (footprint "eagle-import:CHIPLED_0603_NOOUTLINE")
      (libsource (lib "eagle-import") (part "LED0603_NOOUTLINE"))
    )
    (comp (ref "C4-29")
      (value "COLOR")
      (footprint "eagle-import:CHIPLED_0603_NOOUTLINE")
      (libsource (lib "eagle-import") (part "LED0603_NOOUTLINE"))
    )
    (comp (ref "C4-30")
      (value "COLOR")
      (footprint "eagle-import:CHIPLED_0603_NOOUTLINE")
      (libsource (lib "eagle-import") (part "LED0603_NOOUTLINE"))
    )
    (comp (ref "C4-31")
      (value "COLOR")
      (footprint "eagle-import:CHIPLED_0603_NOOUTLINE")
      (libsource (lib "eagle-import") (part "LED0603_NOOUTLINE"))
    )
    (comp (ref "C4-32")
      (value "COLOR")
      (footprint "eagle-import:CHIPLED_0603_NOOUTLINE")
      (libsource (lib "eagle-import") (part "LED0603_NOOUTLINE"))
    )
    (comp (ref "C5-17")
      (value "COLOR")
      (footprint "eagle-import:CHIPLED_0603_NOOUTLINE")
      (libsource (lib "eagle-import") (part "LED0603_NOOUTLINE"))
    )
    (comp (ref "C5-18")
      (value "COLOR")
      (footprint "eagle-import:CHIPLED_0603_NOOUTLINE")
      (libsource (lib "eagle-import") (part "LED0603_NOOUTLINE"))
    )
    (comp (ref "C5-19")
      (value "COLOR")
      (footprint "eagle-import:CHIPLED_0603_NOOUTLINE")
      (libsource (lib "eagle-import") (part "LED0603_NOOUTLINE"))
    )
    (comp (ref "C5-20")
      (value "COLOR")
      (footprint "eagle-import:CHIPLED_0603_NOOUTLINE")
      (libsource (lib "eagle-import") (part "LED0603_NOOUTLINE"))
    )
    (comp (ref "C5-21")
      (value "COLOR")
      (footprint "eagle-import:CHIPLED_0603_NOOUTLINE")
      (libsource (lib "eagle-import") (part "LED0603_NOOUTLINE"))
    )
    (comp (ref "C5-22")
      (value "COLOR")
      (footprint "eagle-import:CHIPLED_0603_NOOUTLINE")
      (libsource (lib "eagle-import") (part "LED0603_NOOUTLINE"))
    )
    (comp (ref "C5-23")
      (value "COLOR")
      (footprint "eagle-import:CHIPLED_0603_NOOUTLINE")
      (libsource (lib "eagle-import") (part "LED0603_NOOUTLINE"))
    )
    (comp (ref "C5-24")
      (value "COLOR")
      (footprint "eagle-import:CHIPLED_0603_NOOUTLINE")
      (libsource (lib "eagle-import") (part "LED0603_NOOUTLINE"))
    )
    (comp (ref "C5-25")
      (value "COLOR")
      (footprint "eagle-import:CHIPLED_0603_NOOUTLINE")
      (libsource (lib "eagle-import") (part "LED0603_NOOUTLINE"))
    )
    (comp (ref "C5-26")
      (value "COLOR")
      (footprint "eagle-import:CHIPLED_0603_NOOUTLINE")
      (libsource (lib "eagle-import") (part "LED0603_NOOUTLINE"))
    )
    (comp (ref "C5-27")
      (value "COLOR")
      (footprint "eagle-import:CHIPLED_0603_NOOUTLINE")
      (libsource (lib "eagle-import") (part "LED0603_NOOUTLINE"))
    )
    (comp (ref "C5-28")
      (value "COLOR")
      (footprint "eagle-import:CHIPLED_0603_NOOUTLINE")
      (libsource (lib "eagle-import") (part "LED0603_NOOUTLINE"))
    )
    (comp (ref "C5-29")
      (value "COLOR")
      (footprint "eagle-import:CHIPLED_0603_NOOUTLINE")
      (libsource (lib "eagle-import") (part "LED0603_NOOUTLINE"))
    )
    (comp (ref "C5-30")
      (value "COLOR")
      (footprint "eagle-import:CHIPLED_0603_NOOUTLINE")
      (libsource (lib "eagle-import") (part "LED0603_NOOUTLINE"))
    )
    (comp (ref "C5-31")
      (value "COLOR")
      (footprint "eagle-import:CHIPLED_0603_NOOUTLINE")
      (libsource (lib "eagle-import") (part "LED0603_NOOUTLINE"))
    )
    (comp (ref "C5-32")
      (value "COLOR")
      (footprint "eagle-import:CHIPLED_0603_NOOUTLINE")
      (libsource (lib "eagle-import") (part "LED0603_NOOUTLINE"))
    )
    (comp (ref "C6-17")
      (value "COLOR")
      (footprint "eagle-import:CHIPLED_0603_NOOUTLINE")
      (libsource (lib "eagle-import") (part "LED0603_NOOUTLINE"))
    )
    (comp (ref "C6-18")
      (value "COLOR")
      (footprint "eagle-import:CHIPLED_0603_NOOUTLINE")
      (libsource (lib "eagle-import") (part "LED0603_NOOUTLINE"))
    )
    (comp (ref "C6-19")
      (value "COLOR")
      (footprint "eagle-import:CHIPLED_0603_NOOUTLINE")
      (libsource (lib "eagle-import") (part "LED0603_NOOUTLINE"))
    )
    (comp (ref "C6-20")
      (value "COLOR")
      (footprint "eagle-import:CHIPLED_0603_NOOUTLINE")
      (libsource (lib "eagle-import") (part "LED0603_NOOUTLINE"))
    )
    (comp (ref "C6-21")
      (value "COLOR")
      (footprint "eagle-import:CHIPLED_0603_NOOUTLINE")
      (libsource (lib "eagle-import") (part "LED0603_NOOUTLINE"))
    )
    (comp (ref "C6-22")
      (value "COLOR")
      (footprint "eagle-import:CHIPLED_0603_NOOUTLINE")
      (libsource (lib "eagle-import") (part "LED0603_NOOUTLINE"))
    )
    (comp (ref "C6-23")
      (value "COLOR")
      (footprint "eagle-import:CHIPLED_0603_NOOUTLINE")
      (libsource (lib "eagle-import") (part "LED0603_NOOUTLINE"))
    )
    (comp (ref "C6-24")
      (value "COLOR")
      (footprint "eagle-import:CHIPLED_0603_NOOUTLINE")
      (libsource (lib "eagle-import") (part "LED0603_NOOUTLINE"))
    )
    (comp (ref "C6-25")
      (value "COLOR")
      (footprint "eagle-import:CHIPLED_0603_NOOUTLINE")
      (libsource (lib "eagle-import") (part "LED0603_NOOUTLINE"))
    )
    (comp (ref "C6-26")
      (value "COLOR")
      (footprint "eagle-import:CHIPLED_0603_NOOUTLINE")
      (libsource (lib "eagle-import") (part "LED0603_NOOUTLINE"))
    )
    (comp (ref "C6-27")
      (value "COLOR")
      (footprint "eagle-import:CHIPLED_0603_NOOUTLINE")
      (libsource (lib "eagle-import") (part "LED0603_NOOUTLINE"))
    )
    (comp (ref "C6-28")
      (value "COLOR")
      (footprint "eagle-import:CHIPLED_0603_NOOUTLINE")
      (libsource (lib "eagle-import") (part "LED0603_NOOUTLINE"))
    )
    (comp (ref "C6-29")
      (value "COLOR")
      (footprint "eagle-import:CHIPLED_0603_NOOUTLINE")
      (libsource (lib "eagle-import") (part "LED0603_NOOUTLINE"))
    )
    (comp (ref "C6-30")
      (value "COLOR")
      (footprint "eagle-import:CHIPLED_0603_NOOUTLINE")
      (libsource (lib "eagle-import") (part "LED0603_NOOUTLINE"))
    )
    (comp (ref "C6-31")
      (value "COLOR")
      (footprint "eagle-import:CHIPLED_0603_NOOUTLINE")
      (libsource (lib "eagle-import") (part "LED0603_NOOUTLINE"))
    )
    (comp (ref "C6-32")
      (value "COLOR")
      (footprint "eagle-import:CHIPLED_0603_NOOUTLINE")
      (libsource (lib "eagle-import") (part "LED0603_NOOUTLINE"))
    )
    (comp (ref "C7-17")
      (value "COLOR")
      (footprint "eagle-import:CHIPLED_0603_NOOUTLINE")
      (libsource (lib "eagle-import") (part "LED0603_NOOUTLINE"))
    )
    (comp (ref "C7-18")
      (value "COLOR")
      (footprint "eagle-import:CHIPLED_0603_NOOUTLINE")
      (libsource (lib "eagle-import") (part "LED0603_NOOUTLINE"))
    )
    (comp (ref "C7-19")
      (value "COLOR")
      (footprint "eagle-import:CHIPLED_0603_NOOUTLINE")
      (libsource (lib "eagle-import") (part "LED0603_NOOUTLINE"))
    )
    (comp (ref "C7-20")
      (value "COLOR")
      (footprint "eagle-import:CHIPLED_0603_NOOUTLINE")
      (libsource (lib "eagle-import") (part "LED0603_NOOUTLINE"))
    )
    (comp (ref "C7-21")
      (value "COLOR")
      (footprint "eagle-import:CHIPLED_0603_NOOUTLINE")
      (libsource (lib "eagle-import") (part "LED0603_NOOUTLINE"))
    )
    (comp (ref "C7-22")
      (value "COLOR")
      (footprint "eagle-import:CHIPLED_0603_NOOUTLINE")
      (libsource (lib "eagle-import") (part "LED0603_NOOUTLINE"))
    )
    (comp (ref "C7-23")
      (value "COLOR")
      (footprint "eagle-import:CHIPLED_0603_NOOUTLINE")
      (libsource (lib "eagle-import") (part "LED0603_NOOUTLINE"))
    )
    (comp (ref "C7-24")
      (value "COLOR")
      (footprint "eagle-import:CHIPLED_0603_NOOUTLINE")
      (libsource (lib "eagle-import") (part "LED0603_NOOUTLINE"))
    )
    (comp (ref "C7-25")
      (value "COLOR")
      (footprint "eagle-import:CHIPLED_0603_NOOUTLINE")
      (libsource (lib "eagle-import") (part "LED0603_NOOUTLINE"))
    )
    (comp (ref "C7-26")
      (value "COLOR")
      (footprint "eagle-import:CHIPLED_0603_NOOUTLINE")
      (libsource (lib "eagle-import") (part "LED0603_NOOUTLINE"))
    )
    (comp (ref "C7-27")
      (value "COLOR")
      (footprint "eagle-import:CHIPLED_0603_NOOUTLINE")
      (libsource (lib "eagle-import") (part "LED0603_NOOUTLINE"))
    )
    (comp (ref "C7-28")
      (value "COLOR")
      (footprint "eagle-import:CHIPLED_0603_NOOUTLINE")
      (libsource (lib "eagle-import") (part "LED0603_NOOUTLINE"))
    )
    (comp (ref "C7-29")
      (value "COLOR")
      (footprint "eagle-import:CHIPLED_0603_NOOUTLINE")
      (libsource (lib "eagle-import") (part "LED0603_NOOUTLINE"))
    )
    (comp (ref "C7-30")
      (value "COLOR")
      (footprint "eagle-import:CHIPLED_0603_NOOUTLINE")
      (libsource (lib "eagle-import") (part "LED0603_NOOUTLINE"))
    )
    (comp (ref "C7-31")
      (value "COLOR")
      (footprint "eagle-import:CHIPLED_0603_NOOUTLINE")
      (libsource (lib "eagle-import") (part "LED0603_NOOUTLINE"))
    )
    (comp (ref "C7-32")
      (value "COLOR")
      (footprint "eagle-import:CHIPLED_0603_NOOUTLINE")
      (libsource (lib "eagle-import") (part "LED0603_NOOUTLINE"))
    )
    (comp (ref "C8-17")
      (value "COLOR")
      (footprint "eagle-import:CHIPLED_0603_NOOUTLINE")
      (libsource (lib "eagle-import") (part "LED0603_NOOUTLINE"))
    )
    (comp (ref "C8-18")
      (value "COLOR")
      (footprint "eagle-import:CHIPLED_0603_NOOUTLINE")
      (libsource (lib "eagle-import") (part "LED0603_NOOUTLINE"))
    )
    (comp (ref "C8-19")
      (value "COLOR")
      (footprint "eagle-import:CHIPLED_0603_NOOUTLINE")
      (libsource (lib "eagle-import") (part "LED0603_NOOUTLINE"))
    )
    (comp (ref "C8-20")
      (value "COLOR")
      (footprint "eagle-import:CHIPLED_0603_NOOUTLINE")
      (libsource (lib "eagle-import") (part "LED0603_NOOUTLINE"))
    )
    (comp (ref "C8-21")
      (value "COLOR")
      (footprint "eagle-import:CHIPLED_0603_NOOUTLINE")
      (libsource (lib "eagle-import") (part "LED0603_NOOUTLINE"))
    )
    (comp (ref "C8-22")
      (value "COLOR")
      (footprint "eagle-import:CHIPLED_0603_NOOUTLINE")
      (libsource (lib "eagle-import") (part "LED0603_NOOUTLINE"))
    )
    (comp (ref "C8-23")
      (value "COLOR")
      (footprint "eagle-import:CHIPLED_0603_NOOUTLINE")
      (libsource (lib "eagle-import") (part "LED0603_NOOUTLINE"))
    )
    (comp (ref "C8-24")
      (value "COLOR")
      (footprint "eagle-import:CHIPLED_0603_NOOUTLINE")
      (libsource (lib "eagle-import") (part "LED0603_NOOUTLINE"))
    )
    (comp (ref "C8-25")
      (value "COLOR")
      (footprint "eagle-import:CHIPLED_0603_NOOUTLINE")
      (libsource (lib "eagle-import") (part "LED0603_NOOUTLINE"))
    )
    (comp (ref "C8-26")
      (value "COLOR")
      (footprint "eagle-import:CHIPLED_0603_NOOUTLINE")
      (libsource (lib "eagle-import") (part "LED0603_NOOUTLINE"))
    )
    (comp (ref "C8-27")
      (value "COLOR")
      (footprint "eagle-import:CHIPLED_0603_NOOUTLINE")
      (libsource (lib "eagle-import") (part "LED0603_NOOUTLINE"))
    )
    (comp (ref "C8-28")
      (value "COLOR")
      (footprint "eagle-import:CHIPLED_0603_NOOUTLINE")
      (libsource (lib "eagle-import") (part "LED0603_NOOUTLINE"))
    )
    (comp (ref "C8-29")
      (value "COLOR")
      (footprint "eagle-import:CHIPLED_0603_NOOUTLINE")
      (libsource (lib "eagle-import") (part "LED0603_NOOUTLINE"))
    )
    (comp (ref "C8-30")
      (value "COLOR")
      (footprint "eagle-import:CHIPLED_0603_NOOUTLINE")
      (libsource (lib "eagle-import") (part "LED0603_NOOUTLINE"))
    )
    (comp (ref "C8-31")
      (value "COLOR")
      (footprint "eagle-import:CHIPLED_0603_NOOUTLINE")
      (libsource (lib "eagle-import") (part "LED0603_NOOUTLINE"))
    )
    (comp (ref "C8-32")
      (value "COLOR")
      (footprint "eagle-import:CHIPLED_0603_NOOUTLINE")
      (libsource (lib "eagle-import") (part "LED0603_NOOUTLINE"))
    )
    (comp (ref "C9-17")
      (value "COLOR")
      (footprint "eagle-import:CHIPLED_0603_NOOUTLINE")
      (libsource (lib "eagle-import") (part "LED0603_NOOUTLINE"))
    )
    (comp (ref "C9-18")
      (value "COLOR")
      (footprint "eagle-import:CHIPLED_0603_NOOUTLINE")
      (libsource (lib "eagle-import") (part "LED0603_NOOUTLINE"))
    )
    (comp (ref "C9-19")
      (value "COLOR")
      (footprint "eagle-import:CHIPLED_0603_NOOUTLINE")
      (libsource (lib "eagle-import") (part "LED0603_NOOUTLINE"))
    )
    (comp (ref "C9-20")
      (value "COLOR")
      (footprint "eagle-import:CHIPLED_0603_NOOUTLINE")
      (libsource (lib "eagle-import") (part "LED0603_NOOUTLINE"))
    )
    (comp (ref "C9-21")
      (value "COLOR")
      (footprint "eagle-import:CHIPLED_0603_NOOUTLINE")
      (libsource (lib "eagle-import") (part "LED0603_NOOUTLINE"))
    )
    (comp (ref "C9-22")
      (value "COLOR")
      (footprint "eagle-import:CHIPLED_0603_NOOUTLINE")
      (libsource (lib "eagle-import") (part "LED0603_NOOUTLINE"))
    )
    (comp (ref "C9-23")
      (value "COLOR")
      (footprint "eagle-import:CHIPLED_0603_NOOUTLINE")
      (libsource (lib "eagle-import") (part "LED0603_NOOUTLINE"))
    )
    (comp (ref "C9-24")
      (value "COLOR")
      (footprint "eagle-import:CHIPLED_0603_NOOUTLINE")
      (libsource (lib "eagle-import") (part "LED0603_NOOUTLINE"))
    )
    (comp (ref "C9-25")
      (value "COLOR")
      (footprint "eagle-import:CHIPLED_0603_NOOUTLINE")
      (libsource (lib "eagle-import") (part "LED0603_NOOUTLINE"))
    )
    (comp (ref "C9-26")
      (value "COLOR")
      (footprint "eagle-import:CHIPLED_0603_NOOUTLINE")
      (libsource (lib "eagle-import") (part "LED0603_NOOUTLINE"))
    )
    (comp (ref "C9-27")
      (value "COLOR")
      (footprint "eagle-import:CHIPLED_0603_NOOUTLINE")
      (libsource (lib "eagle-import") (part "LED0603_NOOUTLINE"))
    )
    (comp (ref "C9-28")
      (value "COLOR")
      (footprint "eagle-import:CHIPLED_0603_NOOUTLINE")
      (libsource (lib "eagle-import") (part "LED0603_NOOUTLINE"))
    )
    (comp (ref "C9-29")
      (value "COLOR")
      (footprint "eagle-import:CHIPLED_0603_NOOUTLINE")
      (libsource (lib "eagle-import") (part "LED0603_NOOUTLINE"))
    )
    (comp (ref "C9-30")
      (value "COLOR")
      (footprint "eagle-import:CHIPLED_0603_NOOUTLINE")
      (libsource (lib "eagle-import") (part "LED0603_NOOUTLINE"))
    )
    (comp (ref "C9-31")
      (value "COLOR")
      (footprint "eagle-import:CHIPLED_0603_NOOUTLINE")
      (libsource (lib "eagle-import") (part "LED0603_NOOUTLINE"))
    )
    (comp (ref "C9-32")
      (value "COLOR")
      (footprint "eagle-import:CHIPLED_0603_NOOUTLINE")
      (libsource (lib "eagle-import") (part "LED0603_NOOUTLINE"))
    )
  )
  (nets
    (net (code "1") (name "3.3V") (class "Default")
      (node (ref "C3") (pin "1") (pinfunction "1_1") (pintype "passive"))
      (node (ref "C4") (pin "1") (pinfunction "1_1") (pintype "passive"))
      (node (ref "J3") (pin "2") (pinfunction "2_2") (pintype "power_in"))
      (node (ref "R10") (pin "2") (pinfunction "2_2") (pintype "passive"))
      (node (ref "R18") (pin "2") (pinfunction "2_2") (pintype "passive"))
      (node (ref "R19") (pin "2") (pinfunction "2_2") (pintype "passive"))
      (node (ref "R20") (pin "2") (pinfunction "2_2") (pintype "passive"))
      (node (ref "U$20") (pin "1") (pinfunction "PAD_1") (pintype "bidirectional"))
      (node (ref "U$3") (pin "2") (pinfunction "VCC_2") (pintype "bidirectional"))
      (node (ref "U$9") (pin "5") (pinfunction "VOUT_5") (pintype "bidirectional"))
      (node (ref "X1") (pin "8") (pinfunction "VCC_8") (pintype "power_in"))
    )
    (net (code "2") (name "ADC") (class "Default")
      (node (ref "R12") (pin "1") (pinfunction "1_1") (pintype "passive"))
      (node (ref "R13") (pin "2") (pinfunction "2_2") (pintype "passive"))
      (node (ref "X1") (pin "2") (pinfunction "ADC_2") (pintype "passive"))
    )
    (net (code "3") (name "ADDR1") (class "Default")
      (node (ref "R2") (pin "2") (pinfunction "2_2") (pintype "passive"))
      (node (ref "U4") (pin "18") (pinfunction "ADDR_18") (pintype "bidirectional"))
    )
    (net (code "4") (name "CA1-1") (class "Default")
      (node (ref "C1-1") (pin "C") (pinfunction "C_C") (pintype "passive"))
      (node (ref "C1-2") (pin "C") (pinfunction "C_C") (pintype "passive"))
      (node (ref "C1-3") (pin "C") (pinfunction "C_C") (pintype "passive"))
      (node (ref "C1-4") (pin "C") (pinfunction "C_C") (pintype "passive"))
      (node (ref "C1-5") (pin "C") (pinfunction "C_C") (pintype "passive"))
      (node (ref "C1-6") (pin "C") (pinfunction "C_C") (pintype "passive"))
      (node (ref "C1-7") (pin "C") (pinfunction "C_C") (pintype "passive"))
      (node (ref "C1-8") (pin "C") (pinfunction "C_C") (pintype "passive"))
      (node (ref "C2-1") (pin "A") (pinfunction "A_A") (pintype "passive"))
      (node (ref "C3-1") (pin "A") (pinfunction "A_A") (pintype "passive"))
      (node (ref "C4-1") (pin "A") (pinfunction "A_A") (pintype "passive"))
      (node (ref "C5-1") (pin "A") (pinfunction "A_A") (pintype "passive"))
      (node (ref "C6-1") (pin "A") (pinfunction "A_A") (pintype "passive"))
      (node (ref "C7-1") (pin "A") (pinfunction "A_A") (pintype "passive"))
      (node (ref "C8-1") (pin "A") (pinfunction "A_A") (pintype "passive"))
      (node (ref "C9-1") (pin "A") (pinfunction "A_A") (pintype "passive"))
      (node (ref "U4") (pin "21") (pinfunction "CA1_21") (pintype "bidirectional"))
    )
    (net (code "5") (name "CA1-2") (class "Default")
      (node (ref "C1-17") (pin "C") (pinfunction "C_C") (pintype "passive"))
      (node (ref "C1-18") (pin "C") (pinfunction "C_C") (pintype "passive"))
      (node (ref "C1-19") (pin "C") (pinfunction "C_C") (pintype "passive"))
      (node (ref "C1-20") (pin "C") (pinfunction "C_C") (pintype "passive"))
      (node (ref "C1-21") (pin "C") (pinfunction "C_C") (pintype "passive"))
      (node (ref "C1-22") (pin "C") (pinfunction "C_C") (pintype "passive"))
      (node (ref "C1-23") (pin "C") (pinfunction "C_C") (pintype "passive"))
      (node (ref "C1-24") (pin "C") (pinfunction "C_C") (pintype "passive"))
      (node (ref "C2-17") (pin "A") (pinfunction "A_A") (pintype "passive"))
      (node (ref "C3-17") (pin "A") (pinfunction "A_A") (pintype "passive"))
      (node (ref "C4-17") (pin "A") (pinfunction "A_A") (pintype "passive"))
      (node (ref "C5-17") (pin "A") (pinfunction "A_A") (pintype "passive"))
      (node (ref "C6-17") (pin "A") (pinfunction "A_A") (pintype "passive"))
      (node (ref "C7-17") (pin "A") (pinfunction "A_A") (pintype "passive"))
      (node (ref "C8-17") (pin "A") (pinfunction "A_A") (pintype "passive"))
      (node (ref "C9-17") (pin "A") (pinfunction "A_A") (pintype "passive"))
      (node (ref "U2") (pin "21") (pinfunction "CA1_21") (pintype "bidirectional"))
    )
    (net (code "6") (name "CA1-3") (class "Default")
      (node (ref "C1-33") (pin "C") (pinfunction "C_C") (pintype "passive"))
      (node (ref "C1-34") (pin "C") (pinfunction "C_C") (pintype "passive"))
      (node (ref "C1-35") (pin "C") (pinfunction "C_C") (pintype "passive"))
      (node (ref "C1-36") (pin "C") (pinfunction "C_C") (pintype "passive"))
      (node (ref "C1-37") (pin "C") (pinfunction "C_C") (pintype "passive"))
      (node (ref "C1-38") (pin "C") (pinfunction "C_C") (pintype "passive"))
      (node (ref "C1-39") (pin "C") (pinfunction "C_C") (pintype "passive"))
      (node (ref "C1-40") (pin "C") (pinfunction "C_C") (pintype "passive"))
      (node (ref "C2-33") (pin "A") (pinfunction "A_A") (pintype "passive"))
      (node (ref "C3-33") (pin "A") (pinfunction "A_A") (pintype "passive"))
      (node (ref "C4-33") (pin "A") (pinfunction "A_A") (pintype "passive"))
      (node (ref "C5-33") (pin "A") (pinfunction "A_A") (pintype "passive"))
      (node (ref "C6-33") (pin "A") (pinfunction "A_A") (pintype "passive"))
      (node (ref "C7-33") (pin "A") (pinfunction "A_A") (pintype "passive"))
      (node (ref "C8-33") (pin "A") (pinfunction "A_A") (pintype "passive"))
      (node (ref "C9-33") (pin "A") (pinfunction "A_A") (pintype "passive"))
      (node (ref "U3") (pin "21") (pinfunction "CA1_21") (pintype "bidirectional"))
    )
    (net (code "7") (name "CA1-4") (class "Default")
      (node (ref "C1-49") (pin "C") (pinfunction "C_C") (pintype "passive"))
      (node (ref "C1-50") (pin "C") (pinfunction "C_C") (pintype "passive"))
      (node (ref "C1-51") (pin "C") (pinfunction "C_C") (pintype "passive"))
      (node (ref "C1-52") (pin "C") (pinfunction "C_C") (pintype "passive"))
      (node (ref "C1-53") (pin "C") (pinfunction "C_C") (pintype "passive"))
      (node (ref "C1-54") (pin "C") (pinfunction "C_C") (pintype "passive"))
      (node (ref "C1-55") (pin "C") (pinfunction "C_C") (pintype "passive"))
      (node (ref "C1-56") (pin "C") (pinfunction "C_C") (pintype "passive"))
      (node (ref "C2-49") (pin "A") (pinfunction "A_A") (pintype "passive"))
      (node (ref "C3-49") (pin "A") (pinfunction "A_A") (pintype "passive"))
      (node (ref "C4-49") (pin "A") (pinfunction "A_A") (pintype "passive"))
      (node (ref "C5-49") (pin "A") (pinfunction "A_A") (pintype "passive"))
      (node (ref "C6-49") (pin "A") (pinfunction "A_A") (pintype "passive"))
      (node (ref "C7-49") (pin "A") (pinfunction "A_A") (pintype "passive"))
      (node (ref "C8-49") (pin "A") (pinfunction "A_A") (pintype "passive"))
      (node (ref "C9-49") (pin "A") (pinfunction "A_A") (pintype "passive"))
      (node (ref "U5") (pin "21") (pinfunction "CA1_21") (pintype "bidirectional"))
    )
    (net (code "8") (name "CA2-1") (class "Default")
      (node (ref "C1-1") (pin "A") (pinfunction "A_A") (pintype "passive"))
      (node (ref "C2-1") (pin "C") (pinfunction "C_C") (pintype "passive"))
      (node (ref "C2-2") (pin "C") (pinfunction "C_C") (pintype "passive"))
      (node (ref "C2-3") (pin "C") (pinfunction "C_C") (pintype "passive"))
      (node (ref "C2-4") (pin "C") (pinfunction "C_C") (pintype "passive"))
      (node (ref "C2-5") (pin "C") (pinfunction "C_C") (pintype "passive"))
      (node (ref "C2-6") (pin "C") (pinfunction "C_C") (pintype "passive"))
      (node (ref "C2-7") (pin "C") (pinfunction "C_C") (pintype "passive"))
      (node (ref "C2-8") (pin "C") (pinfunction "C_C") (pintype "passive"))
      (node (ref "C3-2") (pin "A") (pinfunction "A_A") (pintype "passive"))
      (node (ref "C4-2") (pin "A") (pinfunction "A_A") (pintype "passive"))
      (node (ref "C5-2") (pin "A") (pinfunction "A_A") (pintype "passive"))
      (node (ref "C6-2") (pin "A") (pinfunction "A_A") (pintype "passive"))
      (node (ref "C7-2") (pin "A") (pinfunction "A_A") (pintype "passive"))
      (node (ref "C8-2") (pin "A") (pinfunction "A_A") (pintype "passive"))
      (node (ref "C9-2") (pin "A") (pinfunction "A_A") (pintype "passive"))
      (node (ref "U4") (pin "22") (pinfunction "CA2_22") (pintype "bidirectional"))
    )
    (net (code "9") (name "CA2-2") (class "Default")
      (node (ref "C1-17") (pin "A") (pinfunction "A_A") (pintype "passive"))
      (node (ref "C2-17") (pin "C") (pinfunction "C_C") (pintype "passive"))
      (node (ref "C2-18") (pin "C") (pinfunction "C_C") (pintype "passive"))
      (node (ref "C2-19") (pin "C") (pinfunction "C_C") (pintype "passive"))
      (node (ref "C2-20") (pin "C") (pinfunction "C_C") (pintype "passive"))
      (node (ref "C2-21") (pin "C") (pinfunction "C_C") (pintype "passive"))
      (node (ref "C2-22") (pin "C") (pinfunction "C_C") (pintype "passive"))
      (node (ref "C2-23") (pin "C") (pinfunction "C_C") (pintype "passive"))
      (node (ref "C2-24") (pin "C") (pinfunction "C_C") (pintype "passive"))
      (node (ref "C3-18") (pin "A") (pinfunction "A_A") (pintype "passive"))
      (node (ref "C4-18") (pin "A") (pinfunction "A_A") (pintype "passive"))
      (node (ref "C5-18") (pin "A") (pinfunction "A_A") (pintype "passive"))
      (node (ref "C6-18") (pin "A") (pinfunction "A_A") (pintype "passive"))
      (node (ref "C7-18") (pin "A") (pinfunction "A_A") (pintype "passive"))
      (node (ref "C8-18") (pin "A") (pinfunction "A_A") (pintype "passive"))
      (node (ref "C9-18") (pin "A") (pinfunction "A_A") (pintype "passive"))
      (node (ref "U2") (pin "22") (pinfunction "CA2_22") (pintype "bidirectional"))
    )
    (net (code "10") (name "CA2-3") (class "Default")
      (node (ref "C1-33") (pin "A") (pinfunction "A_A") (pintype "passive"))
      (node (ref "C2-33") (pin "C") (pinfunction "C_C") (pintype "passive"))
      (node (ref "C2-34") (pin "C") (pinfunction "C_C") (pintype "passive"))
      (node (ref "C2-35") (pin "C") (pinfunction "C_C") (pintype "passive"))
      (node (ref "C2-36") (pin "C") (pinfunction "C_C") (pintype "passive"))
      (node (ref "C2-37") (pin "C") (pinfunction "C_C") (pintype "passive"))
      (node (ref "C2-38") (pin "C") (pinfunction "C_C") (pintype "passive"))
      (node (ref "C2-39") (pin "C") (pinfunction "C_C") (pintype "passive"))
      (node (ref "C2-40") (pin "C") (pinfunction "C_C") (pintype "passive"))
      (node (ref "C3-34") (pin "A") (pinfunction "A_A") (pintype "passive"))
      (node (ref "C4-34") (pin "A") (pinfunction "A_A") (pintype "passive"))
      (node (ref "C5-34") (pin "A") (pinfunction "A_A") (pintype "passive"))
      (node (ref "C6-34") (pin "A") (pinfunction "A_A") (pintype "passive"))
      (node (ref "C7-34") (pin "A") (pinfunction "A_A") (pintype "passive"))
      (node (ref "C8-34") (pin "A") (pinfunction "A_A") (pintype "passive"))
      (node (ref "C9-34") (pin "A") (pinfunction "A_A") (pintype "passive"))
      (node (ref "U3") (pin "22") (pinfunction "CA2_22") (pintype "bidirectional"))
    )
    (net (code "11") (name "CA2-4") (class "Default")
      (node (ref "C1-49") (pin "A") (pinfunction "A_A") (pintype "passive"))
      (node (ref "C2-49") (pin "C") (pinfunction "C_C") (pintype "passive"))
      (node (ref "C2-50") (pin "C") (pinfunction "C_C") (pintype "passive"))
      (node (ref "C2-51") (pin "C") (pinfunction "C_C") (pintype "passive"))
      (node (ref "C2-52") (pin "C") (pinfunction "C_C") (pintype "passive"))
      (node (ref "C2-53") (pin "C") (pinfunction "C_C") (pintype "passive"))
      (node (ref "C2-54") (pin "C") (pinfunction "C_C") (pintype "passive"))
      (node (ref "C2-55") (pin "C") (pinfunction "C_C") (pintype "passive"))
      (node (ref "C2-56") (pin "C") (pinfunction "C_C") (pintype "passive"))
      (node (ref "C3-50") (pin "A") (pinfunction "A_A") (pintype "passive"))
      (node (ref "C4-50") (pin "A") (pinfunction "A_A") (pintype "passive"))
      (node (ref "C5-50") (pin "A") (pinfunction "A_A") (pintype "passive"))
      (node (ref "C6-50") (pin "A") (pinfunction "A_A") (pintype "passive"))
      (node (ref "C7-50") (pin "A") (pinfunction "A_A") (pintype "passive"))
      (node (ref "C8-50") (pin "A") (pinfunction "A_A") (pintype "passive"))
      (node (ref "C9-50") (pin "A") (pinfunction "A_A") (pintype "passive"))
      (node (ref "U5") (pin "22") (pinfunction "CA2_22") (pintype "bidirectional"))
    )
    (net (code "12") (name "CA3-1") (class "Default")
      (node (ref "C1-2") (pin "A") (pinfunction "A_A") (pintype "passive"))
      (node (ref "C2-2") (pin "A") (pinfunction "A_A") (pintype "passive"))
      (node (ref "C3-1") (pin "C") (pinfunction "C_C") (pintype "passive"))
      (node (ref "C3-2") (pin "C") (pinfunction "C_C") (pintype "passive"))
      (node (ref "C3-3") (pin "C") (pinfunction "C_C") (pintype "passive"))
      (node (ref "C3-4") (pin "C") (pinfunction "C_C") (pintype "passive"))
      (node (ref "C3-5") (pin "C") (pinfunction "C_C") (pintype "passive"))
      (node (ref "C3-6") (pin "C") (pinfunction "C_C") (pintype "passive"))
      (node (ref "C3-7") (pin "C") (pinfunction "C_C") (pintype "passive"))
      (node (ref "C3-8") (pin "C") (pinfunction "C_C") (pintype "passive"))
      (node (ref "C4-3") (pin "A") (pinfunction "A_A") (pintype "passive"))
      (node (ref "C5-3") (pin "A") (pinfunction "A_A") (pintype "passive"))
      (node (ref "C6-3") (pin "A") (pinfunction "A_A") (pintype "passive"))
      (node (ref "C7-3") (pin "A") (pinfunction "A_A") (pintype "passive"))
      (node (ref "C8-3") (pin "A") (pinfunction "A_A") (pintype "passive"))
      (node (ref "C9-3") (pin "A") (pinfunction "A_A") (pintype "passive"))
      (node (ref "U4") (pin "23") (pinfunction "CA3_23") (pintype "bidirectional"))
    )
    (net (code "13") (name "CA3-2") (class "Default")
      (node (ref "C1-18") (pin "A") (pinfunction "A_A") (pintype "passive"))
      (node (ref "C2-18") (pin "A") (pinfunction "A_A") (pintype "passive"))
      (node (ref "C3-17") (pin "C") (pinfunction "C_C") (pintype "passive"))
      (node (ref "C3-18") (pin "C") (pinfunction "C_C") (pintype "passive"))
      (node (ref "C3-19") (pin "C") (pinfunction "C_C") (pintype "passive"))
      (node (ref "C3-20") (pin "C") (pinfunction "C_C") (pintype "passive"))
      (node (ref "C3-21") (pin "C") (pinfunction "C_C") (pintype "passive"))
      (node (ref "C3-22") (pin "C") (pinfunction "C_C") (pintype "passive"))
      (node (ref "C3-23") (pin "C") (pinfunction "C_C") (pintype "passive"))
      (node (ref "C3-24") (pin "C") (pinfunction "C_C") (pintype "passive"))
      (node (ref "C4-19") (pin "A") (pinfunction "A_A") (pintype "passive"))
      (node (ref "C5-19") (pin "A") (pinfunction "A_A") (pintype "passive"))
      (node (ref "C6-19") (pin "A") (pinfunction "A_A") (pintype "passive"))
      (node (ref "C7-19") (pin "A") (pinfunction "A_A") (pintype "passive"))
      (node (ref "C8-19") (pin "A") (pinfunction "A_A") (pintype "passive"))
      (node (ref "C9-19") (pin "A") (pinfunction "A_A") (pintype "passive"))
      (node (ref "U2") (pin "23") (pinfunction "CA3_23") (pintype "bidirectional"))
    )
    (net (code "14") (name "CA3-3") (class "Default")
      (node (ref "C1-34") (pin "A") (pinfunction "A_A") (pintype "passive"))
      (node (ref "C2-34") (pin "A") (pinfunction "A_A") (pintype "passive"))
      (node (ref "C3-33") (pin "C") (pinfunction "C_C") (pintype "passive"))
      (node (ref "C3-34") (pin "C") (pinfunction "C_C") (pintype "passive"))
      (node (ref "C3-35") (pin "C") (pinfunction "C_C") (pintype "passive"))
      (node (ref "C3-36") (pin "C") (pinfunction "C_C") (pintype "passive"))
      (node (ref "C3-37") (pin "C") (pinfunction "C_C") (pintype "passive"))
      (node (ref "C3-38") (pin "C") (pinfunction "C_C") (pintype "passive"))
      (node (ref "C3-39") (pin "C") (pinfunction "C_C") (pintype "passive"))
      (node (ref "C3-40") (pin "C") (pinfunction "C_C") (pintype "passive"))
      (node (ref "C4-35") (pin "A") (pinfunction "A_A") (pintype "passive"))
      (node (ref "C5-35") (pin "A") (pinfunction "A_A") (pintype "passive"))
      (node (ref "C6-35") (pin "A") (pinfunction "A_A") (pintype "passive"))
      (node (ref "C7-35") (pin "A") (pinfunction "A_A") (pintype "passive"))
      (node (ref "C8-35") (pin "A") (pinfunction "A_A") (pintype "passive"))
      (node (ref "C9-35") (pin "A") (pinfunction "A_A") (pintype "passive"))
      (node (ref "U3") (pin "23") (pinfunction "CA3_23") (pintype "bidirectional"))
    )
    (net (code "15") (name "CA3-4") (class "Default")
      (node (ref "C1-50") (pin "A") (pinfunction "A_A") (pintype "passive"))
      (node (ref "C2-50") (pin "A") (pinfunction "A_A") (pintype "passive"))
      (node (ref "C3-49") (pin "C") (pinfunction "C_C") (pintype "passive"))
      (node (ref "C3-50") (pin "C") (pinfunction "C_C") (pintype "passive"))
      (node (ref "C3-51") (pin "C") (pinfunction "C_C") (pintype "passive"))
      (node (ref "C3-52") (pin "C") (pinfunction "C_C") (pintype "passive"))
      (node (ref "C3-53") (pin "C") (pinfunction "C_C") (pintype "passive"))
      (node (ref "C3-54") (pin "C") (pinfunction "C_C") (pintype "passive"))
      (node (ref "C3-55") (pin "C") (pinfunction "C_C") (pintype "passive"))
      (node (ref "C3-56") (pin "C") (pinfunction "C_C") (pintype "passive"))
      (node (ref "C4-51") (pin "A") (pinfunction "A_A") (pintype "passive"))
      (node (ref "C5-51") (pin "A") (pinfunction "A_A") (pintype "passive"))
      (node (ref "C6-51") (pin "A") (pinfunction "A_A") (pintype "passive"))
      (node (ref "C7-51") (pin "A") (pinfunction "A_A") (pintype "passive"))
      (node (ref "C8-51") (pin "A") (pinfunction "A_A") (pintype "passive"))
      (node (ref "C9-51") (pin "A") (pinfunction "A_A") (pintype "passive"))
      (node (ref "U5") (pin "23") (pinfunction "CA3_23") (pintype "bidirectional"))
    )
    (net (code "16") (name "CA4-1") (class "Default")
      (node (ref "C1-3") (pin "A") (pinfunction "A_A") (pintype "passive"))
      (node (ref "C2-3") (pin "A") (pinfunction "A_A") (pintype "passive"))
      (node (ref "C3-3") (pin "A") (pinfunction "A_A") (pintype "passive"))
      (node (ref "C4-1") (pin "C") (pinfunction "C_C") (pintype "passive"))
      (node (ref "C4-2") (pin "C") (pinfunction "C_C") (pintype "passive"))
      (node (ref "C4-3") (pin "C") (pinfunction "C_C") (pintype "passive"))
      (node (ref "C4-4") (pin "C") (pinfunction "C_C") (pintype "passive"))
      (node (ref "C4-5") (pin "C") (pinfunction "C_C") (pintype "passive"))
      (node (ref "C4-6") (pin "C") (pinfunction "C_C") (pintype "passive"))
      (node (ref "C4-7") (pin "C") (pinfunction "C_C") (pintype "passive"))
      (node (ref "C4-8") (pin "C") (pinfunction "C_C") (pintype "passive"))
      (node (ref "C5-4") (pin "A") (pinfunction "A_A") (pintype "passive"))
      (node (ref "C6-4") (pin "A") (pinfunction "A_A") (pintype "passive"))
      (node (ref "C7-4") (pin "A") (pinfunction "A_A") (pintype "passive"))
      (node (ref "C8-4") (pin "A") (pinfunction "A_A") (pintype "passive"))
      (node (ref "C9-4") (pin "A") (pinfunction "A_A") (pintype "passive"))
      (node (ref "U4") (pin "24") (pinfunction "CA4_24") (pintype "bidirectional"))
    )
    (net (code "17") (name "CA4-2") (class "Default")
      (node (ref "C1-19") (pin "A") (pinfunction "A_A") (pintype "passive"))
      (node (ref "C2-19") (pin "A") (pinfunction "A_A") (pintype "passive"))
      (node (ref "C3-19") (pin "A") (pinfunction "A_A") (pintype "passive"))
      (node (ref "C4-17") (pin "C") (pinfunction "C_C") (pintype "passive"))
      (node (ref "C4-18") (pin "C") (pinfunction "C_C") (pintype "passive"))
      (node (ref "C4-19") (pin "C") (pinfunction "C_C") (pintype "passive"))
      (node (ref "C4-20") (pin "C") (pinfunction "C_C") (pintype "passive"))
      (node (ref "C4-21") (pin "C") (pinfunction "C_C") (pintype "passive"))
      (node (ref "C4-22") (pin "C") (pinfunction "C_C") (pintype "passive"))
      (node (ref "C4-23") (pin "C") (pinfunction "C_C") (pintype "passive"))
      (node (ref "C4-24") (pin "C") (pinfunction "C_C") (pintype "passive"))
      (node (ref "C5-20") (pin "A") (pinfunction "A_A") (pintype "passive"))
      (node (ref "C6-20") (pin "A") (pinfunction "A_A") (pintype "passive"))
      (node (ref "C7-20") (pin "A") (pinfunction "A_A") (pintype "passive"))
      (node (ref "C8-20") (pin "A") (pinfunction "A_A") (pintype "passive"))
      (node (ref "C9-20") (pin "A") (pinfunction "A_A") (pintype "passive"))
      (node (ref "U2") (pin "24") (pinfunction "CA4_24") (pintype "bidirectional"))
    )
    (net (code "18") (name "CA4-3") (class "Default")
      (node (ref "C1-35") (pin "A") (pinfunction "A_A") (pintype "passive"))
      (node (ref "C2-35") (pin "A") (pinfunction "A_A") (pintype "passive"))
      (node (ref "C3-35") (pin "A") (pinfunction "A_A") (pintype "passive"))
      (node (ref "C4-33") (pin "C") (pinfunction "C_C") (pintype "passive"))
      (node (ref "C4-34") (pin "C") (pinfunction "C_C") (pintype "passive"))
      (node (ref "C4-35") (pin "C") (pinfunction "C_C") (pintype "passive"))
      (node (ref "C4-36") (pin "C") (pinfunction "C_C") (pintype "passive"))
      (node (ref "C4-37") (pin "C") (pinfunction "C_C") (pintype "passive"))
      (node (ref "C4-38") (pin "C") (pinfunction "C_C") (pintype "passive"))
      (node (ref "C4-39") (pin "C") (pinfunction "C_C") (pintype "passive"))
      (node (ref "C4-40") (pin "C") (pinfunction "C_C") (pintype "passive"))
      (node (ref "C5-36") (pin "A") (pinfunction "A_A") (pintype "passive"))
      (node (ref "C6-36") (pin "A") (pinfunction "A_A") (pintype "passive"))
      (node (ref "C7-36") (pin "A") (pinfunction "A_A") (pintype "passive"))
      (node (ref "C8-36") (pin "A") (pinfunction "A_A") (pintype "passive"))
      (node (ref "C9-36") (pin "A") (pinfunction "A_A") (pintype "passive"))
      (node (ref "U3") (pin "24") (pinfunction "CA4_24") (pintype "bidirectional"))
    )
    (net (code "19") (name "CA4-4") (class "Default")
      (node (ref "C1-51") (pin "A") (pinfunction "A_A") (pintype "passive"))
      (node (ref "C2-51") (pin "A") (pinfunction "A_A") (pintype "passive"))
      (node (ref "C3-51") (pin "A") (pinfunction "A_A") (pintype "passive"))
      (node (ref "C4-49") (pin "C") (pinfunction "C_C") (pintype "passive"))
      (node (ref "C4-50") (pin "C") (pinfunction "C_C") (pintype "passive"))
      (node (ref "C4-51") (pin "C") (pinfunction "C_C") (pintype "passive"))
      (node (ref "C4-52") (pin "C") (pinfunction "C_C") (pintype "passive"))
      (node (ref "C4-53") (pin "C") (pinfunction "C_C") (pintype "passive"))
      (node (ref "C4-54") (pin "C") (pinfunction "C_C") (pintype "passive"))
      (node (ref "C4-55") (pin "C") (pinfunction "C_C") (pintype "passive"))
      (node (ref "C4-56") (pin "C") (pinfunction "C_C") (pintype "passive"))
      (node (ref "C5-52") (pin "A") (pinfunction "A_A") (pintype "passive"))
      (node (ref "C6-52") (pin "A") (pinfunction "A_A") (pintype "passive"))
      (node (ref "C7-52") (pin "A") (pinfunction "A_A") (pintype "passive"))
      (node (ref "C8-52") (pin "A") (pinfunction "A_A") (pintype "passive"))
      (node (ref "C9-52") (pin "A") (pinfunction "A_A") (pintype "passive"))
      (node (ref "U5") (pin "24") (pinfunction "CA4_24") (pintype "bidirectional"))
    )
    (net (code "20") (name "CA5-1") (class "Default")
      (node (ref "C1-4") (pin "A") (pinfunction "A_A") (pintype "passive"))
      (node (ref "C2-4") (pin "A") (pinfunction "A_A") (pintype "passive"))
      (node (ref "C3-4") (pin "A") (pinfunction "A_A") (pintype "passive"))
      (node (ref "C4-4") (pin "A") (pinfunction "A_A") (pintype "passive"))
      (node (ref "C5-1") (pin "C") (pinfunction "C_C") (pintype "passive"))
      (node (ref "C5-2") (pin "C") (pinfunction "C_C") (pintype "passive"))
      (node (ref "C5-3") (pin "C") (pinfunction "C_C") (pintype "passive"))
      (node (ref "C5-4") (pin "C") (pinfunction "C_C") (pintype "passive"))
      (node (ref "C5-5") (pin "C") (pinfunction "C_C") (pintype "passive"))
      (node (ref "C5-6") (pin "C") (pinfunction "C_C") (pintype "passive"))
      (node (ref "C5-7") (pin "C") (pinfunction "C_C") (pintype "passive"))
      (node (ref "C5-8") (pin "C") (pinfunction "C_C") (pintype "passive"))
      (node (ref "C6-5") (pin "A") (pinfunction "A_A") (pintype "passive"))
      (node (ref "C7-5") (pin "A") (pinfunction "A_A") (pintype "passive"))
      (node (ref "C8-5") (pin "A") (pinfunction "A_A") (pintype "passive"))
      (node (ref "C9-5") (pin "A") (pinfunction "A_A") (pintype "passive"))
      (node (ref "U4") (pin "25") (pinfunction "CA5_25") (pintype "bidirectional"))
    )
    (net (code "21") (name "CA5-2") (class "Default")
      (node (ref "C1-20") (pin "A") (pinfunction "A_A") (pintype "passive"))
      (node (ref "C2-20") (pin "A") (pinfunction "A_A") (pintype "passive"))
      (node (ref "C3-20") (pin "A") (pinfunction "A_A") (pintype "passive"))
      (node (ref "C4-20") (pin "A") (pinfunction "A_A") (pintype "passive"))
      (node (ref "C5-17") (pin "C") (pinfunction "C_C") (pintype "passive"))
      (node (ref "C5-18") (pin "C") (pinfunction "C_C") (pintype "passive"))
      (node (ref "C5-19") (pin "C") (pinfunction "C_C") (pintype "passive"))
      (node (ref "C5-20") (pin "C") (pinfunction "C_C") (pintype "passive"))
      (node (ref "C5-21") (pin "C") (pinfunction "C_C") (pintype "passive"))
      (node (ref "C5-22") (pin "C") (pinfunction "C_C") (pintype "passive"))
      (node (ref "C5-23") (pin "C") (pinfunction "C_C") (pintype "passive"))
      (node (ref "C5-24") (pin "C") (pinfunction "C_C") (pintype "passive"))
      (node (ref "C6-21") (pin "A") (pinfunction "A_A") (pintype "passive"))
      (node (ref "C7-21") (pin "A") (pinfunction "A_A") (pintype "passive"))
      (node (ref "C8-21") (pin "A") (pinfunction "A_A") (pintype "passive"))
      (node (ref "C9-21") (pin "A") (pinfunction "A_A") (pintype "passive"))
      (node (ref "U2") (pin "25") (pinfunction "CA5_25") (pintype "bidirectional"))
    )
    (net (code "22") (name "CA5-3") (class "Default")
      (node (ref "C1-36") (pin "A") (pinfunction "A_A") (pintype "passive"))
      (node (ref "C2-36") (pin "A") (pinfunction "A_A") (pintype "passive"))
      (node (ref "C3-36") (pin "A") (pinfunction "A_A") (pintype "passive"))
      (node (ref "C4-36") (pin "A") (pinfunction "A_A") (pintype "passive"))
      (node (ref "C5-33") (pin "C") (pinfunction "C_C") (pintype "passive"))
      (node (ref "C5-34") (pin "C") (pinfunction "C_C") (pintype "passive"))
      (node (ref "C5-35") (pin "C") (pinfunction "C_C") (pintype "passive"))
      (node (ref "C5-36") (pin "C") (pinfunction "C_C") (pintype "passive"))
      (node (ref "C5-37") (pin "C") (pinfunction "C_C") (pintype "passive"))
      (node (ref "C5-38") (pin "C") (pinfunction "C_C") (pintype "passive"))
      (node (ref "C5-39") (pin "C") (pinfunction "C_C") (pintype "passive"))
      (node (ref "C5-40") (pin "C") (pinfunction "C_C") (pintype "passive"))
      (node (ref "C6-37") (pin "A") (pinfunction "A_A") (pintype "passive"))
      (node (ref "C7-37") (pin "A") (pinfunction "A_A") (pintype "passive"))
      (node (ref "C8-37") (pin "A") (pinfunction "A_A") (pintype "passive"))
      (node (ref "C9-37") (pin "A") (pinfunction "A_A") (pintype "passive"))
      (node (ref "U3") (pin "25") (pinfunction "CA5_25") (pintype "bidirectional"))
    )
    (net (code "23") (name "CA5-4") (class "Default")
      (node (ref "C1-52") (pin "A") (pinfunction "A_A") (pintype "passive"))
      (node (ref "C2-52") (pin "A") (pinfunction "A_A") (pintype "passive"))
      (node (ref "C3-52") (pin "A") (pinfunction "A_A") (pintype "passive"))
      (node (ref "C4-52") (pin "A") (pinfunction "A_A") (pintype "passive"))
      (node (ref "C5-49") (pin "C") (pinfunction "C_C") (pintype "passive"))
      (node (ref "C5-50") (pin "C") (pinfunction "C_C") (pintype "passive"))
      (node (ref "C5-51") (pin "C") (pinfunction "C_C") (pintype "passive"))
      (node (ref "C5-52") (pin "C") (pinfunction "C_C") (pintype "passive"))
      (node (ref "C5-53") (pin "C") (pinfunction "C_C") (pintype "passive"))
      (node (ref "C5-54") (pin "C") (pinfunction "C_C") (pintype "passive"))
      (node (ref "C5-55") (pin "C") (pinfunction "C_C") (pintype "passive"))
      (node (ref "C5-56") (pin "C") (pinfunction "C_C") (pintype "passive"))
      (node (ref "C6-53") (pin "A") (pinfunction "A_A") (pintype "passive"))
      (node (ref "C7-53") (pin "A") (pinfunction "A_A") (pintype "passive"))
      (node (ref "C8-53") (pin "A") (pinfunction "A_A") (pintype "passive"))
      (node (ref "C9-53") (pin "A") (pinfunction "A_A") (pintype "passive"))
      (node (ref "U5") (pin "25") (pinfunction "CA5_25") (pintype "bidirectional"))
    )
    (net (code "24") (name "CA6-1") (class "Default")
      (node (ref "C1-5") (pin "A") (pinfunction "A_A") (pintype "passive"))
      (node (ref "C2-5") (pin "A") (pinfunction "A_A") (pintype "passive"))
      (node (ref "C3-5") (pin "A") (pinfunction "A_A") (pintype "passive"))
      (node (ref "C4-5") (pin "A") (pinfunction "A_A") (pintype "passive"))
      (node (ref "C5-5") (pin "A") (pinfunction "A_A") (pintype "passive"))
      (node (ref "C6-1") (pin "C") (pinfunction "C_C") (pintype "passive"))
      (node (ref "C6-2") (pin "C") (pinfunction "C_C") (pintype "passive"))
      (node (ref "C6-3") (pin "C") (pinfunction "C_C") (pintype "passive"))
      (node (ref "C6-4") (pin "C") (pinfunction "C_C") (pintype "passive"))
      (node (ref "C6-5") (pin "C") (pinfunction "C_C") (pintype "passive"))
      (node (ref "C6-6") (pin "C") (pinfunction "C_C") (pintype "passive"))
      (node (ref "C6-7") (pin "C") (pinfunction "C_C") (pintype "passive"))
      (node (ref "C6-8") (pin "C") (pinfunction "C_C") (pintype "passive"))
      (node (ref "C7-6") (pin "A") (pinfunction "A_A") (pintype "passive"))
      (node (ref "C8-6") (pin "A") (pinfunction "A_A") (pintype "passive"))
      (node (ref "C9-6") (pin "A") (pinfunction "A_A") (pintype "passive"))
      (node (ref "U4") (pin "26") (pinfunction "CA6_26") (pintype "bidirectional"))
    )
    (net (code "25") (name "CA6-2") (class "Default")
      (node (ref "C1-21") (pin "A") (pinfunction "A_A") (pintype "passive"))
      (node (ref "C2-21") (pin "A") (pinfunction "A_A") (pintype "passive"))
      (node (ref "C3-21") (pin "A") (pinfunction "A_A") (pintype "passive"))
      (node (ref "C4-21") (pin "A") (pinfunction "A_A") (pintype "passive"))
      (node (ref "C5-21") (pin "A") (pinfunction "A_A") (pintype "passive"))
      (node (ref "C6-17") (pin "C") (pinfunction "C_C") (pintype "passive"))
      (node (ref "C6-18") (pin "C") (pinfunction "C_C") (pintype "passive"))
      (node (ref "C6-19") (pin "C") (pinfunction "C_C") (pintype "passive"))
      (node (ref "C6-20") (pin "C") (pinfunction "C_C") (pintype "passive"))
      (node (ref "C6-21") (pin "C") (pinfunction "C_C") (pintype "passive"))
      (node (ref "C6-22") (pin "C") (pinfunction "C_C") (pintype "passive"))
      (node (ref "C6-23") (pin "C") (pinfunction "C_C") (pintype "passive"))
      (node (ref "C6-24") (pin "C") (pinfunction "C_C") (pintype "passive"))
      (node (ref "C7-22") (pin "A") (pinfunction "A_A") (pintype "passive"))
      (node (ref "C8-22") (pin "A") (pinfunction "A_A") (pintype "passive"))
      (node (ref "C9-22") (pin "A") (pinfunction "A_A") (pintype "passive"))
      (node (ref "U2") (pin "26") (pinfunction "CA6_26") (pintype "bidirectional"))
    )
    (net (code "26") (name "CA6-3") (class "Default")
      (node (ref "C1-37") (pin "A") (pinfunction "A_A") (pintype "passive"))
      (node (ref "C2-37") (pin "A") (pinfunction "A_A") (pintype "passive"))
      (node (ref "C3-37") (pin "A") (pinfunction "A_A") (pintype "passive"))
      (node (ref "C4-37") (pin "A") (pinfunction "A_A") (pintype "passive"))
      (node (ref "C5-37") (pin "A") (pinfunction "A_A") (pintype "passive"))
      (node (ref "C6-33") (pin "C") (pinfunction "C_C") (pintype "passive"))
      (node (ref "C6-34") (pin "C") (pinfunction "C_C") (pintype "passive"))
      (node (ref "C6-35") (pin "C") (pinfunction "C_C") (pintype "passive"))
      (node (ref "C6-36") (pin "C") (pinfunction "C_C") (pintype "passive"))
      (node (ref "C6-37") (pin "C") (pinfunction "C_C") (pintype "passive"))
      (node (ref "C6-38") (pin "C") (pinfunction "C_C") (pintype "passive"))
      (node (ref "C6-39") (pin "C") (pinfunction "C_C") (pintype "passive"))
      (node (ref "C6-40") (pin "C") (pinfunction "C_C") (pintype "passive"))
      (node (ref "C7-38") (pin "A") (pinfunction "A_A") (pintype "passive"))
      (node (ref "C8-38") (pin "A") (pinfunction "A_A") (pintype "passive"))
      (node (ref "C9-38") (pin "A") (pinfunction "A_A") (pintype "passive"))
      (node (ref "U3") (pin "26") (pinfunction "CA6_26") (pintype "bidirectional"))
    )
    (net (code "27") (name "CA6-4") (class "Default")
      (node (ref "C1-53") (pin "A") (pinfunction "A_A") (pintype "passive"))
      (node (ref "C2-53") (pin "A") (pinfunction "A_A") (pintype "passive"))
      (node (ref "C3-53") (pin "A") (pinfunction "A_A") (pintype "passive"))
      (node (ref "C4-53") (pin "A") (pinfunction "A_A") (pintype "passive"))
      (node (ref "C5-53") (pin "A") (pinfunction "A_A") (pintype "passive"))
      (node (ref "C6-49") (pin "C") (pinfunction "C_C") (pintype "passive"))
      (node (ref "C6-50") (pin "C") (pinfunction "C_C") (pintype "passive"))
      (node (ref "C6-51") (pin "C") (pinfunction "C_C") (pintype "passive"))
      (node (ref "C6-52") (pin "C") (pinfunction "C_C") (pintype "passive"))
      (node (ref "C6-53") (pin "C") (pinfunction "C_C") (pintype "passive"))
      (node (ref "C6-54") (pin "C") (pinfunction "C_C") (pintype "passive"))
      (node (ref "C6-55") (pin "C") (pinfunction "C_C") (pintype "passive"))
      (node (ref "C6-56") (pin "C") (pinfunction "C_C") (pintype "passive"))
      (node (ref "C7-54") (pin "A") (pinfunction "A_A") (pintype "passive"))
      (node (ref "C8-54") (pin "A") (pinfunction "A_A") (pintype "passive"))
      (node (ref "C9-54") (pin "A") (pinfunction "A_A") (pintype "passive"))
      (node (ref "U5") (pin "26") (pinfunction "CA6_26") (pintype "bidirectional"))
    )
    (net (code "28") (name "CA7-1") (class "Default")
      (node (ref "C1-6") (pin "A") (pinfunction "A_A") (pintype "passive"))
      (node (ref "C2-6") (pin "A") (pinfunction "A_A") (pintype "passive"))
      (node (ref "C3-6") (pin "A") (pinfunction "A_A") (pintype "passive"))
      (node (ref "C4-6") (pin "A") (pinfunction "A_A") (pintype "passive"))
      (node (ref "C5-6") (pin "A") (pinfunction "A_A") (pintype "passive"))
      (node (ref "C6-6") (pin "A") (pinfunction "A_A") (pintype "passive"))
      (node (ref "C7-1") (pin "C") (pinfunction "C_C") (pintype "passive"))
      (node (ref "C7-2") (pin "C") (pinfunction "C_C") (pintype "passive"))
      (node (ref "C7-3") (pin "C") (pinfunction "C_C") (pintype "passive"))
      (node (ref "C7-4") (pin "C") (pinfunction "C_C") (pintype "passive"))
      (node (ref "C7-5") (pin "C") (pinfunction "C_C") (pintype "passive"))
      (node (ref "C7-6") (pin "C") (pinfunction "C_C") (pintype "passive"))
      (node (ref "C7-7") (pin "C") (pinfunction "C_C") (pintype "passive"))
      (node (ref "C7-8") (pin "C") (pinfunction "C_C") (pintype "passive"))
      (node (ref "C8-7") (pin "A") (pinfunction "A_A") (pintype "passive"))
      (node (ref "C9-7") (pin "A") (pinfunction "A_A") (pintype "passive"))
      (node (ref "U4") (pin "27") (pinfunction "CA7_27") (pintype "bidirectional"))
    )
    (net (code "29") (name "CA7-2") (class "Default")
      (node (ref "C1-22") (pin "A") (pinfunction "A_A") (pintype "passive"))
      (node (ref "C2-22") (pin "A") (pinfunction "A_A") (pintype "passive"))
      (node (ref "C3-22") (pin "A") (pinfunction "A_A") (pintype "passive"))
      (node (ref "C4-22") (pin "A") (pinfunction "A_A") (pintype "passive"))
      (node (ref "C5-22") (pin "A") (pinfunction "A_A") (pintype "passive"))
      (node (ref "C6-22") (pin "A") (pinfunction "A_A") (pintype "passive"))
      (node (ref "C7-17") (pin "C") (pinfunction "C_C") (pintype "passive"))
      (node (ref "C7-18") (pin "C") (pinfunction "C_C") (pintype "passive"))
      (node (ref "C7-19") (pin "C") (pinfunction "C_C") (pintype "passive"))
      (node (ref "C7-20") (pin "C") (pinfunction "C_C") (pintype "passive"))
      (node (ref "C7-21") (pin "C") (pinfunction "C_C") (pintype "passive"))
      (node (ref "C7-22") (pin "C") (pinfunction "C_C") (pintype "passive"))
      (node (ref "C7-23") (pin "C") (pinfunction "C_C") (pintype "passive"))
      (node (ref "C7-24") (pin "C") (pinfunction "C_C") (pintype "passive"))
      (node (ref "C8-23") (pin "A") (pinfunction "A_A") (pintype "passive"))
      (node (ref "C9-23") (pin "A") (pinfunction "A_A") (pintype "passive"))
      (node (ref "U2") (pin "27") (pinfunction "CA7_27") (pintype "bidirectional"))
    )
    (net (code "30") (name "CA7-3") (class "Default")
      (node (ref "C1-38") (pin "A") (pinfunction "A_A") (pintype "passive"))
      (node (ref "C2-38") (pin "A") (pinfunction "A_A") (pintype "passive"))
      (node (ref "C3-38") (pin "A") (pinfunction "A_A") (pintype "passive"))
      (node (ref "C4-38") (pin "A") (pinfunction "A_A") (pintype "passive"))
      (node (ref "C5-38") (pin "A") (pinfunction "A_A") (pintype "passive"))
      (node (ref "C6-38") (pin "A") (pinfunction "A_A") (pintype "passive"))
      (node (ref "C7-33") (pin "C") (pinfunction "C_C") (pintype "passive"))
      (node (ref "C7-34") (pin "C") (pinfunction "C_C") (pintype "passive"))
      (node (ref "C7-35") (pin "C") (pinfunction "C_C") (pintype "passive"))
      (node (ref "C7-36") (pin "C") (pinfunction "C_C") (pintype "passive"))
      (node (ref "C7-37") (pin "C") (pinfunction "C_C") (pintype "passive"))
      (node (ref "C7-38") (pin "C") (pinfunction "C_C") (pintype "passive"))
      (node (ref "C7-39") (pin "C") (pinfunction "C_C") (pintype "passive"))
      (node (ref "C7-40") (pin "C") (pinfunction "C_C") (pintype "passive"))
      (node (ref "C8-39") (pin "A") (pinfunction "A_A") (pintype "passive"))
      (node (ref "C9-39") (pin "A") (pinfunction "A_A") (pintype "passive"))
      (node (ref "U3") (pin "27") (pinfunction "CA7_27") (pintype "bidirectional"))
    )
    (net (code "31") (name "CA7-4") (class "Default")
      (node (ref "C1-54") (pin "A") (pinfunction "A_A") (pintype "passive"))
      (node (ref "C2-54") (pin "A") (pinfunction "A_A") (pintype "passive"))
      (node (ref "C3-54") (pin "A") (pinfunction "A_A") (pintype "passive"))
      (node (ref "C4-54") (pin "A") (pinfunction "A_A") (pintype "passive"))
      (node (ref "C5-54") (pin "A") (pinfunction "A_A") (pintype "passive"))
      (node (ref "C6-54") (pin "A") (pinfunction "A_A") (pintype "passive"))
      (node (ref "C7-49") (pin "C") (pinfunction "C_C") (pintype "passive"))
      (node (ref "C7-50") (pin "C") (pinfunction "C_C") (pintype "passive"))
      (node (ref "C7-51") (pin "C") (pinfunction "C_C") (pintype "passive"))
      (node (ref "C7-52") (pin "C") (pinfunction "C_C") (pintype "passive"))
      (node (ref "C7-53") (pin "C") (pinfunction "C_C") (pintype "passive"))
      (node (ref "C7-54") (pin "C") (pinfunction "C_C") (pintype "passive"))
      (node (ref "C7-55") (pin "C") (pinfunction "C_C") (pintype "passive"))
      (node (ref "C7-56") (pin "C") (pinfunction "C_C") (pintype "passive"))
      (node (ref "C8-55") (pin "A") (pinfunction "A_A") (pintype "passive"))
      (node (ref "C9-55") (pin "A") (pinfunction "A_A") (pintype "passive"))
      (node (ref "U5") (pin "27") (pinfunction "CA7_27") (pintype "bidirectional"))
    )
    (net (code "32") (name "CA8-1") (class "Default")
      (node (ref "C1-7") (pin "A") (pinfunction "A_A") (pintype "passive"))
      (node (ref "C2-7") (pin "A") (pinfunction "A_A") (pintype "passive"))
      (node (ref "C3-7") (pin "A") (pinfunction "A_A") (pintype "passive"))
      (node (ref "C4-7") (pin "A") (pinfunction "A_A") (pintype "passive"))
      (node (ref "C5-7") (pin "A") (pinfunction "A_A") (pintype "passive"))
      (node (ref "C6-7") (pin "A") (pinfunction "A_A") (pintype "passive"))
      (node (ref "C7-7") (pin "A") (pinfunction "A_A") (pintype "passive"))
      (node (ref "C8-1") (pin "C") (pinfunction "C_C") (pintype "passive"))
      (node (ref "C8-2") (pin "C") (pinfunction "C_C") (pintype "passive"))
      (node (ref "C8-3") (pin "C") (pinfunction "C_C") (pintype "passive"))
      (node (ref "C8-4") (pin "C") (pinfunction "C_C") (pintype "passive"))
      (node (ref "C8-5") (pin "C") (pinfunction "C_C") (pintype "passive"))
      (node (ref "C8-6") (pin "C") (pinfunction "C_C") (pintype "passive"))
      (node (ref "C8-7") (pin "C") (pinfunction "C_C") (pintype "passive"))
      (node (ref "C8-8") (pin "C") (pinfunction "C_C") (pintype "passive"))
      (node (ref "C9-8") (pin "A") (pinfunction "A_A") (pintype "passive"))
      (node (ref "U4") (pin "28") (pinfunction "CA8_28") (pintype "bidirectional"))
    )
    (net (code "33") (name "CA8-2") (class "Default")
      (node (ref "C1-23") (pin "A") (pinfunction "A_A") (pintype "passive"))
      (node (ref "C2-23") (pin "A") (pinfunction "A_A") (pintype "passive"))
      (node (ref "C3-23") (pin "A") (pinfunction "A_A") (pintype "passive"))
      (node (ref "C4-23") (pin "A") (pinfunction "A_A") (pintype "passive"))
      (node (ref "C5-23") (pin "A") (pinfunction "A_A") (pintype "passive"))
      (node (ref "C6-23") (pin "A") (pinfunction "A_A") (pintype "passive"))
      (node (ref "C7-23") (pin "A") (pinfunction "A_A") (pintype "passive"))
      (node (ref "C8-17") (pin "C") (pinfunction "C_C") (pintype "passive"))
      (node (ref "C8-18") (pin "C") (pinfunction "C_C") (pintype "passive"))
      (node (ref "C8-19") (pin "C") (pinfunction "C_C") (pintype "passive"))
      (node (ref "C8-20") (pin "C") (pinfunction "C_C") (pintype "passive"))
      (node (ref "C8-21") (pin "C") (pinfunction "C_C") (pintype "passive"))
      (node (ref "C8-22") (pin "C") (pinfunction "C_C") (pintype "passive"))
      (node (ref "C8-23") (pin "C") (pinfunction "C_C") (pintype "passive"))
      (node (ref "C8-24") (pin "C") (pinfunction "C_C") (pintype "passive"))
      (node (ref "C9-24") (pin "A") (pinfunction "A_A") (pintype "passive"))
      (node (ref "U2") (pin "28") (pinfunction "CA8_28") (pintype "bidirectional"))
    )
    (net (code "34") (name "CA8-3") (class "Default")
      (node (ref "C1-39") (pin "A") (pinfunction "A_A") (pintype "passive"))
      (node (ref "C2-39") (pin "A") (pinfunction "A_A") (pintype "passive"))
      (node (ref "C3-39") (pin "A") (pinfunction "A_A") (pintype "passive"))
      (node (ref "C4-39") (pin "A") (pinfunction "A_A") (pintype "passive"))
      (node (ref "C5-39") (pin "A") (pinfunction "A_A") (pintype "passive"))
      (node (ref "C6-39") (pin "A") (pinfunction "A_A") (pintype "passive"))
      (node (ref "C7-39") (pin "A") (pinfunction "A_A") (pintype "passive"))
      (node (ref "C8-33") (pin "C") (pinfunction "C_C") (pintype "passive"))
      (node (ref "C8-34") (pin "C") (pinfunction "C_C") (pintype "passive"))
      (node (ref "C8-35") (pin "C") (pinfunction "C_C") (pintype "passive"))
      (node (ref "C8-36") (pin "C") (pinfunction "C_C") (pintype "passive"))
      (node (ref "C8-37") (pin "C") (pinfunction "C_C") (pintype "passive"))
      (node (ref "C8-38") (pin "C") (pinfunction "C_C") (pintype "passive"))
      (node (ref "C8-39") (pin "C") (pinfunction "C_C") (pintype "passive"))
      (node (ref "C8-40") (pin "C") (pinfunction "C_C") (pintype "passive"))
      (node (ref "C9-40") (pin "A") (pinfunction "A_A") (pintype "passive"))
      (node (ref "U3") (pin "28") (pinfunction "CA8_28") (pintype "bidirectional"))
    )
    (net (code "35") (name "CA8-4") (class "Default")
      (node (ref "C1-55") (pin "A") (pinfunction "A_A") (pintype "passive"))
      (node (ref "C2-55") (pin "A") (pinfunction "A_A") (pintype "passive"))
      (node (ref "C3-55") (pin "A") (pinfunction "A_A") (pintype "passive"))
      (node (ref "C4-55") (pin "A") (pinfunction "A_A") (pintype "passive"))
      (node (ref "C5-55") (pin "A") (pinfunction "A_A") (pintype "passive"))
      (node (ref "C6-55") (pin "A") (pinfunction "A_A") (pintype "passive"))
      (node (ref "C7-55") (pin "A") (pinfunction "A_A") (pintype "passive"))
      (node (ref "C8-49") (pin "C") (pinfunction "C_C") (pintype "passive"))
      (node (ref "C8-50") (pin "C") (pinfunction "C_C") (pintype "passive"))
      (node (ref "C8-51") (pin "C") (pinfunction "C_C") (pintype "passive"))
      (node (ref "C8-52") (pin "C") (pinfunction "C_C") (pintype "passive"))
      (node (ref "C8-53") (pin "C") (pinfunction "C_C") (pintype "passive"))
      (node (ref "C8-54") (pin "C") (pinfunction "C_C") (pintype "passive"))
      (node (ref "C8-55") (pin "C") (pinfunction "C_C") (pintype "passive"))
      (node (ref "C8-56") (pin "C") (pinfunction "C_C") (pintype "passive"))
      (node (ref "C9-56") (pin "A") (pinfunction "A_A") (pintype "passive"))
      (node (ref "U5") (pin "28") (pinfunction "CA8_28") (pintype "bidirectional"))
    )
    (net (code "36") (name "CA9-1") (class "Default")
      (node (ref "C1-8") (pin "A") (pinfunction "A_A") (pintype "passive"))
      (node (ref "C2-8") (pin "A") (pinfunction "A_A") (pintype "passive"))
      (node (ref "C3-8") (pin "A") (pinfunction "A_A") (pintype "passive"))
      (node (ref "C4-8") (pin "A") (pinfunction "A_A") (pintype "passive"))
      (node (ref "C5-8") (pin "A") (pinfunction "A_A") (pintype "passive"))
      (node (ref "C6-8") (pin "A") (pinfunction "A_A") (pintype "passive"))
      (node (ref "C7-8") (pin "A") (pinfunction "A_A") (pintype "passive"))
      (node (ref "C8-8") (pin "A") (pinfunction "A_A") (pintype "passive"))
      (node (ref "C9-1") (pin "C") (pinfunction "C_C") (pintype "passive"))
      (node (ref "C9-2") (pin "C") (pinfunction "C_C") (pintype "passive"))
      (node (ref "C9-3") (pin "C") (pinfunction "C_C") (pintype "passive"))
      (node (ref "C9-4") (pin "C") (pinfunction "C_C") (pintype "passive"))
      (node (ref "C9-5") (pin "C") (pinfunction "C_C") (pintype "passive"))
      (node (ref "C9-6") (pin "C") (pinfunction "C_C") (pintype "passive"))
      (node (ref "C9-7") (pin "C") (pinfunction "C_C") (pintype "passive"))
      (node (ref "C9-8") (pin "C") (pinfunction "C_C") (pintype "passive"))
      (node (ref "U4") (pin "1") (pinfunction "CA9_1") (pintype "bidirectional"))
    )
    (net (code "37") (name "CA9-2") (class "Default")
      (node (ref "C1-24") (pin "A") (pinfunction "A_A") (pintype "passive"))
      (node (ref "C2-24") (pin "A") (pinfunction "A_A") (pintype "passive"))
      (node (ref "C3-24") (pin "A") (pinfunction "A_A") (pintype "passive"))
      (node (ref "C4-24") (pin "A") (pinfunction "A_A") (pintype "passive"))
      (node (ref "C5-24") (pin "A") (pinfunction "A_A") (pintype "passive"))
      (node (ref "C6-24") (pin "A") (pinfunction "A_A") (pintype "passive"))
      (node (ref "C7-24") (pin "A") (pinfunction "A_A") (pintype "passive"))
      (node (ref "C8-24") (pin "A") (pinfunction "A_A") (pintype "passive"))
      (node (ref "C9-17") (pin "C") (pinfunction "C_C") (pintype "passive"))
      (node (ref "C9-18") (pin "C") (pinfunction "C_C") (pintype "passive"))
      (node (ref "C9-19") (pin "C") (pinfunction "C_C") (pintype "passive"))
      (node (ref "C9-20") (pin "C") (pinfunction "C_C") (pintype "passive"))
      (node (ref "C9-21") (pin "C") (pinfunction "C_C") (pintype "passive"))
      (node (ref "C9-22") (pin "C") (pinfunction "C_C") (pintype "passive"))
      (node (ref "C9-23") (pin "C") (pinfunction "C_C") (pintype "passive"))
      (node (ref "C9-24") (pin "C") (pinfunction "C_C") (pintype "passive"))
      (node (ref "U2") (pin "1") (pinfunction "CA9_1") (pintype "bidirectional"))
    )
    (net (code "38") (name "CA9-3") (class "Default")
      (node (ref "C1-40") (pin "A") (pinfunction "A_A") (pintype "passive"))
      (node (ref "C2-40") (pin "A") (pinfunction "A_A") (pintype "passive"))
      (node (ref "C3-40") (pin "A") (pinfunction "A_A") (pintype "passive"))
      (node (ref "C4-40") (pin "A") (pinfunction "A_A") (pintype "passive"))
      (node (ref "C5-40") (pin "A") (pinfunction "A_A") (pintype "passive"))
      (node (ref "C6-40") (pin "A") (pinfunction "A_A") (pintype "passive"))
      (node (ref "C7-40") (pin "A") (pinfunction "A_A") (pintype "passive"))
      (node (ref "C8-40") (pin "A") (pinfunction "A_A") (pintype "passive"))
      (node (ref "C9-33") (pin "C") (pinfunction "C_C") (pintype "passive"))
      (node (ref "C9-34") (pin "C") (pinfunction "C_C") (pintype "passive"))
      (node (ref "C9-35") (pin "C") (pinfunction "C_C") (pintype "passive"))
      (node (ref "C9-36") (pin "C") (pinfunction "C_C") (pintype "passive"))
      (node (ref "C9-37") (pin "C") (pinfunction "C_C") (pintype "passive"))
      (node (ref "C9-38") (pin "C") (pinfunction "C_C") (pintype "passive"))
      (node (ref "C9-39") (pin "C") (pinfunction "C_C") (pintype "passive"))
      (node (ref "C9-40") (pin "C") (pinfunction "C_C") (pintype "passive"))
      (node (ref "U3") (pin "1") (pinfunction "CA9_1") (pintype "bidirectional"))
    )
    (net (code "39") (name "CA9-4") (class "Default")
      (node (ref "C1-56") (pin "A") (pinfunction "A_A") (pintype "passive"))
      (node (ref "C2-56") (pin "A") (pinfunction "A_A") (pintype "passive"))
      (node (ref "C3-56") (pin "A") (pinfunction "A_A") (pintype "passive"))
      (node (ref "C4-56") (pin "A") (pinfunction "A_A") (pintype "passive"))
      (node (ref "C5-56") (pin "A") (pinfunction "A_A") (pintype "passive"))
      (node (ref "C6-56") (pin "A") (pinfunction "A_A") (pintype "passive"))
      (node (ref "C7-56") (pin "A") (pinfunction "A_A") (pintype "passive"))
      (node (ref "C8-56") (pin "A") (pinfunction "A_A") (pintype "passive"))
      (node (ref "C9-49") (pin "C") (pinfunction "C_C") (pintype "passive"))
      (node (ref "C9-50") (pin "C") (pinfunction "C_C") (pintype "passive"))
      (node (ref "C9-51") (pin "C") (pinfunction "C_C") (pintype "passive"))
      (node (ref "C9-52") (pin "C") (pinfunction "C_C") (pintype "passive"))
      (node (ref "C9-53") (pin "C") (pinfunction "C_C") (pintype "passive"))
      (node (ref "C9-54") (pin "C") (pinfunction "C_C") (pintype "passive"))
      (node (ref "C9-55") (pin "C") (pinfunction "C_C") (pintype "passive"))
      (node (ref "C9-56") (pin "C") (pinfunction "C_C") (pintype "passive"))
      (node (ref "U5") (pin "1") (pinfunction "CA9_1") (pintype "bidirectional"))
    )
    (net (code "40") (name "CB1-1") (class "Default")
      (node (ref "C1-10") (pin "C") (pinfunction "C_C") (pintype "passive"))
      (node (ref "C1-11") (pin "C") (pinfunction "C_C") (pintype "passive"))
      (node (ref "C1-12") (pin "C") (pinfunction "C_C") (pintype "passive"))
      (node (ref "C1-13") (pin "C") (pinfunction "C_C") (pintype "passive"))
      (node (ref "C1-14") (pin "C") (pinfunction "C_C") (pintype "passive"))
      (node (ref "C1-15") (pin "C") (pinfunction "C_C") (pintype "passive"))
      (node (ref "C1-16") (pin "C") (pinfunction "C_C") (pintype "passive"))
      (node (ref "C1-9") (pin "C") (pinfunction "C_C") (pintype "passive"))
      (node (ref "C2-9") (pin "A") (pinfunction "A_A") (pintype "passive"))
      (node (ref "C3-9") (pin "A") (pinfunction "A_A") (pintype "passive"))
      (node (ref "C4-9") (pin "A") (pinfunction "A_A") (pintype "passive"))
      (node (ref "C5-9") (pin "A") (pinfunction "A_A") (pintype "passive"))
      (node (ref "C6-9") (pin "A") (pinfunction "A_A") (pintype "passive"))
      (node (ref "C7-9") (pin "A") (pinfunction "A_A") (pintype "passive"))
      (node (ref "C8-9") (pin "A") (pinfunction "A_A") (pintype "passive"))
      (node (ref "C9-9") (pin "A") (pinfunction "A_A") (pintype "passive"))
      (node (ref "U4") (pin "7") (pinfunction "CB1_7") (pintype "bidirectional"))
    )
    (net (code "41") (name "CB1-2") (class "Default")
      (node (ref "C1-25") (pin "C") (pinfunction "C_C") (pintype "passive"))
      (node (ref "C1-26") (pin "C") (pinfunction "C_C") (pintype "passive"))
      (node (ref "C1-27") (pin "C") (pinfunction "C_C") (pintype "passive"))
      (node (ref "C1-28") (pin "C") (pinfunction "C_C") (pintype "passive"))
      (node (ref "C1-29") (pin "C") (pinfunction "C_C") (pintype "passive"))
      (node (ref "C1-30") (pin "C") (pinfunction "C_C") (pintype "passive"))
      (node (ref "C1-31") (pin "C") (pinfunction "C_C") (pintype "passive"))
      (node (ref "C1-32") (pin "C") (pinfunction "C_C") (pintype "passive"))
      (node (ref "C2-25") (pin "A") (pinfunction "A_A") (pintype "passive"))
      (node (ref "C3-25") (pin "A") (pinfunction "A_A") (pintype "passive"))
      (node (ref "C4-25") (pin "A") (pinfunction "A_A") (pintype "passive"))
      (node (ref "C5-25") (pin "A") (pinfunction "A_A") (pintype "passive"))
      (node (ref "C6-25") (pin "A") (pinfunction "A_A") (pintype "passive"))
      (node (ref "C7-25") (pin "A") (pinfunction "A_A") (pintype "passive"))
      (node (ref "C8-25") (pin "A") (pinfunction "A_A") (pintype "passive"))
      (node (ref "C9-25") (pin "A") (pinfunction "A_A") (pintype "passive"))
      (node (ref "U2") (pin "7") (pinfunction "CB1_7") (pintype "bidirectional"))
    )
    (net (code "42") (name "CB1-3") (class "Default")
      (node (ref "C1-41") (pin "C") (pinfunction "C_C") (pintype "passive"))
      (node (ref "C1-42") (pin "C") (pinfunction "C_C") (pintype "passive"))
      (node (ref "C1-43") (pin "C") (pinfunction "C_C") (pintype "passive"))
      (node (ref "C1-44") (pin "C") (pinfunction "C_C") (pintype "passive"))
      (node (ref "C1-45") (pin "C") (pinfunction "C_C") (pintype "passive"))
      (node (ref "C1-46") (pin "C") (pinfunction "C_C") (pintype "passive"))
      (node (ref "C1-47") (pin "C") (pinfunction "C_C") (pintype "passive"))
      (node (ref "C1-48") (pin "C") (pinfunction "C_C") (pintype "passive"))
      (node (ref "C2-41") (pin "A") (pinfunction "A_A") (pintype "passive"))
      (node (ref "C3-41") (pin "A") (pinfunction "A_A") (pintype "passive"))
      (node (ref "C4-41") (pin "A") (pinfunction "A_A") (pintype "passive"))
      (node (ref "C5-41") (pin "A") (pinfunction "A_A") (pintype "passive"))
      (node (ref "C6-41") (pin "A") (pinfunction "A_A") (pintype "passive"))
      (node (ref "C7-41") (pin "A") (pinfunction "A_A") (pintype "passive"))
      (node (ref "C8-41") (pin "A") (pinfunction "A_A") (pintype "passive"))
      (node (ref "C9-41") (pin "A") (pinfunction "A_A") (pintype "passive"))
      (node (ref "U3") (pin "7") (pinfunction "CB1_7") (pintype "bidirectional"))
    )
    (net (code "43") (name "CB1-4") (class "Default")
      (node (ref "C1-57") (pin "C") (pinfunction "C_C") (pintype "passive"))
      (node (ref "C1-58") (pin "C") (pinfunction "C_C") (pintype "passive"))
      (node (ref "C1-59") (pin "C") (pinfunction "C_C") (pintype "passive"))
      (node (ref "C1-60") (pin "C") (pinfunction "C_C") (pintype "passive"))
      (node (ref "C1-61") (pin "C") (pinfunction "C_C") (pintype "passive"))
      (node (ref "C1-62") (pin "C") (pinfunction "C_C") (pintype "passive"))
      (node (ref "C1-63") (pin "C") (pinfunction "C_C") (pintype "passive"))
      (node (ref "C1-64") (pin "C") (pinfunction "C_C") (pintype "passive"))
      (node (ref "C2-57") (pin "A") (pinfunction "A_A") (pintype "passive"))
      (node (ref "C3-57") (pin "A") (pinfunction "A_A") (pintype "passive"))
      (node (ref "C4-57") (pin "A") (pinfunction "A_A") (pintype "passive"))
      (node (ref "C5-57") (pin "A") (pinfunction "A_A") (pintype "passive"))
      (node (ref "C6-57") (pin "A") (pinfunction "A_A") (pintype "passive"))
      (node (ref "C7-57") (pin "A") (pinfunction "A_A") (pintype "passive"))
      (node (ref "C8-57") (pin "A") (pinfunction "A_A") (pintype "passive"))
      (node (ref "C9-57") (pin "A") (pinfunction "A_A") (pintype "passive"))
      (node (ref "U5") (pin "7") (pinfunction "CB1_7") (pintype "bidirectional"))
    )
    (net (code "44") (name "CB2-1") (class "Default")
      (node (ref "C1-9") (pin "A") (pinfunction "A_A") (pintype "passive"))
      (node (ref "C2-10") (pin "C") (pinfunction "C_C") (pintype "passive"))
      (node (ref "C2-11") (pin "C") (pinfunction "C_C") (pintype "passive"))
      (node (ref "C2-12") (pin "C") (pinfunction "C_C") (pintype "passive"))
      (node (ref "C2-13") (pin "C") (pinfunction "C_C") (pintype "passive"))
      (node (ref "C2-14") (pin "C") (pinfunction "C_C") (pintype "passive"))
      (node (ref "C2-15") (pin "C") (pinfunction "C_C") (pintype "passive"))
      (node (ref "C2-16") (pin "C") (pinfunction "C_C") (pintype "passive"))
      (node (ref "C2-9") (pin "C") (pinfunction "C_C") (pintype "passive"))
      (node (ref "C3-10") (pin "A") (pinfunction "A_A") (pintype "passive"))
      (node (ref "C4-10") (pin "A") (pinfunction "A_A") (pintype "passive"))
      (node (ref "C5-10") (pin "A") (pinfunction "A_A") (pintype "passive"))
      (node (ref "C6-10") (pin "A") (pinfunction "A_A") (pintype "passive"))
      (node (ref "C7-10") (pin "A") (pinfunction "A_A") (pintype "passive"))
      (node (ref "C8-10") (pin "A") (pinfunction "A_A") (pintype "passive"))
      (node (ref "C9-10") (pin "A") (pinfunction "A_A") (pintype "passive"))
      (node (ref "U4") (pin "8") (pinfunction "CB2_8") (pintype "bidirectional"))
    )
    (net (code "45") (name "CB2-2") (class "Default")
      (node (ref "C1-25") (pin "A") (pinfunction "A_A") (pintype "passive"))
      (node (ref "C2-25") (pin "C") (pinfunction "C_C") (pintype "passive"))
      (node (ref "C2-26") (pin "C") (pinfunction "C_C") (pintype "passive"))
      (node (ref "C2-27") (pin "C") (pinfunction "C_C") (pintype "passive"))
      (node (ref "C2-28") (pin "C") (pinfunction "C_C") (pintype "passive"))
      (node (ref "C2-29") (pin "C") (pinfunction "C_C") (pintype "passive"))
      (node (ref "C2-30") (pin "C") (pinfunction "C_C") (pintype "passive"))
      (node (ref "C2-31") (pin "C") (pinfunction "C_C") (pintype "passive"))
      (node (ref "C2-32") (pin "C") (pinfunction "C_C") (pintype "passive"))
      (node (ref "C3-26") (pin "A") (pinfunction "A_A") (pintype "passive"))
      (node (ref "C4-26") (pin "A") (pinfunction "A_A") (pintype "passive"))
      (node (ref "C5-26") (pin "A") (pinfunction "A_A") (pintype "passive"))
      (node (ref "C6-26") (pin "A") (pinfunction "A_A") (pintype "passive"))
      (node (ref "C7-26") (pin "A") (pinfunction "A_A") (pintype "passive"))
      (node (ref "C8-26") (pin "A") (pinfunction "A_A") (pintype "passive"))
      (node (ref "C9-26") (pin "A") (pinfunction "A_A") (pintype "passive"))
      (node (ref "U2") (pin "8") (pinfunction "CB2_8") (pintype "bidirectional"))
    )
    (net (code "46") (name "CB2-3") (class "Default")
      (node (ref "C1-41") (pin "A") (pinfunction "A_A") (pintype "passive"))
      (node (ref "C2-41") (pin "C") (pinfunction "C_C") (pintype "passive"))
      (node (ref "C2-42") (pin "C") (pinfunction "C_C") (pintype "passive"))
      (node (ref "C2-43") (pin "C") (pinfunction "C_C") (pintype "passive"))
      (node (ref "C2-44") (pin "C") (pinfunction "C_C") (pintype "passive"))
      (node (ref "C2-45") (pin "C") (pinfunction "C_C") (pintype "passive"))
      (node (ref "C2-46") (pin "C") (pinfunction "C_C") (pintype "passive"))
      (node (ref "C2-47") (pin "C") (pinfunction "C_C") (pintype "passive"))
      (node (ref "C2-48") (pin "C") (pinfunction "C_C") (pintype "passive"))
      (node (ref "C3-42") (pin "A") (pinfunction "A_A") (pintype "passive"))
      (node (ref "C4-42") (pin "A") (pinfunction "A_A") (pintype "passive"))
      (node (ref "C5-42") (pin "A") (pinfunction "A_A") (pintype "passive"))
      (node (ref "C6-42") (pin "A") (pinfunction "A_A") (pintype "passive"))
      (node (ref "C7-42") (pin "A") (pinfunction "A_A") (pintype "passive"))
      (node (ref "C8-42") (pin "A") (pinfunction "A_A") (pintype "passive"))
      (node (ref "C9-42") (pin "A") (pinfunction "A_A") (pintype "passive"))
      (node (ref "U3") (pin "8") (pinfunction "CB2_8") (pintype "bidirectional"))
    )
    (net (code "47") (name "CB2-4") (class "Default")
      (node (ref "C1-57") (pin "A") (pinfunction "A_A") (pintype "passive"))
      (node (ref "C2-57") (pin "C") (pinfunction "C_C") (pintype "passive"))
      (node (ref "C2-58") (pin "C") (pinfunction "C_C") (pintype "passive"))
      (node (ref "C2-59") (pin "C") (pinfunction "C_C") (pintype "passive"))
      (node (ref "C2-60") (pin "C") (pinfunction "C_C") (pintype "passive"))
      (node (ref "C2-61") (pin "C") (pinfunction "C_C") (pintype "passive"))
      (node (ref "C2-62") (pin "C") (pinfunction "C_C") (pintype "passive"))
      (node (ref "C2-63") (pin "C") (pinfunction "C_C") (pintype "passive"))
      (node (ref "C2-64") (pin "C") (pinfunction "C_C") (pintype "passive"))
      (node (ref "C3-58") (pin "A") (pinfunction "A_A") (pintype "passive"))
      (node (ref "C4-58") (pin "A") (pinfunction "A_A") (pintype "passive"))
      (node (ref "C5-58") (pin "A") (pinfunction "A_A") (pintype "passive"))
      (node (ref "C6-58") (pin "A") (pinfunction "A_A") (pintype "passive"))
      (node (ref "C7-58") (pin "A") (pinfunction "A_A") (pintype "passive"))
      (node (ref "C8-58") (pin "A") (pinfunction "A_A") (pintype "passive"))
      (node (ref "C9-58") (pin "A") (pinfunction "A_A") (pintype "passive"))
      (node (ref "U5") (pin "8") (pinfunction "CB2_8") (pintype "bidirectional"))
    )
    (net (code "48") (name "CB3-1") (class "Default")
      (node (ref "C1-10") (pin "A") (pinfunction "A_A") (pintype "passive"))
      (node (ref "C2-10") (pin "A") (pinfunction "A_A") (pintype "passive"))
      (node (ref "C3-10") (pin "C") (pinfunction "C_C") (pintype "passive"))
      (node (ref "C3-11") (pin "C") (pinfunction "C_C") (pintype "passive"))
      (node (ref "C3-12") (pin "C") (pinfunction "C_C") (pintype "passive"))
      (node (ref "C3-13") (pin "C") (pinfunction "C_C") (pintype "passive"))
      (node (ref "C3-14") (pin "C") (pinfunction "C_C") (pintype "passive"))
      (node (ref "C3-15") (pin "C") (pinfunction "C_C") (pintype "passive"))
      (node (ref "C3-16") (pin "C") (pinfunction "C_C") (pintype "passive"))
      (node (ref "C3-9") (pin "C") (pinfunction "C_C") (pintype "passive"))
      (node (ref "C4-11") (pin "A") (pinfunction "A_A") (pintype "passive"))
      (node (ref "C5-11") (pin "A") (pinfunction "A_A") (pintype "passive"))
      (node (ref "C6-11") (pin "A") (pinfunction "A_A") (pintype "passive"))
      (node (ref "C7-11") (pin "A") (pinfunction "A_A") (pintype "passive"))
      (node (ref "C8-11") (pin "A") (pinfunction "A_A") (pintype "passive"))
      (node (ref "C9-11") (pin "A") (pinfunction "A_A") (pintype "passive"))
      (node (ref "U4") (pin "9") (pinfunction "CB3_9") (pintype "bidirectional"))
    )
    (net (code "49") (name "CB3-2") (class "Default")
      (node (ref "C1-26") (pin "A") (pinfunction "A_A") (pintype "passive"))
      (node (ref "C2-26") (pin "A") (pinfunction "A_A") (pintype "passive"))
      (node (ref "C3-25") (pin "C") (pinfunction "C_C") (pintype "passive"))
      (node (ref "C3-26") (pin "C") (pinfunction "C_C") (pintype "passive"))
      (node (ref "C3-27") (pin "C") (pinfunction "C_C") (pintype "passive"))
      (node (ref "C3-28") (pin "C") (pinfunction "C_C") (pintype "passive"))
      (node (ref "C3-29") (pin "C") (pinfunction "C_C") (pintype "passive"))
      (node (ref "C3-30") (pin "C") (pinfunction "C_C") (pintype "passive"))
      (node (ref "C3-31") (pin "C") (pinfunction "C_C") (pintype "passive"))
      (node (ref "C3-32") (pin "C") (pinfunction "C_C") (pintype "passive"))
      (node (ref "C4-27") (pin "A") (pinfunction "A_A") (pintype "passive"))
      (node (ref "C5-27") (pin "A") (pinfunction "A_A") (pintype "passive"))
      (node (ref "C6-27") (pin "A") (pinfunction "A_A") (pintype "passive"))
      (node (ref "C7-27") (pin "A") (pinfunction "A_A") (pintype "passive"))
      (node (ref "C8-27") (pin "A") (pinfunction "A_A") (pintype "passive"))
      (node (ref "C9-27") (pin "A") (pinfunction "A_A") (pintype "passive"))
      (node (ref "U2") (pin "9") (pinfunction "CB3_9") (pintype "bidirectional"))
    )
    (net (code "50") (name "CB3-3") (class "Default")
      (node (ref "C1-42") (pin "A") (pinfunction "A_A") (pintype "passive"))
      (node (ref "C2-42") (pin "A") (pinfunction "A_A") (pintype "passive"))
      (node (ref "C3-41") (pin "C") (pinfunction "C_C") (pintype "passive"))
      (node (ref "C3-42") (pin "C") (pinfunction "C_C") (pintype "passive"))
      (node (ref "C3-43") (pin "C") (pinfunction "C_C") (pintype "passive"))
      (node (ref "C3-44") (pin "C") (pinfunction "C_C") (pintype "passive"))
      (node (ref "C3-45") (pin "C") (pinfunction "C_C") (pintype "passive"))
      (node (ref "C3-46") (pin "C") (pinfunction "C_C") (pintype "passive"))
      (node (ref "C3-47") (pin "C") (pinfunction "C_C") (pintype "passive"))
      (node (ref "C3-48") (pin "C") (pinfunction "C_C") (pintype "passive"))
      (node (ref "C4-43") (pin "A") (pinfunction "A_A") (pintype "passive"))
      (node (ref "C5-43") (pin "A") (pinfunction "A_A") (pintype "passive"))
      (node (ref "C6-43") (pin "A") (pinfunction "A_A") (pintype "passive"))
      (node (ref "C7-43") (pin "A") (pinfunction "A_A") (pintype "passive"))
      (node (ref "C8-43") (pin "A") (pinfunction "A_A") (pintype "passive"))
      (node (ref "C9-43") (pin "A") (pinfunction "A_A") (pintype "passive"))
      (node (ref "U3") (pin "9") (pinfunction "CB3_9") (pintype "bidirectional"))
    )
    (net (code "51") (name "CB3-4") (class "Default")
      (node (ref "C1-58") (pin "A") (pinfunction "A_A") (pintype "passive"))
      (node (ref "C2-58") (pin "A") (pinfunction "A_A") (pintype "passive"))
      (node (ref "C3-57") (pin "C") (pinfunction "C_C") (pintype "passive"))
      (node (ref "C3-58") (pin "C") (pinfunction "C_C") (pintype "passive"))
      (node (ref "C3-59") (pin "C") (pinfunction "C_C") (pintype "passive"))
      (node (ref "C3-60") (pin "C") (pinfunction "C_C") (pintype "passive"))
      (node (ref "C3-61") (pin "C") (pinfunction "C_C") (pintype "passive"))
      (node (ref "C3-62") (pin "C") (pinfunction "C_C") (pintype "passive"))
      (node (ref "C3-63") (pin "C") (pinfunction "C_C") (pintype "passive"))
      (node (ref "C3-64") (pin "C") (pinfunction "C_C") (pintype "passive"))
      (node (ref "C4-59") (pin "A") (pinfunction "A_A") (pintype "passive"))
      (node (ref "C5-59") (pin "A") (pinfunction "A_A") (pintype "passive"))
      (node (ref "C6-59") (pin "A") (pinfunction "A_A") (pintype "passive"))
      (node (ref "C7-59") (pin "A") (pinfunction "A_A") (pintype "passive"))
      (node (ref "C8-59") (pin "A") (pinfunction "A_A") (pintype "passive"))
      (node (ref "C9-59") (pin "A") (pinfunction "A_A") (pintype "passive"))
      (node (ref "U5") (pin "9") (pinfunction "CB3_9") (pintype "bidirectional"))
    )
    (net (code "52") (name "CB4-1") (class "Default")
      (node (ref "C1-11") (pin "A") (pinfunction "A_A") (pintype "passive"))
      (node (ref "C2-11") (pin "A") (pinfunction "A_A") (pintype "passive"))
      (node (ref "C3-11") (pin "A") (pinfunction "A_A") (pintype "passive"))
      (node (ref "C4-10") (pin "C") (pinfunction "C_C") (pintype "passive"))
      (node (ref "C4-11") (pin "C") (pinfunction "C_C") (pintype "passive"))
      (node (ref "C4-12") (pin "C") (pinfunction "C_C") (pintype "passive"))
      (node (ref "C4-13") (pin "C") (pinfunction "C_C") (pintype "passive"))
      (node (ref "C4-14") (pin "C") (pinfunction "C_C") (pintype "passive"))
      (node (ref "C4-15") (pin "C") (pinfunction "C_C") (pintype "passive"))
      (node (ref "C4-16") (pin "C") (pinfunction "C_C") (pintype "passive"))
      (node (ref "C4-9") (pin "C") (pinfunction "C_C") (pintype "passive"))
      (node (ref "C5-12") (pin "A") (pinfunction "A_A") (pintype "passive"))
      (node (ref "C6-12") (pin "A") (pinfunction "A_A") (pintype "passive"))
      (node (ref "C7-12") (pin "A") (pinfunction "A_A") (pintype "passive"))
      (node (ref "C8-12") (pin "A") (pinfunction "A_A") (pintype "passive"))
      (node (ref "C9-12") (pin "A") (pinfunction "A_A") (pintype "passive"))
      (node (ref "U4") (pin "10") (pinfunction "CB4_10") (pintype "bidirectional"))
    )
    (net (code "53") (name "CB4-2") (class "Default")
      (node (ref "C1-27") (pin "A") (pinfunction "A_A") (pintype "passive"))
      (node (ref "C2-27") (pin "A") (pinfunction "A_A") (pintype "passive"))
      (node (ref "C3-27") (pin "A") (pinfunction "A_A") (pintype "passive"))
      (node (ref "C4-25") (pin "C") (pinfunction "C_C") (pintype "passive"))
      (node (ref "C4-26") (pin "C") (pinfunction "C_C") (pintype "passive"))
      (node (ref "C4-27") (pin "C") (pinfunction "C_C") (pintype "passive"))
      (node (ref "C4-28") (pin "C") (pinfunction "C_C") (pintype "passive"))
      (node (ref "C4-29") (pin "C") (pinfunction "C_C") (pintype "passive"))
      (node (ref "C4-30") (pin "C") (pinfunction "C_C") (pintype "passive"))
      (node (ref "C4-31") (pin "C") (pinfunction "C_C") (pintype "passive"))
      (node (ref "C4-32") (pin "C") (pinfunction "C_C") (pintype "passive"))
      (node (ref "C5-28") (pin "A") (pinfunction "A_A") (pintype "passive"))
      (node (ref "C6-28") (pin "A") (pinfunction "A_A") (pintype "passive"))
      (node (ref "C7-28") (pin "A") (pinfunction "A_A") (pintype "passive"))
      (node (ref "C8-28") (pin "A") (pinfunction "A_A") (pintype "passive"))
      (node (ref "C9-28") (pin "A") (pinfunction "A_A") (pintype "passive"))
      (node (ref "U2") (pin "10") (pinfunction "CB4_10") (pintype "bidirectional"))
    )
    (net (code "54") (name "CB4-3") (class "Default")
      (node (ref "C1-43") (pin "A") (pinfunction "A_A") (pintype "passive"))
      (node (ref "C2-43") (pin "A") (pinfunction "A_A") (pintype "passive"))
      (node (ref "C3-43") (pin "A") (pinfunction "A_A") (pintype "passive"))
      (node (ref "C4-41") (pin "C") (pinfunction "C_C") (pintype "passive"))
      (node (ref "C4-42") (pin "C") (pinfunction "C_C") (pintype "passive"))
      (node (ref "C4-43") (pin "C") (pinfunction "C_C") (pintype "passive"))
      (node (ref "C4-44") (pin "C") (pinfunction "C_C") (pintype "passive"))
      (node (ref "C4-45") (pin "C") (pinfunction "C_C") (pintype "passive"))
      (node (ref "C4-46") (pin "C") (pinfunction "C_C") (pintype "passive"))
      (node (ref "C4-47") (pin "C") (pinfunction "C_C") (pintype "passive"))
      (node (ref "C4-48") (pin "C") (pinfunction "C_C") (pintype "passive"))
      (node (ref "C5-44") (pin "A") (pinfunction "A_A") (pintype "passive"))
      (node (ref "C6-44") (pin "A") (pinfunction "A_A") (pintype "passive"))
      (node (ref "C7-44") (pin "A") (pinfunction "A_A") (pintype "passive"))
      (node (ref "C8-44") (pin "A") (pinfunction "A_A") (pintype "passive"))
      (node (ref "C9-44") (pin "A") (pinfunction "A_A") (pintype "passive"))
      (node (ref "U3") (pin "10") (pinfunction "CB4_10") (pintype "bidirectional"))
    )
    (net (code "55") (name "CB4-4") (class "Default")
      (node (ref "C1-59") (pin "A") (pinfunction "A_A") (pintype "passive"))
      (node (ref "C2-59") (pin "A") (pinfunction "A_A") (pintype "passive"))
      (node (ref "C3-59") (pin "A") (pinfunction "A_A") (pintype "passive"))
      (node (ref "C4-57") (pin "C") (pinfunction "C_C") (pintype "passive"))
      (node (ref "C4-58") (pin "C") (pinfunction "C_C") (pintype "passive"))
      (node (ref "C4-59") (pin "C") (pinfunction "C_C") (pintype "passive"))
      (node (ref "C4-60") (pin "C") (pinfunction "C_C") (pintype "passive"))
      (node (ref "C4-61") (pin "C") (pinfunction "C_C") (pintype "passive"))
      (node (ref "C4-62") (pin "C") (pinfunction "C_C") (pintype "passive"))
      (node (ref "C4-63") (pin "C") (pinfunction "C_C") (pintype "passive"))
      (node (ref "C4-64") (pin "C") (pinfunction "C_C") (pintype "passive"))
      (node (ref "C5-60") (pin "A") (pinfunction "A_A") (pintype "passive"))
      (node (ref "C6-60") (pin "A") (pinfunction "A_A") (pintype "passive"))
      (node (ref "C7-60") (pin "A") (pinfunction "A_A") (pintype "passive"))
      (node (ref "C8-60") (pin "A") (pinfunction "A_A") (pintype "passive"))
      (node (ref "C9-60") (pin "A") (pinfunction "A_A") (pintype "passive"))
      (node (ref "U5") (pin "10") (pinfunction "CB4_10") (pintype "bidirectional"))
    )
    (net (code "56") (name "CB5-1") (class "Default")
      (node (ref "C1-12") (pin "A") (pinfunction "A_A") (pintype "passive"))
      (node (ref "C2-12") (pin "A") (pinfunction "A_A") (pintype "passive"))
      (node (ref "C3-12") (pin "A") (pinfunction "A_A") (pintype "passive"))
      (node (ref "C4-12") (pin "A") (pinfunction "A_A") (pintype "passive"))
      (node (ref "C5-10") (pin "C") (pinfunction "C_C") (pintype "passive"))
      (node (ref "C5-11") (pin "C") (pinfunction "C_C") (pintype "passive"))
      (node (ref "C5-12") (pin "C") (pinfunction "C_C") (pintype "passive"))
      (node (ref "C5-13") (pin "C") (pinfunction "C_C") (pintype "passive"))
      (node (ref "C5-14") (pin "C") (pinfunction "C_C") (pintype "passive"))
      (node (ref "C5-15") (pin "C") (pinfunction "C_C") (pintype "passive"))
      (node (ref "C5-16") (pin "C") (pinfunction "C_C") (pintype "passive"))
      (node (ref "C5-9") (pin "C") (pinfunction "C_C") (pintype "passive"))
      (node (ref "C6-13") (pin "A") (pinfunction "A_A") (pintype "passive"))
      (node (ref "C7-13") (pin "A") (pinfunction "A_A") (pintype "passive"))
      (node (ref "C8-13") (pin "A") (pinfunction "A_A") (pintype "passive"))
      (node (ref "C9-13") (pin "A") (pinfunction "A_A") (pintype "passive"))
      (node (ref "U4") (pin "11") (pinfunction "CB5_11") (pintype "bidirectional"))
    )
    (net (code "57") (name "CB5-2") (class "Default")
      (node (ref "C1-28") (pin "A") (pinfunction "A_A") (pintype "passive"))
      (node (ref "C2-28") (pin "A") (pinfunction "A_A") (pintype "passive"))
      (node (ref "C3-28") (pin "A") (pinfunction "A_A") (pintype "passive"))
      (node (ref "C4-28") (pin "A") (pinfunction "A_A") (pintype "passive"))
      (node (ref "C5-25") (pin "C") (pinfunction "C_C") (pintype "passive"))
      (node (ref "C5-26") (pin "C") (pinfunction "C_C") (pintype "passive"))
      (node (ref "C5-27") (pin "C") (pinfunction "C_C") (pintype "passive"))
      (node (ref "C5-28") (pin "C") (pinfunction "C_C") (pintype "passive"))
      (node (ref "C5-29") (pin "C") (pinfunction "C_C") (pintype "passive"))
      (node (ref "C5-30") (pin "C") (pinfunction "C_C") (pintype "passive"))
      (node (ref "C5-31") (pin "C") (pinfunction "C_C") (pintype "passive"))
      (node (ref "C5-32") (pin "C") (pinfunction "C_C") (pintype "passive"))
      (node (ref "C6-29") (pin "A") (pinfunction "A_A") (pintype "passive"))
      (node (ref "C7-29") (pin "A") (pinfunction "A_A") (pintype "passive"))
      (node (ref "C8-29") (pin "A") (pinfunction "A_A") (pintype "passive"))
      (node (ref "C9-29") (pin "A") (pinfunction "A_A") (pintype "passive"))
      (node (ref "U2") (pin "11") (pinfunction "CB5_11") (pintype "bidirectional"))
    )
    (net (code "58") (name "CB5-3") (class "Default")
      (node (ref "C1-44") (pin "A") (pinfunction "A_A") (pintype "passive"))
      (node (ref "C2-44") (pin "A") (pinfunction "A_A") (pintype "passive"))
      (node (ref "C3-44") (pin "A") (pinfunction "A_A") (pintype "passive"))
      (node (ref "C4-44") (pin "A") (pinfunction "A_A") (pintype "passive"))
      (node (ref "C5-41") (pin "C") (pinfunction "C_C") (pintype "passive"))
      (node (ref "C5-42") (pin "C") (pinfunction "C_C") (pintype "passive"))
      (node (ref "C5-43") (pin "C") (pinfunction "C_C") (pintype "passive"))
      (node (ref "C5-44") (pin "C") (pinfunction "C_C") (pintype "passive"))
      (node (ref "C5-45") (pin "C") (pinfunction "C_C") (pintype "passive"))
      (node (ref "C5-46") (pin "C") (pinfunction "C_C") (pintype "passive"))
      (node (ref "C5-47") (pin "C") (pinfunction "C_C") (pintype "passive"))
      (node (ref "C5-48") (pin "C") (pinfunction "C_C") (pintype "passive"))
      (node (ref "C6-45") (pin "A") (pinfunction "A_A") (pintype "passive"))
      (node (ref "C7-45") (pin "A") (pinfunction "A_A") (pintype "passive"))
      (node (ref "C8-45") (pin "A") (pinfunction "A_A") (pintype "passive"))
      (node (ref "C9-45") (pin "A") (pinfunction "A_A") (pintype "passive"))
      (node (ref "U3") (pin "11") (pinfunction "CB5_11") (pintype "bidirectional"))
    )
    (net (code "59") (name "CB5-4") (class "Default")
      (node (ref "C1-60") (pin "A") (pinfunction "A_A") (pintype "passive"))
      (node (ref "C2-60") (pin "A") (pinfunction "A_A") (pintype "passive"))
      (node (ref "C3-60") (pin "A") (pinfunction "A_A") (pintype "passive"))
      (node (ref "C4-60") (pin "A") (pinfunction "A_A") (pintype "passive"))
      (node (ref "C5-57") (pin "C") (pinfunction "C_C") (pintype "passive"))
      (node (ref "C5-58") (pin "C") (pinfunction "C_C") (pintype "passive"))
      (node (ref "C5-59") (pin "C") (pinfunction "C_C") (pintype "passive"))
      (node (ref "C5-60") (pin "C") (pinfunction "C_C") (pintype "passive"))
      (node (ref "C5-61") (pin "C") (pinfunction "C_C") (pintype "passive"))
      (node (ref "C5-62") (pin "C") (pinfunction "C_C") (pintype "passive"))
      (node (ref "C5-63") (pin "C") (pinfunction "C_C") (pintype "passive"))
      (node (ref "C5-64") (pin "C") (pinfunction "C_C") (pintype "passive"))
      (node (ref "C6-61") (pin "A") (pinfunction "A_A") (pintype "passive"))
      (node (ref "C7-61") (pin "A") (pinfunction "A_A") (pintype "passive"))
      (node (ref "C8-61") (pin "A") (pinfunction "A_A") (pintype "passive"))
      (node (ref "C9-61") (pin "A") (pinfunction "A_A") (pintype "passive"))
      (node (ref "U5") (pin "11") (pinfunction "CB5_11") (pintype "bidirectional"))
    )
    (net (code "60") (name "CB6-1") (class "Default")
      (node (ref "C1-13") (pin "A") (pinfunction "A_A") (pintype "passive"))
      (node (ref "C2-13") (pin "A") (pinfunction "A_A") (pintype "passive"))
      (node (ref "C3-13") (pin "A") (pinfunction "A_A") (pintype "passive"))
      (node (ref "C4-13") (pin "A") (pinfunction "A_A") (pintype "passive"))
      (node (ref "C5-13") (pin "A") (pinfunction "A_A") (pintype "passive"))
      (node (ref "C6-10") (pin "C") (pinfunction "C_C") (pintype "passive"))
      (node (ref "C6-11") (pin "C") (pinfunction "C_C") (pintype "passive"))
      (node (ref "C6-12") (pin "C") (pinfunction "C_C") (pintype "passive"))
      (node (ref "C6-13") (pin "C") (pinfunction "C_C") (pintype "passive"))
      (node (ref "C6-14") (pin "C") (pinfunction "C_C") (pintype "passive"))
      (node (ref "C6-15") (pin "C") (pinfunction "C_C") (pintype "passive"))
      (node (ref "C6-16") (pin "C") (pinfunction "C_C") (pintype "passive"))
      (node (ref "C6-9") (pin "C") (pinfunction "C_C") (pintype "passive"))
      (node (ref "C7-14") (pin "A") (pinfunction "A_A") (pintype "passive"))
      (node (ref "C8-14") (pin "A") (pinfunction "A_A") (pintype "passive"))
      (node (ref "C9-14") (pin "A") (pinfunction "A_A") (pintype "passive"))
      (node (ref "U4") (pin "12") (pinfunction "CB6_12") (pintype "bidirectional"))
    )
    (net (code "61") (name "CB6-2") (class "Default")
      (node (ref "C1-29") (pin "A") (pinfunction "A_A") (pintype "passive"))
      (node (ref "C2-29") (pin "A") (pinfunction "A_A") (pintype "passive"))
      (node (ref "C3-29") (pin "A") (pinfunction "A_A") (pintype "passive"))
      (node (ref "C4-29") (pin "A") (pinfunction "A_A") (pintype "passive"))
      (node (ref "C5-29") (pin "A") (pinfunction "A_A") (pintype "passive"))
      (node (ref "C6-25") (pin "C") (pinfunction "C_C") (pintype "passive"))
      (node (ref "C6-26") (pin "C") (pinfunction "C_C") (pintype "passive"))
      (node (ref "C6-27") (pin "C") (pinfunction "C_C") (pintype "passive"))
      (node (ref "C6-28") (pin "C") (pinfunction "C_C") (pintype "passive"))
      (node (ref "C6-29") (pin "C") (pinfunction "C_C") (pintype "passive"))
      (node (ref "C6-30") (pin "C") (pinfunction "C_C") (pintype "passive"))
      (node (ref "C6-31") (pin "C") (pinfunction "C_C") (pintype "passive"))
      (node (ref "C6-32") (pin "C") (pinfunction "C_C") (pintype "passive"))
      (node (ref "C7-30") (pin "A") (pinfunction "A_A") (pintype "passive"))
      (node (ref "C8-30") (pin "A") (pinfunction "A_A") (pintype "passive"))
      (node (ref "C9-30") (pin "A") (pinfunction "A_A") (pintype "passive"))
      (node (ref "U2") (pin "12") (pinfunction "CB6_12") (pintype "bidirectional"))
    )
    (net (code "62") (name "CB6-3") (class "Default")
      (node (ref "C1-45") (pin "A") (pinfunction "A_A") (pintype "passive"))
      (node (ref "C2-45") (pin "A") (pinfunction "A_A") (pintype "passive"))
      (node (ref "C3-45") (pin "A") (pinfunction "A_A") (pintype "passive"))
      (node (ref "C4-45") (pin "A") (pinfunction "A_A") (pintype "passive"))
      (node (ref "C5-45") (pin "A") (pinfunction "A_A") (pintype "passive"))
      (node (ref "C6-41") (pin "C") (pinfunction "C_C") (pintype "passive"))
      (node (ref "C6-42") (pin "C") (pinfunction "C_C") (pintype "passive"))
      (node (ref "C6-43") (pin "C") (pinfunction "C_C") (pintype "passive"))
      (node (ref "C6-44") (pin "C") (pinfunction "C_C") (pintype "passive"))
      (node (ref "C6-45") (pin "C") (pinfunction "C_C") (pintype "passive"))
      (node (ref "C6-46") (pin "C") (pinfunction "C_C") (pintype "passive"))
      (node (ref "C6-47") (pin "C") (pinfunction "C_C") (pintype "passive"))
      (node (ref "C6-48") (pin "C") (pinfunction "C_C") (pintype "passive"))
      (node (ref "C7-46") (pin "A") (pinfunction "A_A") (pintype "passive"))
      (node (ref "C8-46") (pin "A") (pinfunction "A_A") (pintype "passive"))
      (node (ref "C9-46") (pin "A") (pinfunction "A_A") (pintype "passive"))
      (node (ref "U3") (pin "12") (pinfunction "CB6_12") (pintype "bidirectional"))
    )
    (net (code "63") (name "CB6-4") (class "Default")
      (node (ref "C1-61") (pin "A") (pinfunction "A_A") (pintype "passive"))
      (node (ref "C2-61") (pin "A") (pinfunction "A_A") (pintype "passive"))
      (node (ref "C3-61") (pin "A") (pinfunction "A_A") (pintype "passive"))
      (node (ref "C4-61") (pin "A") (pinfunction "A_A") (pintype "passive"))
      (node (ref "C5-61") (pin "A") (pinfunction "A_A") (pintype "passive"))
      (node (ref "C6-57") (pin "C") (pinfunction "C_C") (pintype "passive"))
      (node (ref "C6-58") (pin "C") (pinfunction "C_C") (pintype "passive"))
      (node (ref "C6-59") (pin "C") (pinfunction "C_C") (pintype "passive"))
      (node (ref "C6-60") (pin "C") (pinfunction "C_C") (pintype "passive"))
      (node (ref "C6-61") (pin "C") (pinfunction "C_C") (pintype "passive"))
      (node (ref "C6-62") (pin "C") (pinfunction "C_C") (pintype "passive"))
      (node (ref "C6-63") (pin "C") (pinfunction "C_C") (pintype "passive"))
      (node (ref "C6-64") (pin "C") (pinfunction "C_C") (pintype "passive"))
      (node (ref "C7-62") (pin "A") (pinfunction "A_A") (pintype "passive"))
      (node (ref "C8-62") (pin "A") (pinfunction "A_A") (pintype "passive"))
      (node (ref "C9-62") (pin "A") (pinfunction "A_A") (pintype "passive"))
      (node (ref "U5") (pin "12") (pinfunction "CB6_12") (pintype "bidirectional"))
    )
    (net (code "64") (name "CB7-1") (class "Default")
      (node (ref "C1-14") (pin "A") (pinfunction "A_A") (pintype "passive"))
      (node (ref "C2-14") (pin "A") (pinfunction "A_A") (pintype "passive"))
      (node (ref "C3-14") (pin "A") (pinfunction "A_A") (pintype "passive"))
      (node (ref "C4-14") (pin "A") (pinfunction "A_A") (pintype "passive"))
      (node (ref "C5-14") (pin "A") (pinfunction "A_A") (pintype "passive"))
      (node (ref "C6-14") (pin "A") (pinfunction "A_A") (pintype "passive"))
      (node (ref "C7-10") (pin "C") (pinfunction "C_C") (pintype "passive"))
      (node (ref "C7-11") (pin "C") (pinfunction "C_C") (pintype "passive"))
      (node (ref "C7-12") (pin "C") (pinfunction "C_C") (pintype "passive"))
      (node (ref "C7-13") (pin "C") (pinfunction "C_C") (pintype "passive"))
      (node (ref "C7-14") (pin "C") (pinfunction "C_C") (pintype "passive"))
      (node (ref "C7-15") (pin "C") (pinfunction "C_C") (pintype "passive"))
      (node (ref "C7-16") (pin "C") (pinfunction "C_C") (pintype "passive"))
      (node (ref "C7-9") (pin "C") (pinfunction "C_C") (pintype "passive"))
      (node (ref "C8-15") (pin "A") (pinfunction "A_A") (pintype "passive"))
      (node (ref "C9-15") (pin "A") (pinfunction "A_A") (pintype "passive"))
      (node (ref "U4") (pin "13") (pinfunction "CB7_13") (pintype "bidirectional"))
    )
    (net (code "65") (name "CB7-2") (class "Default")
      (node (ref "C1-30") (pin "A") (pinfunction "A_A") (pintype "passive"))
      (node (ref "C2-30") (pin "A") (pinfunction "A_A") (pintype "passive"))
      (node (ref "C3-30") (pin "A") (pinfunction "A_A") (pintype "passive"))
      (node (ref "C4-30") (pin "A") (pinfunction "A_A") (pintype "passive"))
      (node (ref "C5-30") (pin "A") (pinfunction "A_A") (pintype "passive"))
      (node (ref "C6-30") (pin "A") (pinfunction "A_A") (pintype "passive"))
      (node (ref "C7-25") (pin "C") (pinfunction "C_C") (pintype "passive"))
      (node (ref "C7-26") (pin "C") (pinfunction "C_C") (pintype "passive"))
      (node (ref "C7-27") (pin "C") (pinfunction "C_C") (pintype "passive"))
      (node (ref "C7-28") (pin "C") (pinfunction "C_C") (pintype "passive"))
      (node (ref "C7-29") (pin "C") (pinfunction "C_C") (pintype "passive"))
      (node (ref "C7-30") (pin "C") (pinfunction "C_C") (pintype "passive"))
      (node (ref "C7-31") (pin "C") (pinfunction "C_C") (pintype "passive"))
      (node (ref "C7-32") (pin "C") (pinfunction "C_C") (pintype "passive"))
      (node (ref "C8-31") (pin "A") (pinfunction "A_A") (pintype "passive"))
      (node (ref "C9-31") (pin "A") (pinfunction "A_A") (pintype "passive"))
      (node (ref "U2") (pin "13") (pinfunction "CB7_13") (pintype "bidirectional"))
    )
    (net (code "66") (name "CB7-3") (class "Default")
      (node (ref "C1-46") (pin "A") (pinfunction "A_A") (pintype "passive"))
      (node (ref "C2-46") (pin "A") (pinfunction "A_A") (pintype "passive"))
      (node (ref "C3-46") (pin "A") (pinfunction "A_A") (pintype "passive"))
      (node (ref "C4-46") (pin "A") (pinfunction "A_A") (pintype "passive"))
      (node (ref "C5-46") (pin "A") (pinfunction "A_A") (pintype "passive"))
      (node (ref "C6-46") (pin "A") (pinfunction "A_A") (pintype "passive"))
      (node (ref "C7-41") (pin "C") (pinfunction "C_C") (pintype "passive"))
      (node (ref "C7-42") (pin "C") (pinfunction "C_C") (pintype "passive"))
      (node (ref "C7-43") (pin "C") (pinfunction "C_C") (pintype "passive"))
      (node (ref "C7-44") (pin "C") (pinfunction "C_C") (pintype "passive"))
      (node (ref "C7-45") (pin "C") (pinfunction "C_C") (pintype "passive"))
      (node (ref "C7-46") (pin "C") (pinfunction "C_C") (pintype "passive"))
      (node (ref "C7-47") (pin "C") (pinfunction "C_C") (pintype "passive"))
      (node (ref "C7-48") (pin "C") (pinfunction "C_C") (pintype "passive"))
      (node (ref "C8-47") (pin "A") (pinfunction "A_A") (pintype "passive"))
      (node (ref "C9-47") (pin "A") (pinfunction "A_A") (pintype "passive"))
      (node (ref "U3") (pin "13") (pinfunction "CB7_13") (pintype "bidirectional"))
    )
    (net (code "67") (name "CB7-4") (class "Default")
      (node (ref "C1-62") (pin "A") (pinfunction "A_A") (pintype "passive"))
      (node (ref "C2-62") (pin "A") (pinfunction "A_A") (pintype "passive"))
      (node (ref "C3-62") (pin "A") (pinfunction "A_A") (pintype "passive"))
      (node (ref "C4-62") (pin "A") (pinfunction "A_A") (pintype "passive"))
      (node (ref "C5-62") (pin "A") (pinfunction "A_A") (pintype "passive"))
      (node (ref "C6-62") (pin "A") (pinfunction "A_A") (pintype "passive"))
      (node (ref "C7-57") (pin "C") (pinfunction "C_C") (pintype "passive"))
      (node (ref "C7-58") (pin "C") (pinfunction "C_C") (pintype "passive"))
      (node (ref "C7-59") (pin "C") (pinfunction "C_C") (pintype "passive"))
      (node (ref "C7-60") (pin "C") (pinfunction "C_C") (pintype "passive"))
      (node (ref "C7-61") (pin "C") (pinfunction "C_C") (pintype "passive"))
      (node (ref "C7-62") (pin "C") (pinfunction "C_C") (pintype "passive"))
      (node (ref "C7-63") (pin "C") (pinfunction "C_C") (pintype "passive"))
      (node (ref "C7-64") (pin "C") (pinfunction "C_C") (pintype "passive"))
      (node (ref "C8-63") (pin "A") (pinfunction "A_A") (pintype "passive"))
      (node (ref "C9-63") (pin "A") (pinfunction "A_A") (pintype "passive"))
      (node (ref "U5") (pin "13") (pinfunction "CB7_13") (pintype "bidirectional"))
    )
    (net (code "68") (name "CB8-1") (class "Default")
      (node (ref "C1-15") (pin "A") (pinfunction "A_A") (pintype "passive"))
      (node (ref "C2-15") (pin "A") (pinfunction "A_A") (pintype "passive"))
      (node (ref "C3-15") (pin "A") (pinfunction "A_A") (pintype "passive"))
      (node (ref "C4-15") (pin "A") (pinfunction "A_A") (pintype "passive"))
      (node (ref "C5-15") (pin "A") (pinfunction "A_A") (pintype "passive"))
      (node (ref "C6-15") (pin "A") (pinfunction "A_A") (pintype "passive"))
      (node (ref "C7-15") (pin "A") (pinfunction "A_A") (pintype "passive"))
      (node (ref "C8-10") (pin "C") (pinfunction "C_C") (pintype "passive"))
      (node (ref "C8-11") (pin "C") (pinfunction "C_C") (pintype "passive"))
      (node (ref "C8-12") (pin "C") (pinfunction "C_C") (pintype "passive"))
      (node (ref "C8-13") (pin "C") (pinfunction "C_C") (pintype "passive"))
      (node (ref "C8-14") (pin "C") (pinfunction "C_C") (pintype "passive"))
      (node (ref "C8-15") (pin "C") (pinfunction "C_C") (pintype "passive"))
      (node (ref "C8-16") (pin "C") (pinfunction "C_C") (pintype "passive"))
      (node (ref "C8-9") (pin "C") (pinfunction "C_C") (pintype "passive"))
      (node (ref "C9-16") (pin "A") (pinfunction "A_A") (pintype "passive"))
      (node (ref "U4") (pin "14") (pinfunction "CB8_14") (pintype "bidirectional"))
    )
    (net (code "69") (name "CB8-2") (class "Default")
      (node (ref "C1-31") (pin "A") (pinfunction "A_A") (pintype "passive"))
      (node (ref "C2-31") (pin "A") (pinfunction "A_A") (pintype "passive"))
      (node (ref "C3-31") (pin "A") (pinfunction "A_A") (pintype "passive"))
      (node (ref "C4-31") (pin "A") (pinfunction "A_A") (pintype "passive"))
      (node (ref "C5-31") (pin "A") (pinfunction "A_A") (pintype "passive"))
      (node (ref "C6-31") (pin "A") (pinfunction "A_A") (pintype "passive"))
      (node (ref "C7-31") (pin "A") (pinfunction "A_A") (pintype "passive"))
      (node (ref "C8-25") (pin "C") (pinfunction "C_C") (pintype "passive"))
      (node (ref "C8-26") (pin "C") (pinfunction "C_C") (pintype "passive"))
      (node (ref "C8-27") (pin "C") (pinfunction "C_C") (pintype "passive"))
      (node (ref "C8-28") (pin "C") (pinfunction "C_C") (pintype "passive"))
      (node (ref "C8-29") (pin "C") (pinfunction "C_C") (pintype "passive"))
      (node (ref "C8-30") (pin "C") (pinfunction "C_C") (pintype "passive"))
      (node (ref "C8-31") (pin "C") (pinfunction "C_C") (pintype "passive"))
      (node (ref "C8-32") (pin "C") (pinfunction "C_C") (pintype "passive"))
      (node (ref "C9-32") (pin "A") (pinfunction "A_A") (pintype "passive"))
      (node (ref "U2") (pin "14") (pinfunction "CB8_14") (pintype "bidirectional"))
    )
    (net (code "70") (name "CB8-3") (class "Default")
      (node (ref "C1-47") (pin "A") (pinfunction "A_A") (pintype "passive"))
      (node (ref "C2-47") (pin "A") (pinfunction "A_A") (pintype "passive"))
      (node (ref "C3-47") (pin "A") (pinfunction "A_A") (pintype "passive"))
      (node (ref "C4-47") (pin "A") (pinfunction "A_A") (pintype "passive"))
      (node (ref "C5-47") (pin "A") (pinfunction "A_A") (pintype "passive"))
      (node (ref "C6-47") (pin "A") (pinfunction "A_A") (pintype "passive"))
      (node (ref "C7-47") (pin "A") (pinfunction "A_A") (pintype "passive"))
      (node (ref "C8-41") (pin "C") (pinfunction "C_C") (pintype "passive"))
      (node (ref "C8-42") (pin "C") (pinfunction "C_C") (pintype "passive"))
      (node (ref "C8-43") (pin "C") (pinfunction "C_C") (pintype "passive"))
      (node (ref "C8-44") (pin "C") (pinfunction "C_C") (pintype "passive"))
      (node (ref "C8-45") (pin "C") (pinfunction "C_C") (pintype "passive"))
      (node (ref "C8-46") (pin "C") (pinfunction "C_C") (pintype "passive"))
      (node (ref "C8-47") (pin "C") (pinfunction "C_C") (pintype "passive"))
      (node (ref "C8-48") (pin "C") (pinfunction "C_C") (pintype "passive"))
      (node (ref "C9-48") (pin "A") (pinfunction "A_A") (pintype "passive"))
      (node (ref "U3") (pin "14") (pinfunction "CB8_14") (pintype "bidirectional"))
    )
    (net (code "71") (name "CB8-4") (class "Default")
      (node (ref "C1-63") (pin "A") (pinfunction "A_A") (pintype "passive"))
      (node (ref "C2-63") (pin "A") (pinfunction "A_A") (pintype "passive"))
      (node (ref "C3-63") (pin "A") (pinfunction "A_A") (pintype "passive"))
      (node (ref "C4-63") (pin "A") (pinfunction "A_A") (pintype "passive"))
      (node (ref "C5-63") (pin "A") (pinfunction "A_A") (pintype "passive"))
      (node (ref "C6-63") (pin "A") (pinfunction "A_A") (pintype "passive"))
      (node (ref "C7-63") (pin "A") (pinfunction "A_A") (pintype "passive"))
      (node (ref "C8-57") (pin "C") (pinfunction "C_C") (pintype "passive"))
      (node (ref "C8-58") (pin "C") (pinfunction "C_C") (pintype "passive"))
      (node (ref "C8-59") (pin "C") (pinfunction "C_C") (pintype "passive"))
      (node (ref "C8-60") (pin "C") (pinfunction "C_C") (pintype "passive"))
      (node (ref "C8-61") (pin "C") (pinfunction "C_C") (pintype "passive"))
      (node (ref "C8-62") (pin "C") (pinfunction "C_C") (pintype "passive"))
      (node (ref "C8-63") (pin "C") (pinfunction "C_C") (pintype "passive"))
      (node (ref "C8-64") (pin "C") (pinfunction "C_C") (pintype "passive"))
      (node (ref "C9-64") (pin "A") (pinfunction "A_A") (pintype "passive"))
      (node (ref "U5") (pin "14") (pinfunction "CB8_14") (pintype "bidirectional"))
    )
    (net (code "72") (name "CB9-1") (class "Default")
      (node (ref "C1-16") (pin "A") (pinfunction "A_A") (pintype "passive"))
      (node (ref "C2-16") (pin "A") (pinfunction "A_A") (pintype "passive"))
      (node (ref "C3-16") (pin "A") (pinfunction "A_A") (pintype "passive"))
      (node (ref "C4-16") (pin "A") (pinfunction "A_A") (pintype "passive"))
      (node (ref "C5-16") (pin "A") (pinfunction "A_A") (pintype "passive"))
      (node (ref "C6-16") (pin "A") (pinfunction "A_A") (pintype "passive"))
      (node (ref "C7-16") (pin "A") (pinfunction "A_A") (pintype "passive"))
      (node (ref "C8-16") (pin "A") (pinfunction "A_A") (pintype "passive"))
      (node (ref "C9-10") (pin "C") (pinfunction "C_C") (pintype "passive"))
      (node (ref "C9-11") (pin "C") (pinfunction "C_C") (pintype "passive"))
      (node (ref "C9-12") (pin "C") (pinfunction "C_C") (pintype "passive"))
      (node (ref "C9-13") (pin "C") (pinfunction "C_C") (pintype "passive"))
      (node (ref "C9-14") (pin "C") (pinfunction "C_C") (pintype "passive"))
      (node (ref "C9-15") (pin "C") (pinfunction "C_C") (pintype "passive"))
      (node (ref "C9-16") (pin "C") (pinfunction "C_C") (pintype "passive"))
      (node (ref "C9-9") (pin "C") (pinfunction "C_C") (pintype "passive"))
      (node (ref "U4") (pin "15") (pinfunction "CB9_15") (pintype "bidirectional"))
    )
    (net (code "73") (name "CB9-2") (class "Default")
      (node (ref "C1-32") (pin "A") (pinfunction "A_A") (pintype "passive"))
      (node (ref "C2-32") (pin "A") (pinfunction "A_A") (pintype "passive"))
      (node (ref "C3-32") (pin "A") (pinfunction "A_A") (pintype "passive"))
      (node (ref "C4-32") (pin "A") (pinfunction "A_A") (pintype "passive"))
      (node (ref "C5-32") (pin "A") (pinfunction "A_A") (pintype "passive"))
      (node (ref "C6-32") (pin "A") (pinfunction "A_A") (pintype "passive"))
      (node (ref "C7-32") (pin "A") (pinfunction "A_A") (pintype "passive"))
      (node (ref "C8-32") (pin "A") (pinfunction "A_A") (pintype "passive"))
      (node (ref "C9-25") (pin "C") (pinfunction "C_C") (pintype "passive"))
      (node (ref "C9-26") (pin "C") (pinfunction "C_C") (pintype "passive"))
      (node (ref "C9-27") (pin "C") (pinfunction "C_C") (pintype "passive"))
      (node (ref "C9-28") (pin "C") (pinfunction "C_C") (pintype "passive"))
      (node (ref "C9-29") (pin "C") (pinfunction "C_C") (pintype "passive"))
      (node (ref "C9-30") (pin "C") (pinfunction "C_C") (pintype "passive"))
      (node (ref "C9-31") (pin "C") (pinfunction "C_C") (pintype "passive"))
      (node (ref "C9-32") (pin "C") (pinfunction "C_C") (pintype "passive"))
      (node (ref "U2") (pin "15") (pinfunction "CB9_15") (pintype "bidirectional"))
    )
    (net (code "74") (name "CB9-3") (class "Default")
      (node (ref "C1-48") (pin "A") (pinfunction "A_A") (pintype "passive"))
      (node (ref "C2-48") (pin "A") (pinfunction "A_A") (pintype "passive"))
      (node (ref "C3-48") (pin "A") (pinfunction "A_A") (pintype "passive"))
      (node (ref "C4-48") (pin "A") (pinfunction "A_A") (pintype "passive"))
      (node (ref "C5-48") (pin "A") (pinfunction "A_A") (pintype "passive"))
      (node (ref "C6-48") (pin "A") (pinfunction "A_A") (pintype "passive"))
      (node (ref "C7-48") (pin "A") (pinfunction "A_A") (pintype "passive"))
      (node (ref "C8-48") (pin "A") (pinfunction "A_A") (pintype "passive"))
      (node (ref "C9-41") (pin "C") (pinfunction "C_C") (pintype "passive"))
      (node (ref "C9-42") (pin "C") (pinfunction "C_C") (pintype "passive"))
      (node (ref "C9-43") (pin "C") (pinfunction "C_C") (pintype "passive"))
      (node (ref "C9-44") (pin "C") (pinfunction "C_C") (pintype "passive"))
      (node (ref "C9-45") (pin "C") (pinfunction "C_C") (pintype "passive"))
      (node (ref "C9-46") (pin "C") (pinfunction "C_C") (pintype "passive"))
      (node (ref "C9-47") (pin "C") (pinfunction "C_C") (pintype "passive"))
      (node (ref "C9-48") (pin "C") (pinfunction "C_C") (pintype "passive"))
      (node (ref "U3") (pin "15") (pinfunction "CB9_15") (pintype "bidirectional"))
    )
    (net (code "75") (name "CB9-4") (class "Default")
      (node (ref "C1-64") (pin "A") (pinfunction "A_A") (pintype "passive"))
      (node (ref "C2-64") (pin "A") (pinfunction "A_A") (pintype "passive"))
      (node (ref "C3-64") (pin "A") (pinfunction "A_A") (pintype "passive"))
      (node (ref "C4-64") (pin "A") (pinfunction "A_A") (pintype "passive"))
      (node (ref "C5-64") (pin "A") (pinfunction "A_A") (pintype "passive"))
      (node (ref "C6-64") (pin "A") (pinfunction "A_A") (pintype "passive"))
      (node (ref "C7-64") (pin "A") (pinfunction "A_A") (pintype "passive"))
      (node (ref "C8-64") (pin "A") (pinfunction "A_A") (pintype "passive"))
      (node (ref "C9-57") (pin "C") (pinfunction "C_C") (pintype "passive"))
      (node (ref "C9-58") (pin "C") (pinfunction "C_C") (pintype "passive"))
      (node (ref "C9-59") (pin "C") (pinfunction "C_C") (pintype "passive"))
      (node (ref "C9-60") (pin "C") (pinfunction "C_C") (pintype "passive"))
      (node (ref "C9-61") (pin "C") (pinfunction "C_C") (pintype "passive"))
      (node (ref "C9-62") (pin "C") (pinfunction "C_C") (pintype "passive"))
      (node (ref "C9-63") (pin "C") (pinfunction "C_C") (pintype "passive"))
      (node (ref "C9-64") (pin "C") (pinfunction "C_C") (pintype "passive"))
      (node (ref "U5") (pin "15") (pinfunction "CB9_15") (pintype "bidirectional"))
    )
    (net (code "76") (name "CH_PD") (class "Default")
      (node (ref "R18") (pin "1") (pinfunction "1_1") (pintype "passive"))
      (node (ref "X1") (pin "3") (pinfunction "CH_PD_3") (pintype "input"))
    )
    (net (code "77") (name "GND") (class "Default")
      (node (ref "C1") (pin "2") (pinfunction "2_2") (pintype "passive"))
      (node (ref "C10") (pin "2") (pinfunction "2_2") (pintype "passive"))
      (node (ref "C11") (pin "2") (pinfunction "2_2") (pintype "passive"))
      (node (ref "C111") (pin "2") (pinfunction "2_2") (pintype "passive"))
      (node (ref "C12") (pin "2") (pinfunction "2_2") (pintype "passive"))
      (node (ref "C13") (pin "2") (pinfunction "2_2") (pintype "passive"))
      (node (ref "C14") (pin "2") (pinfunction "2_2") (pintype "passive"))
      (node (ref "C15") (pin "2") (pinfunction "2_2") (pintype "passive"))
      (node (ref "C2") (pin "2") (pinfunction "2_2") (pintype "passive"))
      (node (ref "C3") (pin "2") (pinfunction "2_2") (pintype "passive"))
      (node (ref "C4") (pin "2") (pinfunction "2_2") (pintype "passive"))
      (node (ref "C5") (pin "2") (pinfunction "2_2") (pintype "passive"))
      (node (ref "C6") (pin "2") (pinfunction "2_2") (pintype "passive"))
      (node (ref "C7") (pin "2") (pinfunction "2_2") (pintype "passive"))
      (node (ref "C8") (pin "2") (pinfunction "2_2") (pintype "passive"))
      (node (ref "C9") (pin "2") (pinfunction "2_2") (pintype "passive"))
      (node (ref "J3") (pin "1") (pinfunction "1_1") (pintype "power_in"))
      (node (ref "JP1") (pin "1") (pinfunction "1_1") (pintype "passive"))
      (node (ref "R1") (pin "1") (pinfunction "1_1") (pintype "passive"))
      (node (ref "R11") (pin "1") (pinfunction "1_1") (pintype "passive"))
      (node (ref "R13") (pin "1") (pinfunction "1_1") (pintype "passive"))
      (node (ref "R16") (pin "2") (pinfunction "2_2") (pintype "passive"))
      (node (ref "R2") (pin "1") (pinfunction "1_1") (pintype "passive"))
      (node (ref "R25") (pin "1") (pinfunction "1_1") (pintype "passive"))
      (node (ref "R31") (pin "1") (pinfunction "1_1") (pintype "passive"))
      (node (ref "R8") (pin "2") (pinfunction "2_2") (pintype "passive"))
      (node (ref "R9") (pin "1") (pinfunction "1_1") (pintype "passive"))
      (node (ref "U$15") (pin "5") (pinfunction "GND_5") (pintype "bidirectional"))
      (node (ref "U$15") (pin "PAD") (pinfunction "GND_PAD") (pintype "bidirectional"))
      (node (ref "U$15") (pin "SHIELD1") (pinfunction "GND_SHIELD1") (pintype "bidirectional"))
      (node (ref "U$15") (pin "SHIELD2") (pinfunction "GND_SHIELD2") (pintype "bidirectional"))
      (node (ref "U$15") (pin "SHIELD3") (pinfunction "GND_SHIELD3") (pintype "bidirectional"))
      (node (ref "U$15") (pin "SHIELD4") (pinfunction "GND_SHIELD4") (pintype "bidirectional"))
      (node (ref "U$21") (pin "1") (pinfunction "PAD_1") (pintype "bidirectional"))
      (node (ref "U$3") (pin "1") (pinfunction "GND_1") (pintype "bidirectional"))
      (node (ref "U$9") (pin "2") (pinfunction "GND_2") (pintype "bidirectional"))
      (node (ref "U1") (pin "2") (pinfunction "VSS_2") (pintype "power_in"))
      (node (ref "U2") (pin "29_GND") (pinfunction "GND_29_GND") (pintype "bidirectional"))
      (node (ref "U2") (pin "5") (pinfunction "GND_5") (pintype "bidirectional"))
      (node (ref "U3") (pin "29_GND") (pinfunction "GND_29_GND") (pintype "bidirectional"))
      (node (ref "U3") (pin "5") (pinfunction "GND_5") (pintype "bidirectional"))
      (node (ref "U4") (pin "29_GND") (pinfunction "GND_29_GND") (pintype "bidirectional"))
      (node (ref "U4") (pin "5") (pinfunction "GND_5") (pintype "bidirectional"))
      (node (ref "U5") (pin "29_GND") (pinfunction "GND_29_GND") (pintype "bidirectional"))
      (node (ref "U5") (pin "5") (pinfunction "GND_5") (pintype "bidirectional"))
      (node (ref "X1") (pin "9") (pinfunction "GND_9") (pintype "power_in"))
    )
    (net (code "78") (name "GPIO0") (class "Default")
      (node (ref "R20") (pin "1") (pinfunction "1_1") (pintype "passive"))
      (node (ref "U$3") (pin "6") (pinfunction "RESET_6") (pintype "bidirectional"))
      (node (ref "X1") (pin "12") (pinfunction "GPIO0_12") (pintype "bidirectional"))
    )
    (net (code "79") (name "GPIO2") (class "Default")
      (node (ref "R10") (pin "1") (pinfunction "1_1") (pintype "passive"))
      (node (ref "X1") (pin "11") (pinfunction "GPIO2_11") (pintype "bidirectional"))
    )
    (net (code "80") (name "GPIO12") (class "Default")
      (node (ref "U$18") (pin "1") (pinfunction "PAD_1") (pintype "bidirectional"))
      (node (ref "X1") (pin "6") (pinfunction "GPIO12_6") (pintype "bidirectional"))
    )
    (net (code "81") (name "GPIO13") (class "Default")
      (node (ref "U$19") (pin "1") (pinfunction "PAD_1") (pintype "bidirectional"))
      (node (ref "X1") (pin "7") (pinfunction "GPIO13_7") (pintype "bidirectional"))
    )
    (net (code "82") (name "GPIO14") (class "Default")
      (node (ref "U$16") (pin "1") (pinfunction "PAD_1") (pintype "bidirectional"))
      (node (ref "X1") (pin "5") (pinfunction "GPIO14_5") (pintype "bidirectional"))
    )
    (net (code "83") (name "GPIO15") (class "Default")
      (node (ref "R9") (pin "2") (pinfunction "2_2") (pintype "passive"))
      (node (ref "X1") (pin "10") (pinfunction "GPIO15_10") (pintype "bidirectional"))
    )
    (net (code "84") (name "GPIO16") (class "Default")
      (node (ref "U$6") (pin "1") (pinfunction "PAD_1") (pintype "bidirectional"))
      (node (ref "X1") (pin "4") (pinfunction "GPIO16_4") (pintype "bidirectional"))
    )
    (net (code "85") (name "INTB1") (class "Default")
      (node (ref "R3") (pin "1") (pinfunction "1_1") (pintype "passive"))
      (node (ref "U4") (pin "4") (pinfunction "INTB_4") (pintype "bidirectional"))
    )
    (net (code "86") (name "INTB2") (class "Default")
      (node (ref "R6") (pin "1") (pinfunction "1_1") (pintype "passive"))
      (node (ref "U2") (pin "4") (pinfunction "INTB_4") (pintype "bidirectional"))
    )
    (net (code "87") (name "INTB3") (class "Default")
      (node (ref "R22") (pin "1") (pinfunction "1_1") (pintype "passive"))
      (node (ref "U3") (pin "4") (pinfunction "INTB_4") (pintype "bidirectional"))
    )
    (net (code "88") (name "INTB4") (class "Default")
      (node (ref "R28") (pin "1") (pinfunction "1_1") (pintype "passive"))
      (node (ref "U5") (pin "4") (pinfunction "INTB_4") (pintype "bidirectional"))
    )
    (net (code "89") (name "Net-(LED1-PadA)") (class "Default")
      (node (ref "LED1") (pin "A") (pinfunction "A_A") (pintype "passive"))
      (node (ref "R17") (pin "2") (pinfunction "2_2") (pintype "passive"))
    )
    (net (code "90") (name "Net-(Q3-S)") (class "Default")
      (node (ref "D1") (pin "C") (pinfunction "C_C") (pintype "passive"))
      (node (ref "Q3") (pin "2") (pinfunction "S_2") (pintype "bidirectional"))
      (node (ref "S1") (pin "2") (pinfunction "2_2") (pintype "bidirectional"))
    )
    (net (code "91") (name "Net-(U1-PROG)") (class "Default")
      (node (ref "R16") (pin "1") (pinfunction "1_1") (pintype "passive"))
      (node (ref "U1") (pin "5") (pinfunction "PROG_5") (pintype "input"))
    )
    (net (code "92") (name "Net-(U1-STAT)") (class "Default")
      (node (ref "LED1") (pin "C") (pinfunction "C_C") (pintype "passive"))
      (node (ref "U1") (pin "1") (pinfunction "STAT_1") (pintype "output"))
    )
    (net (code "93") (name "Net-(U2-C_FILT)") (class "Default")
      (node (ref "C12") (pin "1") (pinfunction "1_1") (pintype "passive"))
      (node (ref "U2") (pin "16") (pinfunction "C_FILT_16") (pintype "bidirectional"))
    )
    (net (code "94") (name "Net-(U2-R_EXT)") (class "Default")
      (node (ref "R8") (pin "1") (pinfunction "1_1") (pintype "passive"))
      (node (ref "U2") (pin "6") (pinfunction "R_EXT_6") (pintype "bidirectional"))
    )
    (net (code "95") (name "Net-(U3-C_FILT)") (class "Default")
      (node (ref "C11") (pin "1") (pinfunction "1_1") (pintype "passive"))
      (node (ref "U3") (pin "16") (pinfunction "C_FILT_16") (pintype "bidirectional"))
    )
    (net (code "96") (name "Net-(U3-R_EXT)") (class "Default")
      (node (ref "R25") (pin "2") (pinfunction "2_2") (pintype "passive"))
      (node (ref "U3") (pin "6") (pinfunction "R_EXT_6") (pintype "bidirectional"))
    )
    (net (code "97") (name "Net-(U4-C_FILT)") (class "Default")
      (node (ref "C2") (pin "1") (pinfunction "1_1") (pintype "passive"))
      (node (ref "U4") (pin "16") (pinfunction "C_FILT_16") (pintype "bidirectional"))
    )
    (net (code "98") (name "Net-(U4-R_EXT)") (class "Default")
      (node (ref "R1") (pin "2") (pinfunction "2_2") (pintype "passive"))
      (node (ref "U4") (pin "6") (pinfunction "R_EXT_6") (pintype "bidirectional"))
    )
    (net (code "99") (name "Net-(U5-C_FILT)") (class "Default")
      (node (ref "C15") (pin "1") (pinfunction "1_1") (pintype "passive"))
      (node (ref "U5") (pin "16") (pinfunction "C_FILT_16") (pintype "bidirectional"))
    )
    (net (code "100") (name "Net-(U5-R_EXT)") (class "Default")
      (node (ref "R31") (pin "2") (pinfunction "2_2") (pintype "passive"))
      (node (ref "U5") (pin "6") (pinfunction "R_EXT_6") (pintype "bidirectional"))
    )
    (net (code "101") (name "RESET") (class "Default")
      (node (ref "R19") (pin "1") (pinfunction "1_1") (pintype "passive"))
      (node (ref "U$3") (pin "5") (pinfunction "GPIO0_5") (pintype "bidirectional"))
      (node (ref "X1") (pin "1") (pinfunction "RESET_1") (pintype "input"))
    )
    (net (code "102") (name "RXD") (class "Default")
      (node (ref "U$3") (pin "4") (pinfunction "RX_4") (pintype "bidirectional"))
      (node (ref "X1") (pin "15") (pinfunction "RXD_15") (pintype "input"))
    )
    (net (code "103") (name "SCL") (class "Default")
      (node (ref "J3") (pin "4") (pinfunction "4_4") (pintype "passive"))
      (node (ref "R4") (pin "1") (pinfunction "1_1") (pintype "passive"))
      (node (ref "U2") (pin "20") (pinfunction "SCL_20") (pintype "bidirectional"))
      (node (ref "U3") (pin "18") (pinfunction "ADDR_18") (pintype "bidirectional"))
      (node (ref "U3") (pin "20") (pinfunction "SCL_20") (pintype "bidirectional"))
      (node (ref "U4") (pin "20") (pinfunction "SCL_20") (pintype "bidirectional"))
      (node (ref "U5") (pin "20") (pinfunction "SCL_20") (pintype "bidirectional"))
      (node (ref "X1") (pin "14") (pinfunction "GPIO4_14") (pintype "bidirectional"))
    )
    (net (code "104") (name "SDA") (class "Default")
      (node (ref "J3") (pin "3") (pinfunction "3_3") (pintype "passive"))
      (node (ref "R5") (pin "1") (pinfunction "1_1") (pintype "passive"))
      (node (ref "U2") (pin "19") (pinfunction "SDA_19") (pintype "bidirectional"))
      (node (ref "U3") (pin "19") (pinfunction "SDA_19") (pintype "bidirectional"))
      (node (ref "U4") (pin "19") (pinfunction "SDA_19") (pintype "bidirectional"))
      (node (ref "U5") (pin "18") (pinfunction "ADDR_18") (pintype "bidirectional"))
      (node (ref "U5") (pin "19") (pinfunction "SDA_19") (pintype "bidirectional"))
      (node (ref "X1") (pin "13") (pinfunction "GPIO5_13") (pintype "bidirectional"))
    )
    (net (code "105") (name "SHUTDOWN1") (class "Default")
      (node (ref "R14") (pin "2") (pinfunction "2_2") (pintype "passive"))
      (node (ref "U4") (pin "3") (pinfunction "SHUTDOWN_3") (pintype "bidirectional"))
    )
    (net (code "106") (name "SHUTDOWN2") (class "Default")
      (node (ref "R7") (pin "1") (pinfunction "1_1") (pintype "passive"))
      (node (ref "U2") (pin "3") (pinfunction "SHUTDOWN_3") (pintype "bidirectional"))
    )
    (net (code "107") (name "SHUTDOWN3") (class "Default")
      (node (ref "R15") (pin "2") (pinfunction "2_2") (pintype "passive"))
      (node (ref "U3") (pin "3") (pinfunction "SHUTDOWN_3") (pintype "bidirectional"))
    )
    (net (code "108") (name "SHUTDOWN4") (class "Default")
      (node (ref "R26") (pin "2") (pinfunction "2_2") (pintype "passive"))
      (node (ref "U5") (pin "3") (pinfunction "SHUTDOWN_3") (pintype "bidirectional"))
    )
    (net (code "109") (name "TXD") (class "Default")
      (node (ref "U$3") (pin "3") (pinfunction "TX_3") (pintype "bidirectional"))
      (node (ref "X1") (pin "16") (pinfunction "TXD_16") (pintype "output"))
    )
    (net (code "110") (name "VCC") (class "Default")
      (node (ref "C1") (pin "1") (pinfunction "1_1") (pintype "passive"))
      (node (ref "C10") (pin "1") (pinfunction "1_1") (pintype "passive"))
      (node (ref "C111") (pin "1") (pinfunction "1_1") (pintype "passive"))
      (node (ref "C13") (pin "1") (pinfunction "1_1") (pintype "passive"))
      (node (ref "C14") (pin "1") (pinfunction "1_1") (pintype "passive"))
      (node (ref "C5") (pin "1") (pinfunction "1_1") (pintype "passive"))
      (node (ref "C6") (pin "1") (pinfunction "1_1") (pintype "passive"))
      (node (ref "C7") (pin "1") (pinfunction "1_1") (pintype "passive"))
      (node (ref "C9") (pin "1") (pinfunction "1_1") (pintype "passive"))
      (node (ref "R14") (pin "1") (pinfunction "1_1") (pintype "passive"))
      (node (ref "R15") (pin "1") (pinfunction "1_1") (pintype "passive"))
      (node (ref "R22") (pin "2") (pinfunction "2_2") (pintype "passive"))
      (node (ref "R26") (pin "1") (pinfunction "1_1") (pintype "passive"))
      (node (ref "R28") (pin "2") (pinfunction "2_2") (pintype "passive"))
      (node (ref "R3") (pin "2") (pinfunction "2_2") (pintype "passive"))
      (node (ref "R4") (pin "2") (pinfunction "2_2") (pintype "passive"))
      (node (ref "R5") (pin "2") (pinfunction "2_2") (pintype "passive"))
      (node (ref "R6") (pin "2") (pinfunction "2_2") (pintype "passive"))
      (node (ref "R7") (pin "2") (pinfunction "2_2") (pintype "passive"))
      (node (ref "S1") (pin "3") (pinfunction "3_3") (pintype "bidirectional"))
      (node (ref "U$9") (pin "1") (pinfunction "VIN_1") (pintype "bidirectional"))
      (node (ref "U$9") (pin "3") (pinfunction "EN_3") (pintype "bidirectional"))
      (node (ref "U2") (pin "18") (pinfunction "ADDR_18") (pintype "bidirectional"))
      (node (ref "U2") (pin "2") (pinfunction "VCC_2") (pintype "bidirectional"))
      (node (ref "U3") (pin "2") (pinfunction "VCC_2") (pintype "bidirectional"))
      (node (ref "U4") (pin "2") (pinfunction "VCC_2") (pintype "bidirectional"))
      (node (ref "U5") (pin "2") (pinfunction "VCC_2") (pintype "bidirectional"))
    )
    (net (code "111") (name "V_BATT") (class "Default")
      (node (ref "C8") (pin "1") (pinfunction "1_1") (pintype "passive"))
      (node (ref "JP1") (pin "2") (pinfunction "2_2") (pintype "passive"))
      (node (ref "Q3") (pin "3") (pinfunction "D_3") (pintype "bidirectional"))
      (node (ref "R12") (pin "2") (pinfunction "2_2") (pintype "passive"))
      (node (ref "U1") (pin "3") (pinfunction "VBAT_3") (pintype "power_in"))
    )
    (net (code "112") (name "V_USB") (class "Default")
      (node (ref "D1") (pin "A") (pinfunction "A_A") (pintype "passive"))
      (node (ref "Q3") (pin "1") (pinfunction "G_1") (pintype "bidirectional"))
      (node (ref "R11") (pin "2") (pinfunction "2_2") (pintype "passive"))
      (node (ref "R17") (pin "1") (pinfunction "1_1") (pintype "passive"))
      (node (ref "U$15") (pin "1") (pinfunction "VBUS_1") (pintype "bidirectional"))
      (node (ref "U1") (pin "4") (pinfunction "VIN_4") (pintype "power_in"))
    )
    (net (code "113") (name "unconnected-(S1-Pad1)") (class "Default")
      (node (ref "S1") (pin "1") (pinfunction "1_1") (pintype "bidirectional"))
    )
    (net (code "114") (name "unconnected-(U$9-NC-Pad4)") (class "Default")
      (node (ref "U$9") (pin "4") (pinfunction "NC_4") (pintype "bidirectional"))
    )
    (net (code "115") (name "unconnected-(U$15-D+-Pad3)") (class "Default")
      (node (ref "U$15") (pin "3") (pinfunction "D+_3") (pintype "bidirectional"))
    )
    (net (code "116") (name "unconnected-(U$15-D--Pad2)") (class "Default")
      (node (ref "U$15") (pin "2") (pinfunction "D-_2") (pintype "bidirectional"))
    )
    (net (code "117") (name "unconnected-(U$15-ID-Pad4)") (class "Default")
      (node (ref "U$15") (pin "4") (pinfunction "ID_4") (pintype "bidirectional"))
    )
    (net (code "118") (name "unconnected-(U2-AUDIOIN-Pad17)") (class "Default")
      (node (ref "U2") (pin "17") (pinfunction "AUDIOIN_17") (pintype "bidirectional"))
    )
    (net (code "119") (name "unconnected-(U3-AUDIOIN-Pad17)") (class "Default")
      (node (ref "U3") (pin "17") (pinfunction "AUDIOIN_17") (pintype "bidirectional"))
    )
    (net (code "120") (name "unconnected-(U4-AUDIOIN-Pad17)") (class "Default")
      (node (ref "U4") (pin "17") (pinfunction "AUDIOIN_17") (pintype "bidirectional"))
    )
    (net (code "121") (name "unconnected-(U5-AUDIOIN-Pad17)") (class "Default")
      (node (ref "U5") (pin "17") (pinfunction "AUDIOIN_17") (pintype "bidirectional"))
    )
  )
)
